# BreakOutBoard_Cyclone.net
KiCad netlist of a schematic drawn in Altium Designer
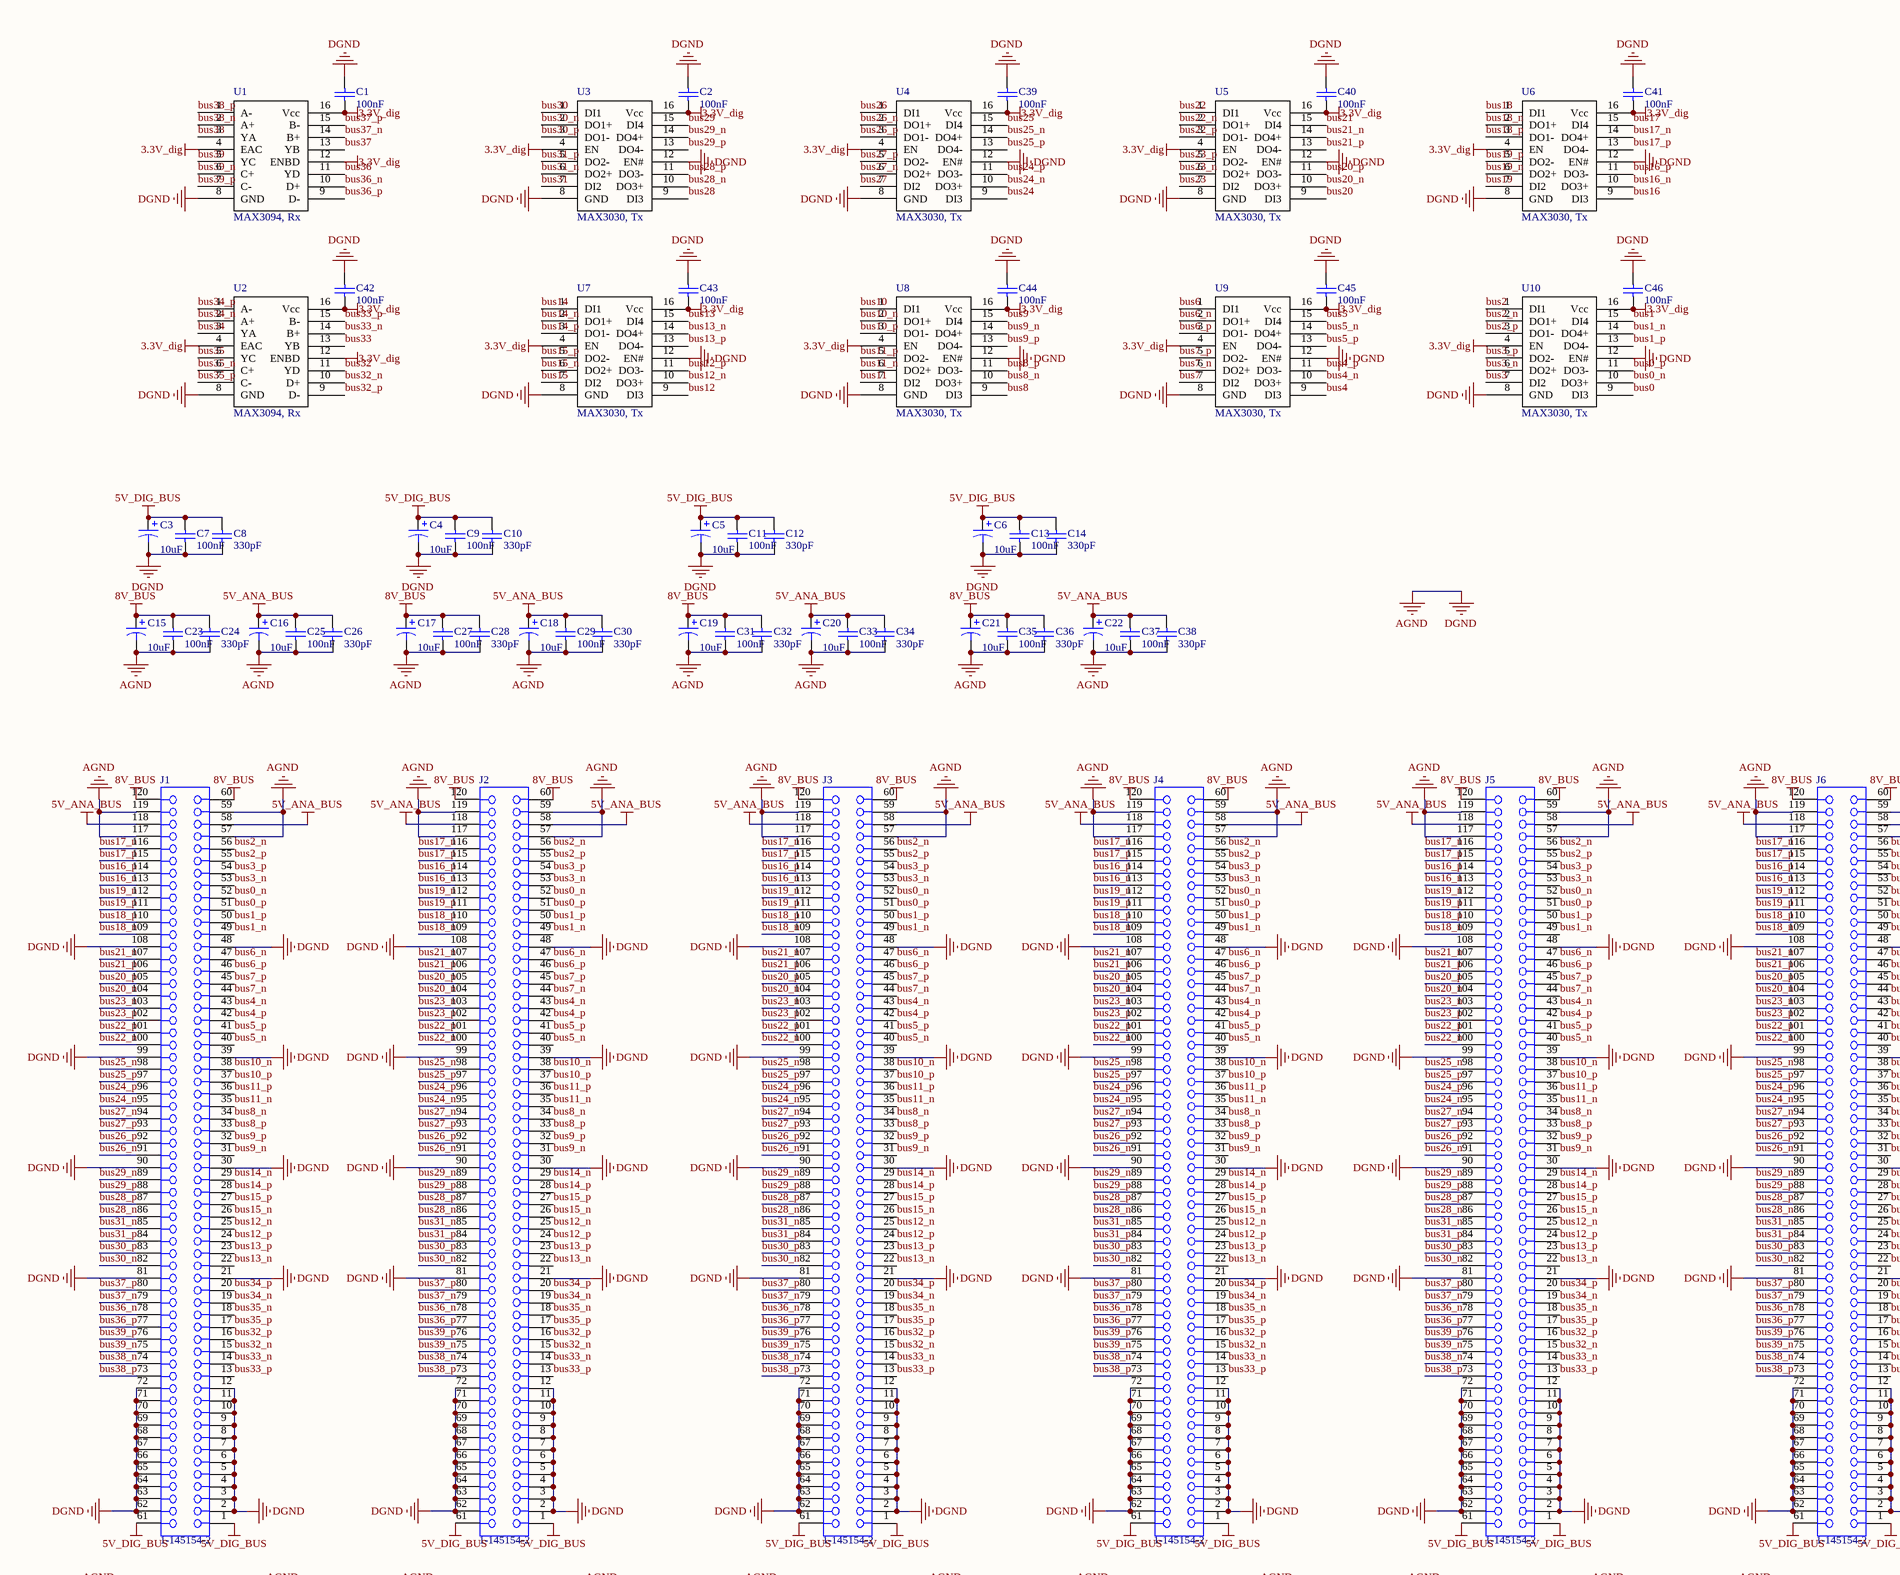
[diagram p0: BreakOutBoard_Cyclone.SchDoc, top left]
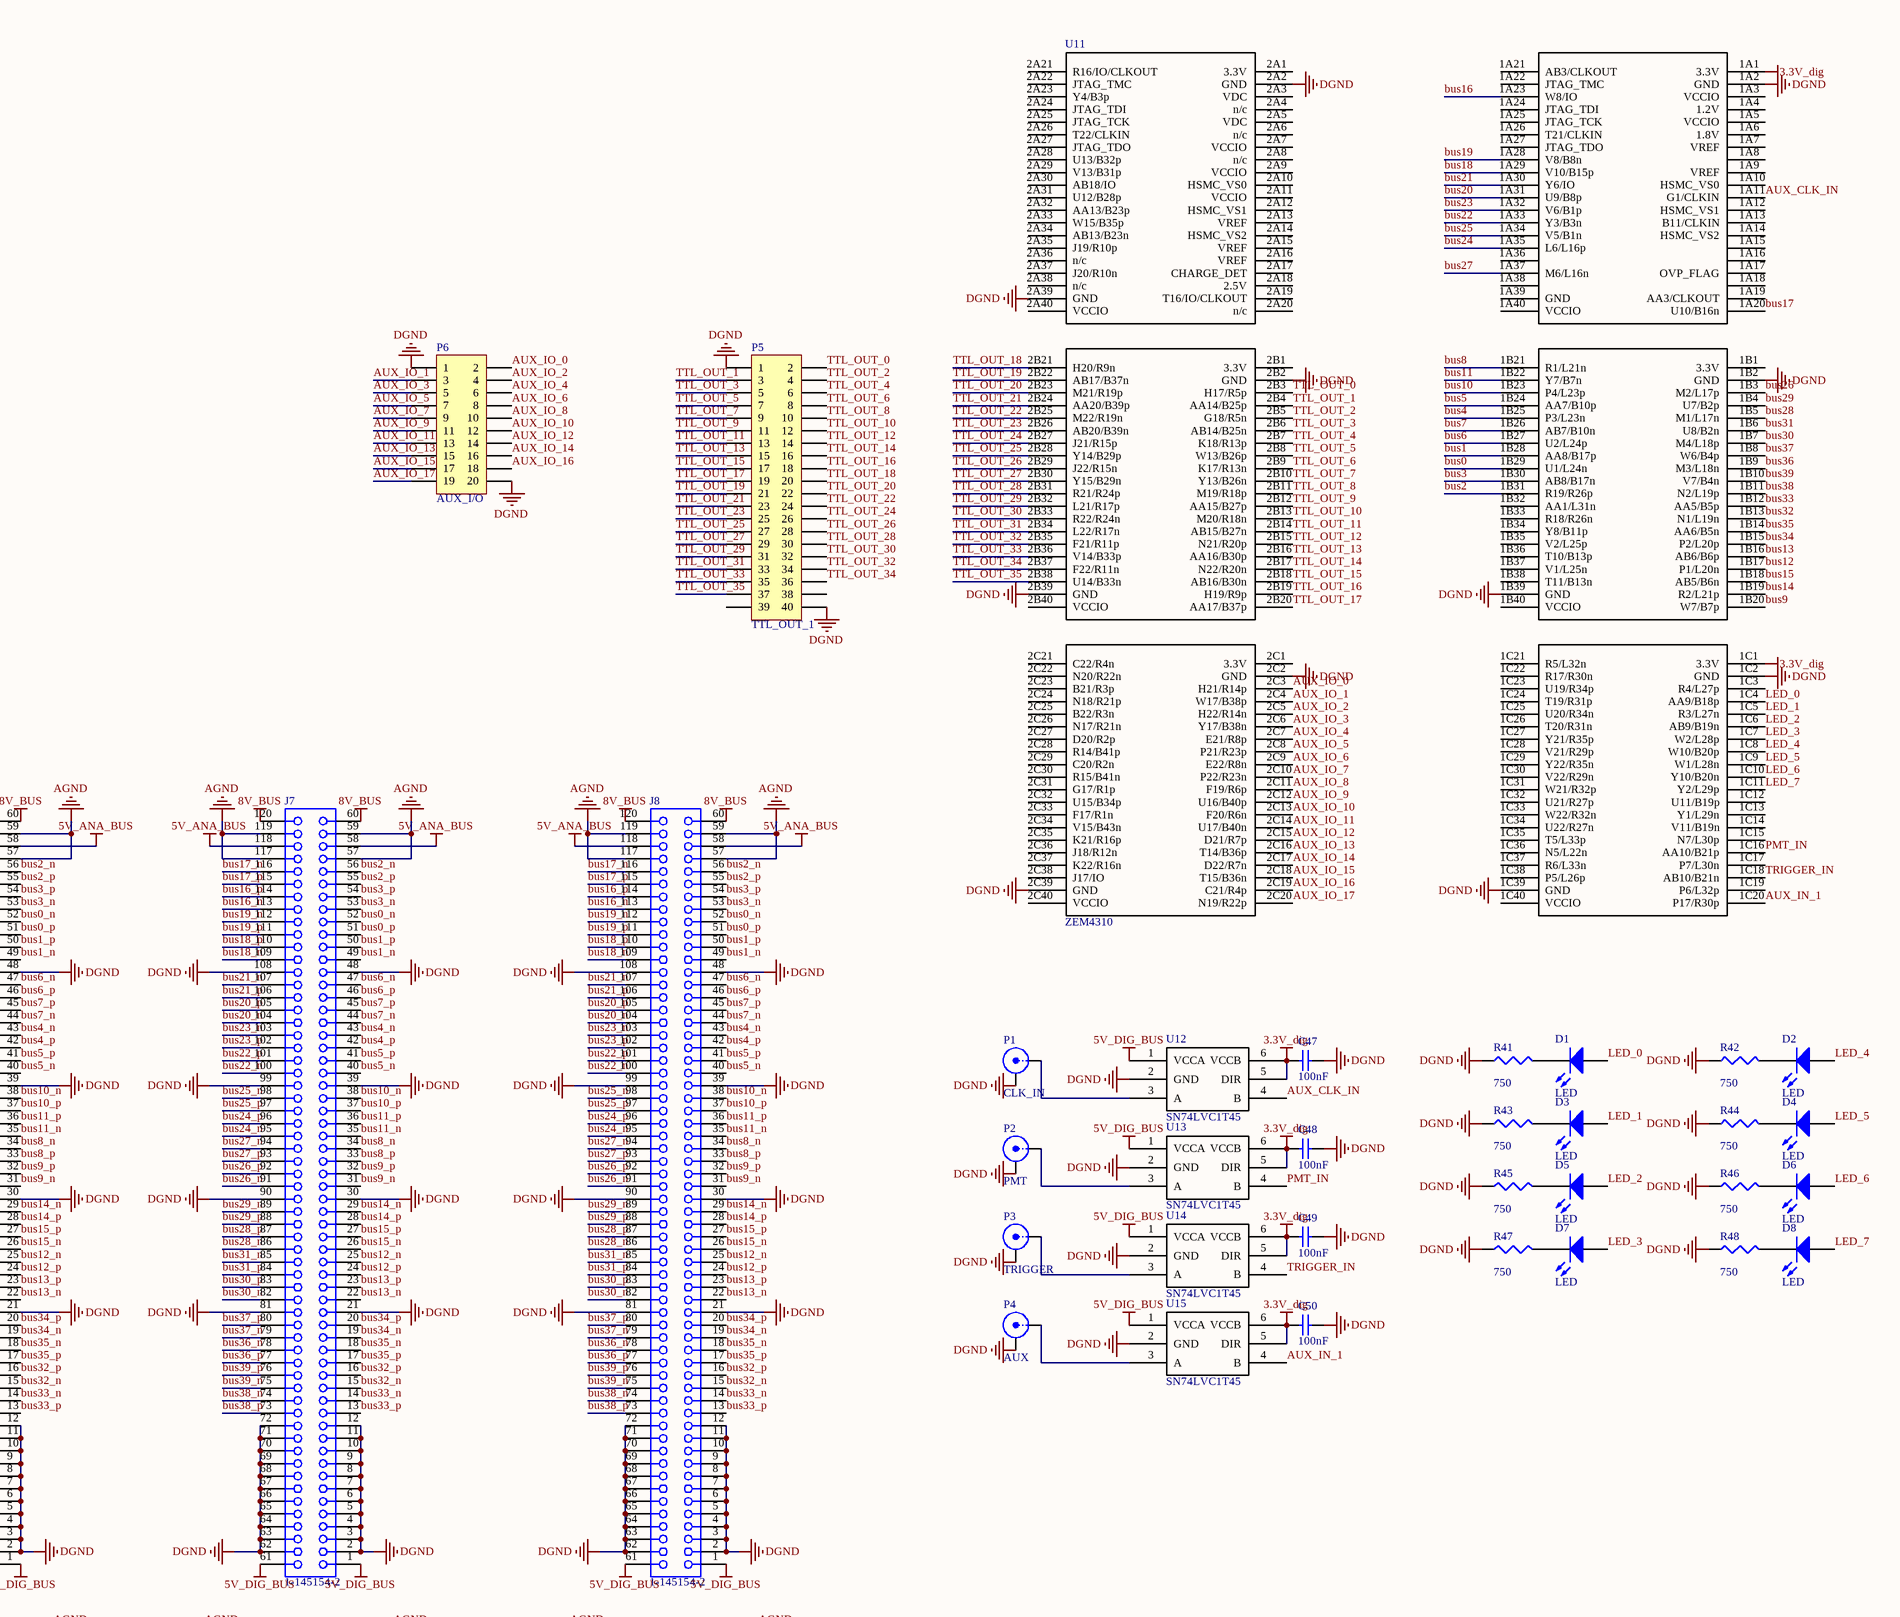
[diagram p1: BreakOutBoard_Cyclone.SchDoc, top right]
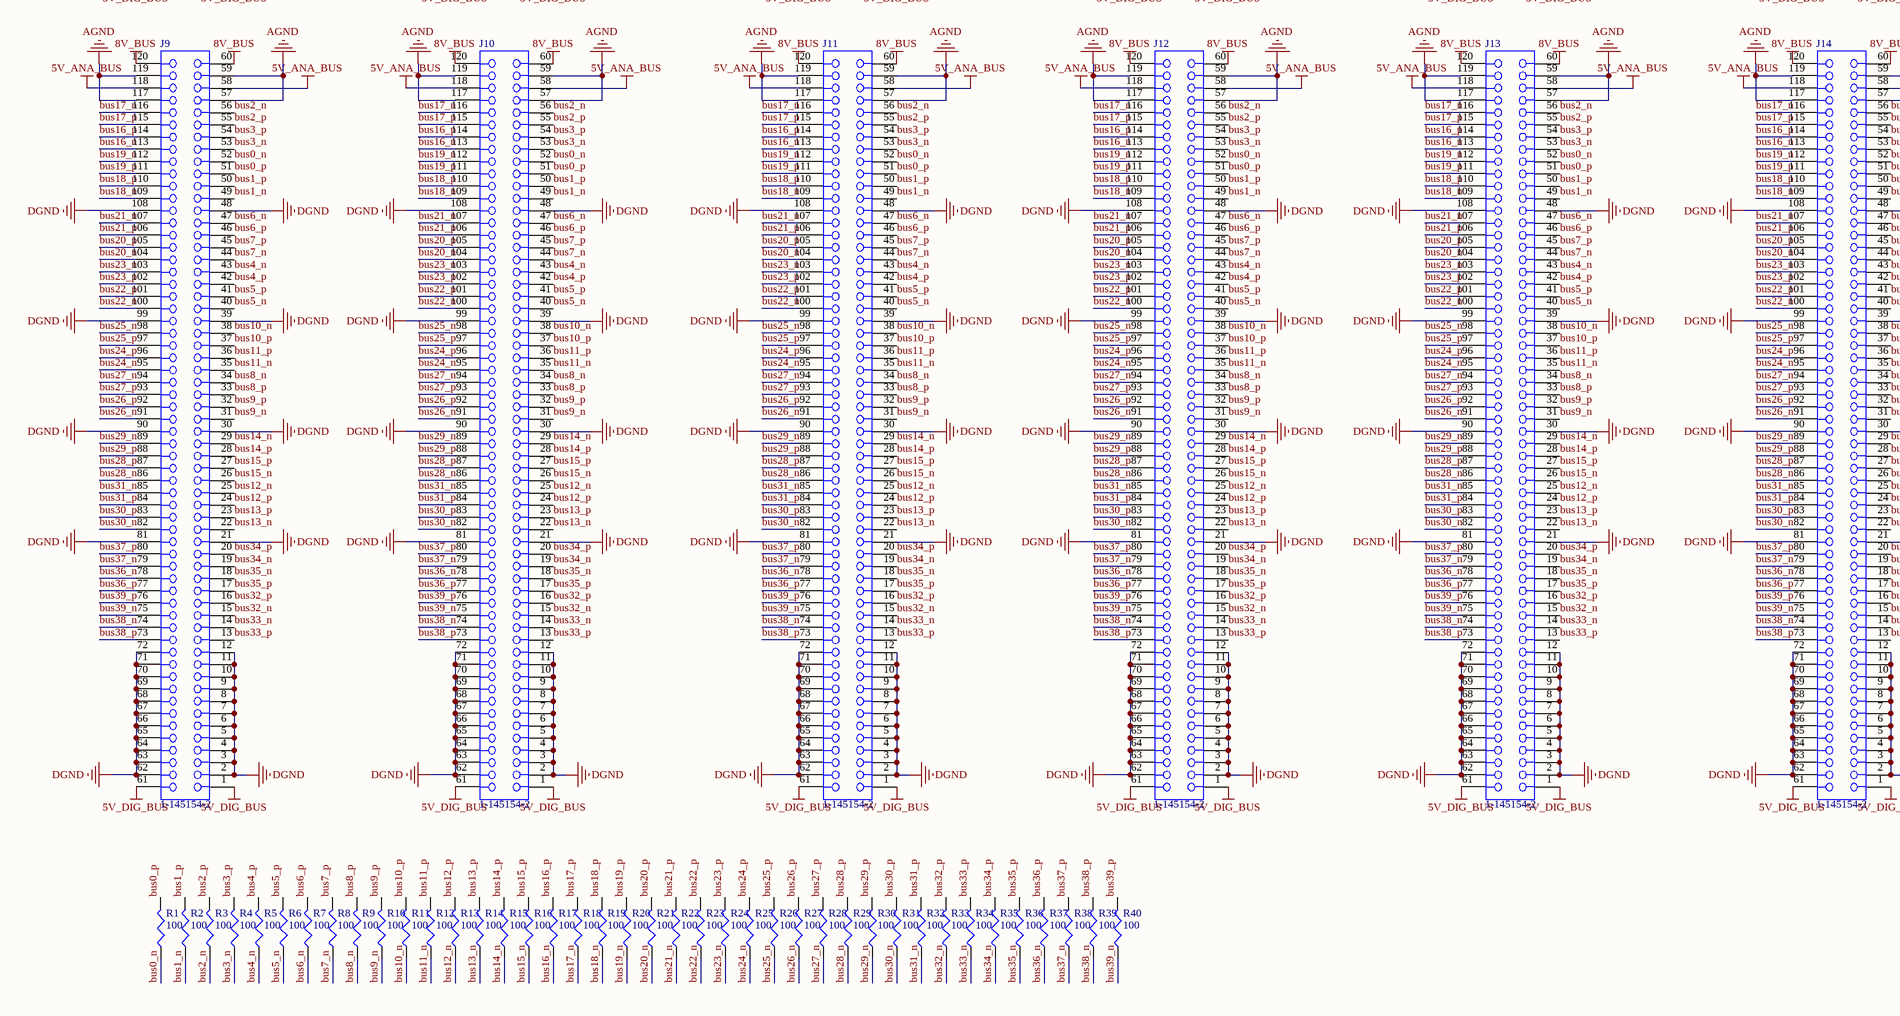
[diagram p2: BreakOutBoard_Cyclone.SchDoc, bottom left]
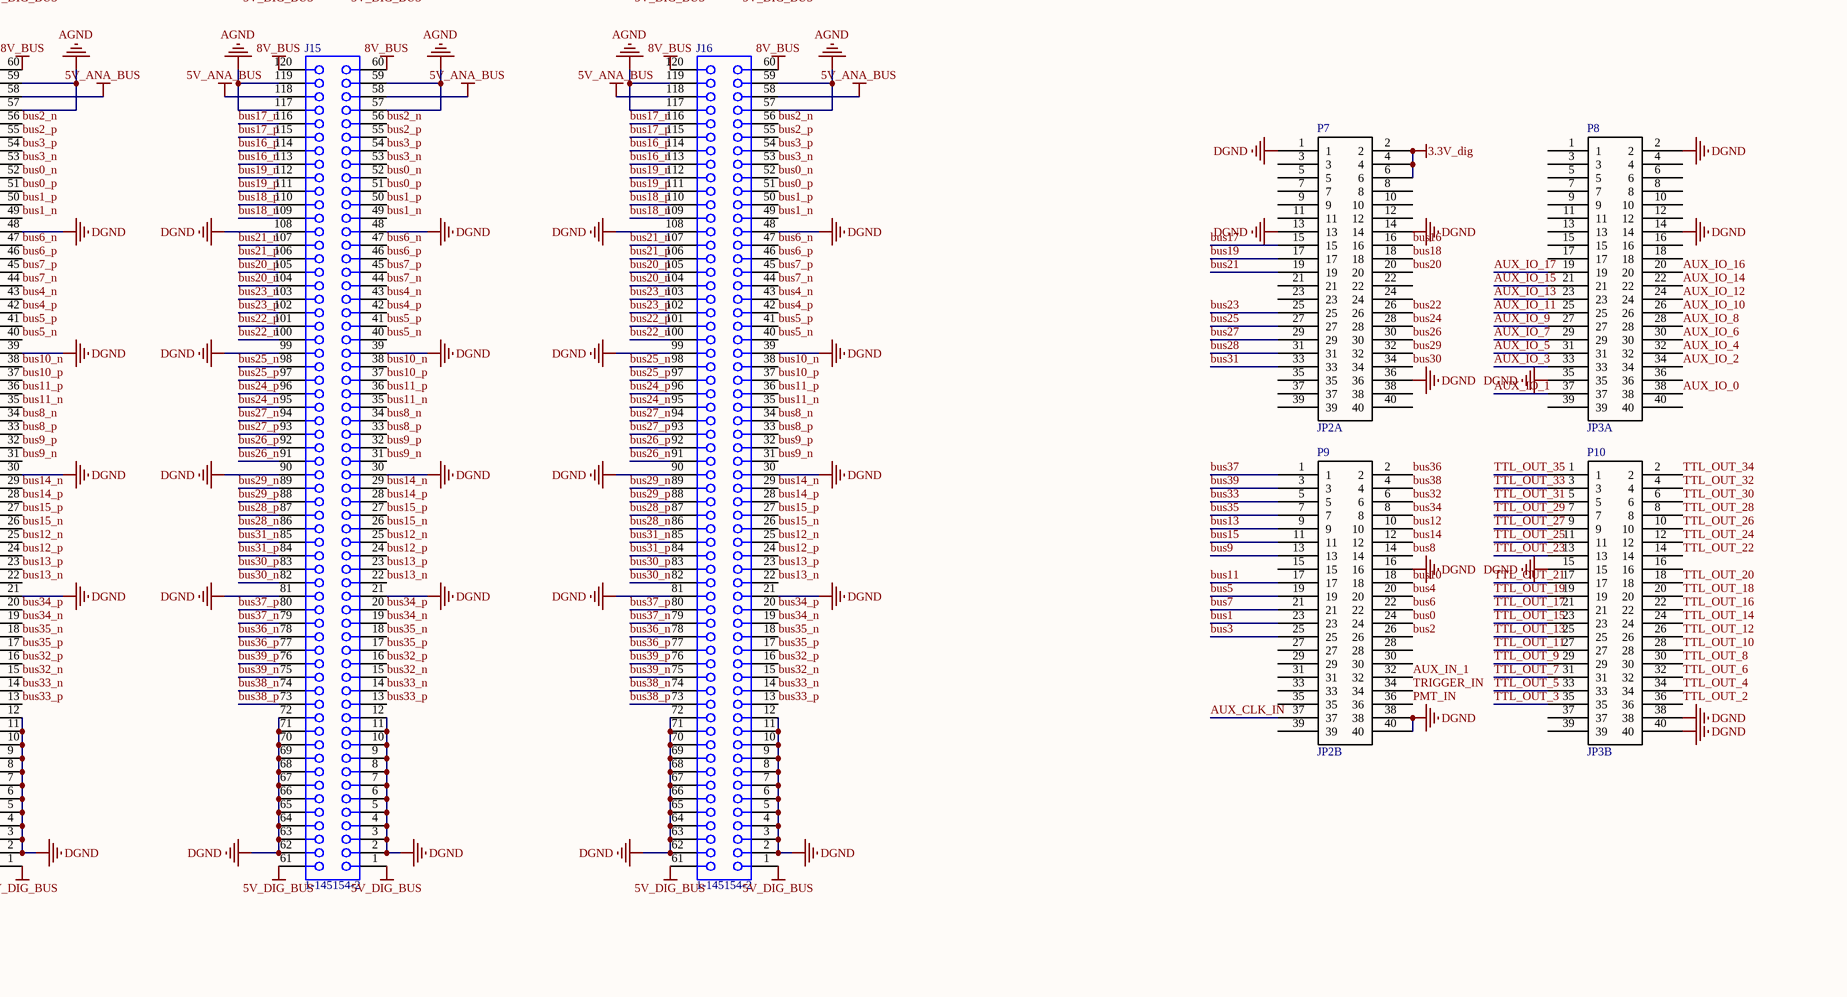
[diagram p3: BreakOutBoard_Cyclone.SchDoc, bottom right]

(export (version "E")
  (design (tool "Eeschema 10.0.6"))
  (components
    (comp (ref "C1")
      (value "100nF")
      (footprint "CAPC2012L")
      (description "Capacitor (Semiconductor SIM Model)")
      (fields (field (name "Comment") "Cap Semi") (field (name "PUBLISHER") "Altium Limited"))
      (libsource (lib "Miscellaneous Devices") (part "Cap Semi"))
    )
    (comp (ref "C2")
      (value "100nF")
      (footprint "CAPC2012L")
      (description "Capacitor (Semiconductor SIM Model)")
      (fields (field (name "Comment") "Cap Semi") (field (name "PUBLISHER") "Altium Limited"))
      (libsource (lib "Miscellaneous Devices") (part "Cap Semi"))
    )
    (comp (ref "C3")
      (value "10uF")
      (footprint "B")
      (description "Polarized Capacitor (Radial)")
      (fields
        (field (name "VOLTAGE") "16V")
        (field (name "Comment") "Cap Pol1")
        (field (name "PUBLISHER") "Altium Limited")
      )
      (libsource (lib "Miscellaneous Devices") (part "Cap Pol1"))
    )
    (comp (ref "C4")
      (value "10uF")
      (footprint "B")
      (description "Polarized Capacitor (Radial)")
      (fields
        (field (name "VOLTAGE") "16V")
        (field (name "Comment") "Cap Pol1")
        (field (name "PUBLISHER") "Altium Limited")
      )
      (libsource (lib "Miscellaneous Devices") (part "Cap Pol1"))
    )
    (comp (ref "C5")
      (value "10uF")
      (footprint "B")
      (description "Polarized Capacitor (Radial)")
      (fields
        (field (name "VOLTAGE") "16V")
        (field (name "Comment") "Cap Pol1")
        (field (name "PUBLISHER") "Altium Limited")
      )
      (libsource (lib "Miscellaneous Devices") (part "Cap Pol1"))
    )
    (comp (ref "C6")
      (value "10uF")
      (footprint "B")
      (description "Polarized Capacitor (Radial)")
      (fields
        (field (name "VOLTAGE") "16V")
        (field (name "Comment") "Cap Pol1")
        (field (name "PUBLISHER") "Altium Limited")
      )
      (libsource (lib "Miscellaneous Devices") (part "Cap Pol1"))
    )
    (comp (ref "C7")
      (value "100nF")
      (footprint "CAPC2012L")
      (description "Capacitor (Semiconductor SIM Model)")
      (fields (field (name "Comment") "Cap Semi") (field (name "PUBLISHER") "Altium Limited"))
      (libsource (lib "Miscellaneous Devices") (part "Cap Semi"))
    )
    (comp (ref "C8")
      (value "330pF")
      (footprint "CAPC2012L")
      (description "Capacitor (Semiconductor SIM Model)")
      (fields (field (name "Comment") "Cap Semi") (field (name "PUBLISHER") "Altium Limited"))
      (libsource (lib "Miscellaneous Devices") (part "Cap Semi"))
    )
    (comp (ref "C9")
      (value "100nF")
      (footprint "CAPC2012L")
      (description "Capacitor (Semiconductor SIM Model)")
      (fields (field (name "Comment") "Cap Semi") (field (name "PUBLISHER") "Altium Limited"))
      (libsource (lib "Miscellaneous Devices") (part "Cap Semi"))
    )
    (comp (ref "C10")
      (value "330pF")
      (footprint "CAPC2012L")
      (description "Capacitor (Semiconductor SIM Model)")
      (fields (field (name "Comment") "Cap Semi") (field (name "PUBLISHER") "Altium Limited"))
      (libsource (lib "Miscellaneous Devices") (part "Cap Semi"))
    )
    (comp (ref "C11")
      (value "100nF")
      (footprint "CAPC2012L")
      (description "Capacitor (Semiconductor SIM Model)")
      (fields (field (name "Comment") "Cap Semi") (field (name "PUBLISHER") "Altium Limited"))
      (libsource (lib "Miscellaneous Devices") (part "Cap Semi"))
    )
    (comp (ref "C12")
      (value "330pF")
      (footprint "CAPC2012L")
      (description "Capacitor (Semiconductor SIM Model)")
      (fields (field (name "Comment") "Cap Semi") (field (name "PUBLISHER") "Altium Limited"))
      (libsource (lib "Miscellaneous Devices") (part "Cap Semi"))
    )
    (comp (ref "C13")
      (value "100nF")
      (footprint "CAPC2012L")
      (description "Capacitor (Semiconductor SIM Model)")
      (fields (field (name "Comment") "Cap Semi") (field (name "PUBLISHER") "Altium Limited"))
      (libsource (lib "Miscellaneous Devices") (part "Cap Semi"))
    )
    (comp (ref "C14")
      (value "330pF")
      (footprint "CAPC2012L")
      (description "Capacitor (Semiconductor SIM Model)")
      (fields (field (name "Comment") "Cap Semi") (field (name "PUBLISHER") "Altium Limited"))
      (libsource (lib "Miscellaneous Devices") (part "Cap Semi"))
    )
    (comp (ref "C15")
      (value "10uF")
      (footprint "B")
      (description "Polarized Capacitor (Radial)")
      (fields
        (field (name "VOLTAGE") "16V")
        (field (name "Comment") "Cap Pol1")
        (field (name "PUBLISHER") "Altium Limited")
      )
      (libsource (lib "Miscellaneous Devices") (part "Cap Pol1"))
    )
    (comp (ref "C16")
      (value "10uF")
      (footprint "B")
      (description "Polarized Capacitor (Radial)")
      (fields
        (field (name "VOLTAGE") "16V")
        (field (name "Comment") "Cap Pol1")
        (field (name "PUBLISHER") "Altium Limited")
      )
      (libsource (lib "Miscellaneous Devices") (part "Cap Pol1"))
    )
    (comp (ref "C17")
      (value "10uF")
      (footprint "B")
      (description "Polarized Capacitor (Radial)")
      (fields
        (field (name "VOLTAGE") "16V")
        (field (name "Comment") "Cap Pol1")
        (field (name "PUBLISHER") "Altium Limited")
      )
      (libsource (lib "Miscellaneous Devices") (part "Cap Pol1"))
    )
    (comp (ref "C18")
      (value "10uF")
      (footprint "B")
      (description "Polarized Capacitor (Radial)")
      (fields
        (field (name "VOLTAGE") "16V")
        (field (name "Comment") "Cap Pol1")
        (field (name "PUBLISHER") "Altium Limited")
      )
      (libsource (lib "Miscellaneous Devices") (part "Cap Pol1"))
    )
    (comp (ref "C19")
      (value "10uF")
      (footprint "B")
      (description "Polarized Capacitor (Radial)")
      (fields
        (field (name "VOLTAGE") "16V")
        (field (name "Comment") "Cap Pol1")
        (field (name "PUBLISHER") "Altium Limited")
      )
      (libsource (lib "Miscellaneous Devices") (part "Cap Pol1"))
    )
    (comp (ref "C20")
      (value "10uF")
      (footprint "B")
      (description "Polarized Capacitor (Radial)")
      (fields
        (field (name "VOLTAGE") "16V")
        (field (name "Comment") "Cap Pol1")
        (field (name "PUBLISHER") "Altium Limited")
      )
      (libsource (lib "Miscellaneous Devices") (part "Cap Pol1"))
    )
    (comp (ref "C21")
      (value "10uF")
      (footprint "B")
      (description "Polarized Capacitor (Radial)")
      (fields
        (field (name "VOLTAGE") "16V")
        (field (name "Comment") "Cap Pol1")
        (field (name "PUBLISHER") "Altium Limited")
      )
      (libsource (lib "Miscellaneous Devices") (part "Cap Pol1"))
    )
    (comp (ref "C22")
      (value "10uF")
      (footprint "B")
      (description "Polarized Capacitor (Radial)")
      (fields
        (field (name "VOLTAGE") "16V")
        (field (name "Comment") "Cap Pol1")
        (field (name "PUBLISHER") "Altium Limited")
      )
      (libsource (lib "Miscellaneous Devices") (part "Cap Pol1"))
    )
    (comp (ref "C23")
      (value "100nF")
      (footprint "CAPC2012L")
      (description "Capacitor (Semiconductor SIM Model)")
      (fields (field (name "Comment") "Cap Semi") (field (name "PUBLISHER") "Altium Limited"))
      (libsource (lib "Miscellaneous Devices") (part "Cap Semi"))
    )
    (comp (ref "C24")
      (value "330pF")
      (footprint "CAPC2012L")
      (description "Capacitor (Semiconductor SIM Model)")
      (fields (field (name "Comment") "Cap Semi") (field (name "PUBLISHER") "Altium Limited"))
      (libsource (lib "Miscellaneous Devices") (part "Cap Semi"))
    )
    (comp (ref "C25")
      (value "100nF")
      (footprint "CAPC2012L")
      (description "Capacitor (Semiconductor SIM Model)")
      (fields (field (name "Comment") "Cap Semi") (field (name "PUBLISHER") "Altium Limited"))
      (libsource (lib "Miscellaneous Devices") (part "Cap Semi"))
    )
    (comp (ref "C26")
      (value "330pF")
      (footprint "CAPC2012L")
      (description "Capacitor (Semiconductor SIM Model)")
      (fields (field (name "Comment") "Cap Semi") (field (name "PUBLISHER") "Altium Limited"))
      (libsource (lib "Miscellaneous Devices") (part "Cap Semi"))
    )
    (comp (ref "C27")
      (value "100nF")
      (footprint "CAPC2012L")
      (description "Capacitor (Semiconductor SIM Model)")
      (fields (field (name "Comment") "Cap Semi") (field (name "PUBLISHER") "Altium Limited"))
      (libsource (lib "Miscellaneous Devices") (part "Cap Semi"))
    )
    (comp (ref "C28")
      (value "330pF")
      (footprint "CAPC2012L")
      (description "Capacitor (Semiconductor SIM Model)")
      (fields (field (name "Comment") "Cap Semi") (field (name "PUBLISHER") "Altium Limited"))
      (libsource (lib "Miscellaneous Devices") (part "Cap Semi"))
    )
    (comp (ref "C29")
      (value "100nF")
      (footprint "CAPC2012L")
      (description "Capacitor (Semiconductor SIM Model)")
      (fields (field (name "Comment") "Cap Semi") (field (name "PUBLISHER") "Altium Limited"))
      (libsource (lib "Miscellaneous Devices") (part "Cap Semi"))
    )
    (comp (ref "C30")
      (value "330pF")
      (footprint "CAPC2012L")
      (description "Capacitor (Semiconductor SIM Model)")
      (fields (field (name "Comment") "Cap Semi") (field (name "PUBLISHER") "Altium Limited"))
      (libsource (lib "Miscellaneous Devices") (part "Cap Semi"))
    )
    (comp (ref "C31")
      (value "100nF")
      (footprint "CAPC2012L")
      (description "Capacitor (Semiconductor SIM Model)")
      (fields (field (name "Comment") "Cap Semi") (field (name "PUBLISHER") "Altium Limited"))
      (libsource (lib "Miscellaneous Devices") (part "Cap Semi"))
    )
    (comp (ref "C32")
      (value "330pF")
      (footprint "CAPC2012L")
      (description "Capacitor (Semiconductor SIM Model)")
      (fields (field (name "Comment") "Cap Semi") (field (name "PUBLISHER") "Altium Limited"))
      (libsource (lib "Miscellaneous Devices") (part "Cap Semi"))
    )
    (comp (ref "C33")
      (value "100nF")
      (footprint "CAPC2012L")
      (description "Capacitor (Semiconductor SIM Model)")
      (fields (field (name "Comment") "Cap Semi") (field (name "PUBLISHER") "Altium Limited"))
      (libsource (lib "Miscellaneous Devices") (part "Cap Semi"))
    )
    (comp (ref "C34")
      (value "330pF")
      (footprint "CAPC2012L")
      (description "Capacitor (Semiconductor SIM Model)")
      (fields (field (name "Comment") "Cap Semi") (field (name "PUBLISHER") "Altium Limited"))
      (libsource (lib "Miscellaneous Devices") (part "Cap Semi"))
    )
    (comp (ref "C35")
      (value "100nF")
      (footprint "CAPC2012L")
      (description "Capacitor (Semiconductor SIM Model)")
      (fields (field (name "Comment") "Cap Semi") (field (name "PUBLISHER") "Altium Limited"))
      (libsource (lib "Miscellaneous Devices") (part "Cap Semi"))
    )
    (comp (ref "C36")
      (value "330pF")
      (footprint "CAPC2012L")
      (description "Capacitor (Semiconductor SIM Model)")
      (fields (field (name "Comment") "Cap Semi") (field (name "PUBLISHER") "Altium Limited"))
      (libsource (lib "Miscellaneous Devices") (part "Cap Semi"))
    )
    (comp (ref "C37")
      (value "100nF")
      (footprint "CAPC2012L")
      (description "Capacitor (Semiconductor SIM Model)")
      (fields (field (name "Comment") "Cap Semi") (field (name "PUBLISHER") "Altium Limited"))
      (libsource (lib "Miscellaneous Devices") (part "Cap Semi"))
    )
    (comp (ref "C38")
      (value "330pF")
      (footprint "CAPC2012L")
      (description "Capacitor (Semiconductor SIM Model)")
      (fields (field (name "Comment") "Cap Semi") (field (name "PUBLISHER") "Altium Limited"))
      (libsource (lib "Miscellaneous Devices") (part "Cap Semi"))
    )
    (comp (ref "C39")
      (value "100nF")
      (footprint "CAPC2012L")
      (description "Capacitor (Semiconductor SIM Model)")
      (fields (field (name "Comment") "Cap Semi") (field (name "PUBLISHER") "Altium Limited"))
      (libsource (lib "Miscellaneous Devices") (part "Cap Semi"))
    )
    (comp (ref "C40")
      (value "100nF")
      (footprint "CAPC2012L")
      (description "Capacitor (Semiconductor SIM Model)")
      (fields (field (name "Comment") "Cap Semi") (field (name "PUBLISHER") "Altium Limited"))
      (libsource (lib "Miscellaneous Devices") (part "Cap Semi"))
    )
    (comp (ref "C41")
      (value "100nF")
      (footprint "CAPC2012L")
      (description "Capacitor (Semiconductor SIM Model)")
      (fields (field (name "Comment") "Cap Semi") (field (name "PUBLISHER") "Altium Limited"))
      (libsource (lib "Miscellaneous Devices") (part "Cap Semi"))
    )
    (comp (ref "C42")
      (value "100nF")
      (footprint "CAPC2012L")
      (description "Capacitor (Semiconductor SIM Model)")
      (fields (field (name "Comment") "Cap Semi") (field (name "PUBLISHER") "Altium Limited"))
      (libsource (lib "Miscellaneous Devices") (part "Cap Semi"))
    )
    (comp (ref "C43")
      (value "100nF")
      (footprint "CAPC2012L")
      (description "Capacitor (Semiconductor SIM Model)")
      (fields (field (name "Comment") "Cap Semi") (field (name "PUBLISHER") "Altium Limited"))
      (libsource (lib "Miscellaneous Devices") (part "Cap Semi"))
    )
    (comp (ref "C44")
      (value "100nF")
      (footprint "CAPC2012L")
      (description "Capacitor (Semiconductor SIM Model)")
      (fields (field (name "Comment") "Cap Semi") (field (name "PUBLISHER") "Altium Limited"))
      (libsource (lib "Miscellaneous Devices") (part "Cap Semi"))
    )
    (comp (ref "C45")
      (value "100nF")
      (footprint "CAPC2012L")
      (description "Capacitor (Semiconductor SIM Model)")
      (fields (field (name "Comment") "Cap Semi") (field (name "PUBLISHER") "Altium Limited"))
      (libsource (lib "Miscellaneous Devices") (part "Cap Semi"))
    )
    (comp (ref "C46")
      (value "100nF")
      (footprint "CAPC2012L")
      (description "Capacitor (Semiconductor SIM Model)")
      (fields (field (name "Comment") "Cap Semi") (field (name "PUBLISHER") "Altium Limited"))
      (libsource (lib "Miscellaneous Devices") (part "Cap Semi"))
    )
    (comp (ref "C47")
      (value "100nF")
      (footprint "CAPC2012L")
      (description "Capacitor (Semiconductor SIM Model)")
      (fields (field (name "Comment") "Cap Semi") (field (name "PUBLISHER") "Altium Limited"))
      (libsource (lib "Miscellaneous Devices") (part "Cap Semi"))
    )
    (comp (ref "C48")
      (value "100nF")
      (footprint "CAPC2012L")
      (description "Capacitor (Semiconductor SIM Model)")
      (fields (field (name "Comment") "Cap Semi") (field (name "PUBLISHER") "Altium Limited"))
      (libsource (lib "Miscellaneous Devices") (part "Cap Semi"))
    )
    (comp (ref "C49")
      (value "100nF")
      (footprint "CAPC2012L")
      (description "Capacitor (Semiconductor SIM Model)")
      (fields (field (name "Comment") "Cap Semi") (field (name "PUBLISHER") "Altium Limited"))
      (libsource (lib "Miscellaneous Devices") (part "Cap Semi"))
    )
    (comp (ref "C50")
      (value "100nF")
      (footprint "CAPC2012L")
      (description "Capacitor (Semiconductor SIM Model)")
      (fields (field (name "Comment") "Cap Semi") (field (name "PUBLISHER") "Altium Limited"))
      (libsource (lib "Miscellaneous Devices") (part "Cap Semi"))
    )
    (comp (ref "D1")
      (value "LED")
      (footprint "RESC2012M")
      (description "Typical BLUE SiC LED")
      (fields (field (name "PUBLISHER") "Altium Limited"))
      (libsource (lib "Miscellaneous Devices") (part "LED3"))
    )
    (comp (ref "D2")
      (value "LED")
      (footprint "RESC2012M")
      (description "Typical BLUE SiC LED")
      (fields (field (name "PUBLISHER") "Altium Limited"))
      (libsource (lib "Miscellaneous Devices") (part "LED3"))
    )
    (comp (ref "D3")
      (value "LED")
      (footprint "RESC2012M")
      (description "Typical BLUE SiC LED")
      (fields (field (name "PUBLISHER") "Altium Limited"))
      (libsource (lib "Miscellaneous Devices") (part "LED3"))
    )
    (comp (ref "D4")
      (value "LED")
      (footprint "RESC2012M")
      (description "Typical BLUE SiC LED")
      (fields (field (name "PUBLISHER") "Altium Limited"))
      (libsource (lib "Miscellaneous Devices") (part "LED3"))
    )
    (comp (ref "D5")
      (value "LED")
      (footprint "RESC2012M")
      (description "Typical BLUE SiC LED")
      (fields (field (name "PUBLISHER") "Altium Limited"))
      (libsource (lib "Miscellaneous Devices") (part "LED3"))
    )
    (comp (ref "D6")
      (value "LED")
      (footprint "RESC2012M")
      (description "Typical BLUE SiC LED")
      (fields (field (name "PUBLISHER") "Altium Limited"))
      (libsource (lib "Miscellaneous Devices") (part "LED3"))
    )
    (comp (ref "D7")
      (value "LED")
      (footprint "RESC2012M")
      (description "Typical BLUE SiC LED")
      (fields (field (name "PUBLISHER") "Altium Limited"))
      (libsource (lib "Miscellaneous Devices") (part "LED3"))
    )
    (comp (ref "D8")
      (value "LED")
      (footprint "RESC2012M")
      (description "Typical BLUE SiC LED")
      (fields (field (name "PUBLISHER") "Altium Limited"))
      (libsource (lib "Miscellaneous Devices") (part "LED3"))
    )
    (comp (ref "J1")
      (value "1-145154-2")
      (footprint "1-145154-2")
      (description "Connector Assembly, 60 Dual Position, 1.27 [.050] Series, Standard Edge")
      (fields (field (name "VOLTAGE") "3.3V, 5V") (field (name "PUBLISHER") "Altium Limited"))
      (libsource (lib "AMP Card Edge 050 Series PCI") (part "1-145154-2"))
    )
    (comp (ref "J2")
      (value "1-145154-2")
      (footprint "1-145154-2")
      (description "Connector Assembly, 60 Dual Position, 1.27 [.050] Series, Standard Edge")
      (fields (field (name "VOLTAGE") "3.3V, 5V") (field (name "PUBLISHER") "Altium Limited"))
      (libsource (lib "AMP Card Edge 050 Series PCI") (part "1-145154-2"))
    )
    (comp (ref "J3")
      (value "1-145154-2")
      (footprint "1-145154-2")
      (description "Connector Assembly, 60 Dual Position, 1.27 [.050] Series, Standard Edge")
      (fields (field (name "VOLTAGE") "3.3V, 5V") (field (name "PUBLISHER") "Altium Limited"))
      (libsource (lib "AMP Card Edge 050 Series PCI") (part "1-145154-2"))
    )
    (comp (ref "J4")
      (value "1-145154-2")
      (footprint "1-145154-2")
      (description "Connector Assembly, 60 Dual Position, 1.27 [.050] Series, Standard Edge")
      (fields (field (name "VOLTAGE") "3.3V, 5V") (field (name "PUBLISHER") "Altium Limited"))
      (libsource (lib "AMP Card Edge 050 Series PCI") (part "1-145154-2"))
    )
    (comp (ref "J5")
      (value "1-145154-2")
      (footprint "1-145154-2")
      (description "Connector Assembly, 60 Dual Position, 1.27 [.050] Series, Standard Edge")
      (fields (field (name "VOLTAGE") "3.3V, 5V") (field (name "PUBLISHER") "Altium Limited"))
      (libsource (lib "AMP Card Edge 050 Series PCI") (part "1-145154-2"))
    )
    (comp (ref "J6")
      (value "1-145154-2")
      (footprint "1-145154-2")
      (description "Connector Assembly, 60 Dual Position, 1.27 [.050] Series, Standard Edge")
      (fields (field (name "VOLTAGE") "3.3V, 5V") (field (name "PUBLISHER") "Altium Limited"))
      (libsource (lib "AMP Card Edge 050 Series PCI") (part "1-145154-2"))
    )
    (comp (ref "J7")
      (value "1-145154-2")
      (footprint "1-145154-2")
      (description "Connector Assembly, 60 Dual Position, 1.27 [.050] Series, Standard Edge")
      (fields (field (name "VOLTAGE") "3.3V, 5V") (field (name "PUBLISHER") "Altium Limited"))
      (libsource (lib "AMP Card Edge 050 Series PCI") (part "1-145154-2"))
    )
    (comp (ref "J8")
      (value "1-145154-2")
      (footprint "1-145154-2")
      (description "Connector Assembly, 60 Dual Position, 1.27 [.050] Series, Standard Edge")
      (fields (field (name "VOLTAGE") "3.3V, 5V") (field (name "PUBLISHER") "Altium Limited"))
      (libsource (lib "AMP Card Edge 050 Series PCI") (part "1-145154-2"))
    )
    (comp (ref "J9")
      (value "1-145154-2")
      (footprint "1-145154-2")
      (description "Connector Assembly, 60 Dual Position, 1.27 [.050] Series, Standard Edge")
      (fields (field (name "VOLTAGE") "3.3V, 5V") (field (name "PUBLISHER") "Altium Limited"))
      (libsource (lib "AMP Card Edge 050 Series PCI") (part "1-145154-2"))
    )
    (comp (ref "J10")
      (value "1-145154-2")
      (footprint "1-145154-2")
      (description "Connector Assembly, 60 Dual Position, 1.27 [.050] Series, Standard Edge")
      (fields (field (name "VOLTAGE") "3.3V, 5V") (field (name "PUBLISHER") "Altium Limited"))
      (libsource (lib "AMP Card Edge 050 Series PCI") (part "1-145154-2"))
    )
    (comp (ref "J11")
      (value "1-145154-2")
      (footprint "1-145154-2")
      (description "Connector Assembly, 60 Dual Position, 1.27 [.050] Series, Standard Edge")
      (fields (field (name "VOLTAGE") "3.3V, 5V") (field (name "PUBLISHER") "Altium Limited"))
      (libsource (lib "AMP Card Edge 050 Series PCI") (part "1-145154-2"))
    )
    (comp (ref "J12")
      (value "1-145154-2")
      (footprint "1-145154-2")
      (description "Connector Assembly, 60 Dual Position, 1.27 [.050] Series, Standard Edge")
      (fields (field (name "VOLTAGE") "3.3V, 5V") (field (name "PUBLISHER") "Altium Limited"))
      (libsource (lib "AMP Card Edge 050 Series PCI") (part "1-145154-2"))
    )
    (comp (ref "J13")
      (value "1-145154-2")
      (footprint "1-145154-2")
      (description "Connector Assembly, 60 Dual Position, 1.27 [.050] Series, Standard Edge")
      (fields (field (name "VOLTAGE") "3.3V, 5V") (field (name "PUBLISHER") "Altium Limited"))
      (libsource (lib "AMP Card Edge 050 Series PCI") (part "1-145154-2"))
    )
    (comp (ref "J14")
      (value "1-145154-2")
      (footprint "1-145154-2")
      (description "Connector Assembly, 60 Dual Position, 1.27 [.050] Series, Standard Edge")
      (fields (field (name "VOLTAGE") "3.3V, 5V") (field (name "PUBLISHER") "Altium Limited"))
      (libsource (lib "AMP Card Edge 050 Series PCI") (part "1-145154-2"))
    )
    (comp (ref "J15")
      (value "1-145154-2")
      (footprint "1-145154-2")
      (description "Connector Assembly, 60 Dual Position, 1.27 [.050] Series, Standard Edge")
      (fields (field (name "VOLTAGE") "3.3V, 5V") (field (name "PUBLISHER") "Altium Limited"))
      (libsource (lib "AMP Card Edge 050 Series PCI") (part "1-145154-2"))
    )
    (comp (ref "J16")
      (value "1-145154-2")
      (footprint "1-145154-2")
      (description "Connector Assembly, 60 Dual Position, 1.27 [.050] Series, Standard Edge")
      (fields (field (name "VOLTAGE") "3.3V, 5V") (field (name "PUBLISHER") "Altium Limited"))
      (libsource (lib "AMP Card Edge 050 Series PCI") (part "1-145154-2"))
    )
    (comp (ref "P1")
      (value "CLK_IN")
      (footprint "BNC_RA CON")
      (description "BNC Elbow Connector")
      (fields (field (name "PUBLISHER") "Altium Limited"))
      (libsource (lib "Miscellaneous Connectors") (part "BNC"))
    )
    (comp (ref "P2")
      (value "PMT")
      (footprint "BNC_RA CON")
      (description "BNC Elbow Connector")
      (fields (field (name "PUBLISHER") "Altium Limited"))
      (libsource (lib "Miscellaneous Connectors") (part "BNC"))
    )
    (comp (ref "P3")
      (value "TRIGGER")
      (footprint "BNC_RA CON")
      (description "BNC Elbow Connector")
      (fields (field (name "PUBLISHER") "Altium Limited"))
      (libsource (lib "Miscellaneous Connectors") (part "BNC"))
    )
    (comp (ref "P4")
      (value "AUX")
      (footprint "BNC_RA CON")
      (description "BNC Elbow Connector")
      (fields (field (name "PUBLISHER") "Altium Limited"))
      (libsource (lib "Miscellaneous Connectors") (part "BNC"))
    )
    (comp (ref "P5")
      (value "TTL_OUT_1")
      (footprint "HDR2X20")
      (description "Header, 20-Pin, Dual row")
      (fields (field (name "PUBLISHER") "Altium Limited"))
      (libsource (lib "Miscellaneous Connectors") (part "Header 20X2"))
    )
    (comp (ref "P6")
      (value "AUX_I/O")
      (footprint "HDR2X10")
      (description "Header, 10-Pin, Dual row")
      (fields (field (name "PUBLISHER") "Altium Limited"))
      (libsource (lib "Miscellaneous Connectors") (part "Header 10X2"))
    )
    (comp (ref "P7")
      (value "JP2A")
      (footprint "connector_40pos_2mm")
      (description "2 mm connector 40 positions")
      (fields (field (name "PUBLISHER") "Altium Limited"))
      (libsource (lib "HH_chips") (part "CONN_40_2mm"))
    )
    (comp (ref "P8")
      (value "JP3A")
      (footprint "connector_40pos_2mm")
      (description "2 mm connector 40 positions")
      (fields (field (name "PUBLISHER") "Altium Limited"))
      (libsource (lib "HH_chips") (part "CONN_40_2mm"))
    )
    (comp (ref "P9")
      (value "JP2B")
      (footprint "connector_40pos_2mm")
      (description "2 mm connector 40 positions")
      (fields (field (name "PUBLISHER") "Altium Limited"))
      (libsource (lib "HH_chips") (part "CONN_40_2mm"))
    )
    (comp (ref "P10")
      (value "JP3B")
      (footprint "connector_40pos_2mm")
      (description "2 mm connector 40 positions")
      (fields (field (name "PUBLISHER") "Altium Limited"))
      (libsource (lib "HH_chips") (part "CONN_40_2mm"))
    )
    (comp (ref "R1")
      (value "100")
      (footprint "RESC3216L")
      (description "Resistor")
      (fields (field (name "PUBLISHER") "Altium Limited"))
      (libsource (lib "Miscellaneous Devices") (part "Res3"))
    )
    (comp (ref "R2")
      (value "100")
      (footprint "RESC3216L")
      (description "Resistor")
      (fields (field (name "PUBLISHER") "Altium Limited"))
      (libsource (lib "Miscellaneous Devices") (part "Res3"))
    )
    (comp (ref "R3")
      (value "100")
      (footprint "RESC3216L")
      (description "Resistor")
      (fields (field (name "PUBLISHER") "Altium Limited"))
      (libsource (lib "Miscellaneous Devices") (part "Res3"))
    )
    (comp (ref "R4")
      (value "100")
      (footprint "RESC3216L")
      (description "Resistor")
      (fields (field (name "PUBLISHER") "Altium Limited"))
      (libsource (lib "Miscellaneous Devices") (part "Res3"))
    )
    (comp (ref "R5")
      (value "100")
      (footprint "RESC3216L")
      (description "Resistor")
      (fields (field (name "PUBLISHER") "Altium Limited"))
      (libsource (lib "Miscellaneous Devices") (part "Res3"))
    )
    (comp (ref "R6")
      (value "100")
      (footprint "RESC3216L")
      (description "Resistor")
      (fields (field (name "PUBLISHER") "Altium Limited"))
      (libsource (lib "Miscellaneous Devices") (part "Res3"))
    )
    (comp (ref "R7")
      (value "100")
      (footprint "RESC3216L")
      (description "Resistor")
      (fields (field (name "PUBLISHER") "Altium Limited"))
      (libsource (lib "Miscellaneous Devices") (part "Res3"))
    )
    (comp (ref "R8")
      (value "100")
      (footprint "RESC3216L")
      (description "Resistor")
      (fields (field (name "PUBLISHER") "Altium Limited"))
      (libsource (lib "Miscellaneous Devices") (part "Res3"))
    )
    (comp (ref "R9")
      (value "100")
      (footprint "RESC3216L")
      (description "Resistor")
      (fields (field (name "PUBLISHER") "Altium Limited"))
      (libsource (lib "Miscellaneous Devices") (part "Res3"))
    )
    (comp (ref "R10")
      (value "100")
      (footprint "RESC3216L")
      (description "Resistor")
      (fields (field (name "PUBLISHER") "Altium Limited"))
      (libsource (lib "Miscellaneous Devices") (part "Res3"))
    )
    (comp (ref "R11")
      (value "100")
      (footprint "RESC3216L")
      (description "Resistor")
      (fields (field (name "PUBLISHER") "Altium Limited"))
      (libsource (lib "Miscellaneous Devices") (part "Res3"))
    )
    (comp (ref "R12")
      (value "100")
      (footprint "RESC3216L")
      (description "Resistor")
      (fields (field (name "PUBLISHER") "Altium Limited"))
      (libsource (lib "Miscellaneous Devices") (part "Res3"))
    )
    (comp (ref "R13")
      (value "100")
      (footprint "RESC3216L")
      (description "Resistor")
      (fields (field (name "PUBLISHER") "Altium Limited"))
      (libsource (lib "Miscellaneous Devices") (part "Res3"))
    )
    (comp (ref "R14")
      (value "100")
      (footprint "RESC3216L")
      (description "Resistor")
      (fields (field (name "PUBLISHER") "Altium Limited"))
      (libsource (lib "Miscellaneous Devices") (part "Res3"))
    )
    (comp (ref "R15")
      (value "100")
      (footprint "RESC3216L")
      (description "Resistor")
      (fields (field (name "PUBLISHER") "Altium Limited"))
      (libsource (lib "Miscellaneous Devices") (part "Res3"))
    )
    (comp (ref "R16")
      (value "100")
      (footprint "RESC3216L")
      (description "Resistor")
      (fields (field (name "PUBLISHER") "Altium Limited"))
      (libsource (lib "Miscellaneous Devices") (part "Res3"))
    )
    (comp (ref "R17")
      (value "100")
      (footprint "RESC3216L")
      (description "Resistor")
      (fields (field (name "PUBLISHER") "Altium Limited"))
      (libsource (lib "Miscellaneous Devices") (part "Res3"))
    )
    (comp (ref "R18")
      (value "100")
      (footprint "RESC3216L")
      (description "Resistor")
      (fields (field (name "PUBLISHER") "Altium Limited"))
      (libsource (lib "Miscellaneous Devices") (part "Res3"))
    )
    (comp (ref "R19")
      (value "100")
      (footprint "RESC3216L")
      (description "Resistor")
      (fields (field (name "PUBLISHER") "Altium Limited"))
      (libsource (lib "Miscellaneous Devices") (part "Res3"))
    )
    (comp (ref "R20")
      (value "100")
      (footprint "RESC3216L")
      (description "Resistor")
      (fields (field (name "PUBLISHER") "Altium Limited"))
      (libsource (lib "Miscellaneous Devices") (part "Res3"))
    )
    (comp (ref "R21")
      (value "100")
      (footprint "RESC3216L")
      (description "Resistor")
      (fields (field (name "PUBLISHER") "Altium Limited"))
      (libsource (lib "Miscellaneous Devices") (part "Res3"))
    )
    (comp (ref "R22")
      (value "100")
      (footprint "RESC3216L")
      (description "Resistor")
      (fields (field (name "PUBLISHER") "Altium Limited"))
      (libsource (lib "Miscellaneous Devices") (part "Res3"))
    )
    (comp (ref "R23")
      (value "100")
      (footprint "RESC3216L")
      (description "Resistor")
      (fields (field (name "PUBLISHER") "Altium Limited"))
      (libsource (lib "Miscellaneous Devices") (part "Res3"))
    )
    (comp (ref "R24")
      (value "100")
      (footprint "RESC3216L")
      (description "Resistor")
      (fields (field (name "PUBLISHER") "Altium Limited"))
      (libsource (lib "Miscellaneous Devices") (part "Res3"))
    )
    (comp (ref "R25")
      (value "100")
      (footprint "RESC3216L")
      (description "Resistor")
      (fields (field (name "PUBLISHER") "Altium Limited"))
      (libsource (lib "Miscellaneous Devices") (part "Res3"))
    )
    (comp (ref "R26")
      (value "100")
      (footprint "RESC3216L")
      (description "Resistor")
      (fields (field (name "PUBLISHER") "Altium Limited"))
      (libsource (lib "Miscellaneous Devices") (part "Res3"))
    )
    (comp (ref "R27")
      (value "100")
      (footprint "RESC3216L")
      (description "Resistor")
      (fields (field (name "PUBLISHER") "Altium Limited"))
      (libsource (lib "Miscellaneous Devices") (part "Res3"))
    )
    (comp (ref "R28")
      (value "100")
      (footprint "RESC3216L")
      (description "Resistor")
      (fields (field (name "PUBLISHER") "Altium Limited"))
      (libsource (lib "Miscellaneous Devices") (part "Res3"))
    )
    (comp (ref "R29")
      (value "100")
      (footprint "RESC3216L")
      (description "Resistor")
      (fields (field (name "PUBLISHER") "Altium Limited"))
      (libsource (lib "Miscellaneous Devices") (part "Res3"))
    )
    (comp (ref "R30")
      (value "100")
      (footprint "RESC3216L")
      (description "Resistor")
      (fields (field (name "PUBLISHER") "Altium Limited"))
      (libsource (lib "Miscellaneous Devices") (part "Res3"))
    )
    (comp (ref "R31")
      (value "100")
      (footprint "RESC3216L")
      (description "Resistor")
      (fields (field (name "PUBLISHER") "Altium Limited"))
      (libsource (lib "Miscellaneous Devices") (part "Res3"))
    )
    (comp (ref "R32")
      (value "100")
      (footprint "RESC3216L")
      (description "Resistor")
      (fields (field (name "PUBLISHER") "Altium Limited"))
      (libsource (lib "Miscellaneous Devices") (part "Res3"))
    )
    (comp (ref "R33")
      (value "100")
      (footprint "RESC3216L")
      (description "Resistor")
      (fields (field (name "PUBLISHER") "Altium Limited"))
      (libsource (lib "Miscellaneous Devices") (part "Res3"))
    )
    (comp (ref "R34")
      (value "100")
      (footprint "RESC3216L")
      (description "Resistor")
      (fields (field (name "PUBLISHER") "Altium Limited"))
      (libsource (lib "Miscellaneous Devices") (part "Res3"))
    )
    (comp (ref "R35")
      (value "100")
      (footprint "RESC3216L")
      (description "Resistor")
      (fields (field (name "PUBLISHER") "Altium Limited"))
      (libsource (lib "Miscellaneous Devices") (part "Res3"))
    )
    (comp (ref "R36")
      (value "100")
      (footprint "RESC3216L")
      (description "Resistor")
      (fields (field (name "PUBLISHER") "Altium Limited"))
      (libsource (lib "Miscellaneous Devices") (part "Res3"))
    )
    (comp (ref "R37")
      (value "100")
      (footprint "RESC3216L")
      (description "Resistor")
      (fields (field (name "PUBLISHER") "Altium Limited"))
      (libsource (lib "Miscellaneous Devices") (part "Res3"))
    )
    (comp (ref "R38")
      (value "100")
      (footprint "RESC3216L")
      (description "Resistor")
      (fields (field (name "PUBLISHER") "Altium Limited"))
      (libsource (lib "Miscellaneous Devices") (part "Res3"))
    )
    (comp (ref "R39")
      (value "100")
      (footprint "RESC3216L")
      (description "Resistor")
      (fields (field (name "PUBLISHER") "Altium Limited"))
      (libsource (lib "Miscellaneous Devices") (part "Res3"))
    )
    (comp (ref "R40")
      (value "100")
      (footprint "RESC3216L")
      (description "Resistor")
      (fields (field (name "PUBLISHER") "Altium Limited"))
      (libsource (lib "Miscellaneous Devices") (part "Res3"))
    )
    (comp (ref "R41")
      (value "750")
      (footprint "RESC2012M")
      (description "Resistor")
      (fields (field (name "Comment") "Res3") (field (name "PUBLISHER") "Altium Limited"))
      (libsource (lib "Miscellaneous Devices") (part "Res3"))
    )
    (comp (ref "R42")
      (value "750")
      (footprint "RESC2012M")
      (description "Resistor")
      (fields (field (name "Comment") "Res3") (field (name "PUBLISHER") "Altium Limited"))
      (libsource (lib "Miscellaneous Devices") (part "Res3"))
    )
    (comp (ref "R43")
      (value "750")
      (footprint "RESC2012M")
      (description "Resistor")
      (fields (field (name "Comment") "Res3") (field (name "PUBLISHER") "Altium Limited"))
      (libsource (lib "Miscellaneous Devices") (part "Res3"))
    )
    (comp (ref "R44")
      (value "750")
      (footprint "RESC2012M")
      (description "Resistor")
      (fields (field (name "Comment") "Res3") (field (name "PUBLISHER") "Altium Limited"))
      (libsource (lib "Miscellaneous Devices") (part "Res3"))
    )
    (comp (ref "R45")
      (value "750")
      (footprint "RESC2012M")
      (description "Resistor")
      (fields (field (name "Comment") "Res3") (field (name "PUBLISHER") "Altium Limited"))
      (libsource (lib "Miscellaneous Devices") (part "Res3"))
    )
    (comp (ref "R46")
      (value "750")
      (footprint "RESC2012M")
      (description "Resistor")
      (fields (field (name "Comment") "Res3") (field (name "PUBLISHER") "Altium Limited"))
      (libsource (lib "Miscellaneous Devices") (part "Res3"))
    )
    (comp (ref "R47")
      (value "750")
      (footprint "RESC2012M")
      (description "Resistor")
      (fields (field (name "Comment") "Res3") (field (name "PUBLISHER") "Altium Limited"))
      (libsource (lib "Miscellaneous Devices") (part "Res3"))
    )
    (comp (ref "R48")
      (value "750")
      (footprint "RESC2012M")
      (description "Resistor")
      (fields (field (name "Comment") "Res3") (field (name "PUBLISHER") "Altium Limited"))
      (libsource (lib "Miscellaneous Devices") (part "Res3"))
    )
    (comp (ref "U1")
      (value "MAX3094, Rx")
      (footprint "NSO16_N")
      (description "Differential Line Receivers")
      (libsource (lib "HH_chips") (part "MAX3094"))
    )
    (comp (ref "U2")
      (value "MAX3094, Rx")
      (footprint "NSO16_N")
      (description "Differential Line Receivers")
      (libsource (lib "HH_chips") (part "MAX3094"))
    )
    (comp (ref "U3")
      (value "MAX3030, Tx")
      (footprint "NSO16_N")
      (description "Differential Line Transmitter")
      (libsource (lib "HH_chips") (part "MAX3030"))
    )
    (comp (ref "U4")
      (value "MAX3030, Tx")
      (footprint "NSO16_N")
      (description "Differential Line Transmitter")
      (libsource (lib "HH_chips") (part "MAX3030"))
    )
    (comp (ref "U5")
      (value "MAX3030, Tx")
      (footprint "NSO16_N")
      (description "Differential Line Transmitter")
      (libsource (lib "HH_chips") (part "MAX3030"))
    )
    (comp (ref "U6")
      (value "MAX3030, Tx")
      (footprint "NSO16_N")
      (description "Differential Line Transmitter")
      (libsource (lib "HH_chips") (part "MAX3030"))
    )
    (comp (ref "U7")
      (value "MAX3030, Tx")
      (footprint "NSO16_N")
      (description "Differential Line Transmitter")
      (libsource (lib "HH_chips") (part "MAX3030"))
    )
    (comp (ref "U8")
      (value "MAX3030, Tx")
      (footprint "NSO16_N")
      (description "Differential Line Transmitter")
      (libsource (lib "HH_chips") (part "MAX3030"))
    )
    (comp (ref "U9")
      (value "MAX3030, Tx")
      (footprint "NSO16_N")
      (description "Differential Line Transmitter")
      (libsource (lib "HH_chips") (part "MAX3030"))
    )
    (comp (ref "U10")
      (value "MAX3030, Tx")
      (footprint "NSO16_N")
      (description "Differential Line Transmitter")
      (libsource (lib "HH_chips") (part "MAX3030"))
    )
    (comp (ref "U11")
      (value "ZEM4310")
      (footprint "ZEM4310")
      (description "ZEM4310 breakout module")
      (libsource (lib "HH_chips") (part "ZEM4310"))
    )
    (comp (ref "U12")
      (value "SN74LVC1T45")
      (footprint "SOT23-6")
      (description "Logic Translator (Bidirectional)")
      (libsource (lib "HH_chips") (part "SN74LVC1T45"))
    )
    (comp (ref "U13")
      (value "SN74LVC1T45")
      (footprint "SOT23-6")
      (description "Logic Translator (Bidirectional)")
      (libsource (lib "HH_chips") (part "SN74LVC1T45"))
    )
    (comp (ref "U14")
      (value "SN74LVC1T45")
      (footprint "SOT23-6")
      (description "Logic Translator (Bidirectional)")
      (libsource (lib "HH_chips") (part "SN74LVC1T45"))
    )
    (comp (ref "U15")
      (value "SN74LVC1T45")
      (footprint "SOT23-6")
      (description "Logic Translator (Bidirectional)")
      (libsource (lib "HH_chips") (part "SN74LVC1T45"))
    )
  )
  (nets
    (net (code "1") (name "/AUX_CLK_IN") (class "Default")
      (node (ref "P9") (pin "37") (pinfunction "37_37") (pintype "passive"))
      (node (ref "U11") (pin "1A11") (pinfunction "G1/CLKIN_1A11") (pintype "passive"))
      (node (ref "U12") (pin "4") (pinfunction "B_4") (pintype "passive"))
    )
    (net (code "2") (name "/AUX_IN_1") (class "Default")
      (node (ref "P9") (pin "32") (pinfunction "32_32") (pintype "passive"))
      (node (ref "U11") (pin "1C20") (pinfunction "P17/R30p_1C20") (pintype "passive"))
      (node (ref "U15") (pin "4") (pinfunction "B_4") (pintype "passive"))
    )
    (net (code "3") (name "/AUX_IO_0") (class "Default")
      (node (ref "P6") (pin "2") (pinfunction "2_2") (pintype "passive"))
      (node (ref "P8") (pin "38") (pinfunction "38_38") (pintype "passive"))
      (node (ref "U11") (pin "2C3") (pinfunction "H21/R14p_2C3") (pintype "passive"))
    )
    (net (code "4") (name "/AUX_IO_1") (class "Default")
      (node (ref "P6") (pin "3") (pinfunction "3_3") (pintype "passive"))
      (node (ref "P8") (pin "37") (pinfunction "37_37") (pintype "passive"))
      (node (ref "U11") (pin "2C4") (pinfunction "W17/B38p_2C4") (pintype "passive"))
    )
    (net (code "5") (name "/AUX_IO_2") (class "Default")
      (node (ref "P6") (pin "4") (pinfunction "4_4") (pintype "passive"))
      (node (ref "P8") (pin "34") (pinfunction "34_34") (pintype "passive"))
      (node (ref "U11") (pin "2C5") (pinfunction "H22/R14n_2C5") (pintype "passive"))
    )
    (net (code "6") (name "/AUX_IO_3") (class "Default")
      (node (ref "P6") (pin "5") (pinfunction "5_5") (pintype "passive"))
      (node (ref "P8") (pin "33") (pinfunction "33_33") (pintype "passive"))
      (node (ref "U11") (pin "2C6") (pinfunction "Y17/B38n_2C6") (pintype "passive"))
    )
    (net (code "7") (name "/AUX_IO_4") (class "Default")
      (node (ref "P6") (pin "6") (pinfunction "6_6") (pintype "passive"))
      (node (ref "P8") (pin "32") (pinfunction "32_32") (pintype "passive"))
      (node (ref "U11") (pin "2C7") (pinfunction "E21/R8p_2C7") (pintype "passive"))
    )
    (net (code "8") (name "/AUX_IO_5") (class "Default")
      (node (ref "P6") (pin "7") (pinfunction "7_7") (pintype "passive"))
      (node (ref "P8") (pin "31") (pinfunction "31_31") (pintype "passive"))
      (node (ref "U11") (pin "2C8") (pinfunction "P21/R23p_2C8") (pintype "passive"))
    )
    (net (code "9") (name "/AUX_IO_6") (class "Default")
      (node (ref "P6") (pin "8") (pinfunction "8_8") (pintype "passive"))
      (node (ref "P8") (pin "30") (pinfunction "30_30") (pintype "passive"))
      (node (ref "U11") (pin "2C9") (pinfunction "E22/R8n_2C9") (pintype "passive"))
    )
    (net (code "10") (name "/AUX_IO_7") (class "Default")
      (node (ref "P6") (pin "9") (pinfunction "9_9") (pintype "passive"))
      (node (ref "P8") (pin "29") (pinfunction "29_29") (pintype "passive"))
      (node (ref "U11") (pin "2C10") (pinfunction "P22/R23n_2C10") (pintype "passive"))
    )
    (net (code "11") (name "/AUX_IO_8") (class "Default")
      (node (ref "P6") (pin "10") (pinfunction "10_10") (pintype "passive"))
      (node (ref "P8") (pin "28") (pinfunction "28_28") (pintype "passive"))
      (node (ref "U11") (pin "2C11") (pinfunction "F19/R6p_2C11") (pintype "passive"))
    )
    (net (code "12") (name "/AUX_IO_9") (class "Default")
      (node (ref "P6") (pin "11") (pinfunction "11_11") (pintype "passive"))
      (node (ref "P8") (pin "27") (pinfunction "27_27") (pintype "passive"))
      (node (ref "U11") (pin "2C12") (pinfunction "U16/B40p_2C12") (pintype "passive"))
    )
    (net (code "13") (name "/AUX_IO_10") (class "Default")
      (node (ref "P6") (pin "12") (pinfunction "12_12") (pintype "passive"))
      (node (ref "P8") (pin "26") (pinfunction "26_26") (pintype "passive"))
      (node (ref "U11") (pin "2C13") (pinfunction "F20/R6n_2C13") (pintype "passive"))
    )
    (net (code "14") (name "/AUX_IO_11") (class "Default")
      (node (ref "P6") (pin "13") (pinfunction "13_13") (pintype "passive"))
      (node (ref "P8") (pin "25") (pinfunction "25_25") (pintype "passive"))
      (node (ref "U11") (pin "2C14") (pinfunction "U17/B40n_2C14") (pintype "passive"))
    )
    (net (code "15") (name "/AUX_IO_12") (class "Default")
      (node (ref "P6") (pin "14") (pinfunction "14_14") (pintype "passive"))
      (node (ref "P8") (pin "24") (pinfunction "24_24") (pintype "passive"))
      (node (ref "U11") (pin "2C15") (pinfunction "D21/R7p_2C15") (pintype "passive"))
    )
    (net (code "16") (name "/AUX_IO_13") (class "Default")
      (node (ref "P6") (pin "15") (pinfunction "15_15") (pintype "passive"))
      (node (ref "P8") (pin "23") (pinfunction "23_23") (pintype "passive"))
      (node (ref "U11") (pin "2C16") (pinfunction "T14/B36p_2C16") (pintype "passive"))
    )
    (net (code "17") (name "/AUX_IO_14") (class "Default")
      (node (ref "P6") (pin "16") (pinfunction "16_16") (pintype "passive"))
      (node (ref "P8") (pin "22") (pinfunction "22_22") (pintype "passive"))
      (node (ref "U11") (pin "2C17") (pinfunction "D22/R7n_2C17") (pintype "passive"))
    )
    (net (code "18") (name "/AUX_IO_15") (class "Default")
      (node (ref "P6") (pin "17") (pinfunction "17_17") (pintype "passive"))
      (node (ref "P8") (pin "21") (pinfunction "21_21") (pintype "passive"))
      (node (ref "U11") (pin "2C18") (pinfunction "T15/B36n_2C18") (pintype "passive"))
    )
    (net (code "19") (name "/AUX_IO_16") (class "Default")
      (node (ref "P6") (pin "18") (pinfunction "18_18") (pintype "passive"))
      (node (ref "P8") (pin "20") (pinfunction "20_20") (pintype "passive"))
      (node (ref "U11") (pin "2C19") (pinfunction "C21/R4p_2C19") (pintype "passive"))
    )
    (net (code "20") (name "/AUX_IO_17") (class "Default")
      (node (ref "P6") (pin "19") (pinfunction "19_19") (pintype "passive"))
      (node (ref "P8") (pin "19") (pinfunction "19_19") (pintype "passive"))
      (node (ref "U11") (pin "2C20") (pinfunction "N19/R22p_2C20") (pintype "passive"))
    )
    (net (code "21") (name "/LED_0") (class "Default")
      (node (ref "D1") (pin "1") (pinfunction "A_1") (pintype "passive"))
      (node (ref "U11") (pin "1C4") (pinfunction "AA9/B18p_1C4") (pintype "passive"))
    )
    (net (code "22") (name "/LED_1") (class "Default")
      (node (ref "D3") (pin "1") (pinfunction "A_1") (pintype "passive"))
      (node (ref "U11") (pin "1C5") (pinfunction "R3/L27n_1C5") (pintype "passive"))
    )
    (net (code "23") (name "/LED_2") (class "Default")
      (node (ref "D5") (pin "1") (pinfunction "A_1") (pintype "passive"))
      (node (ref "U11") (pin "1C6") (pinfunction "AB9/B19n_1C6") (pintype "passive"))
    )
    (net (code "24") (name "/LED_3") (class "Default")
      (node (ref "D7") (pin "1") (pinfunction "A_1") (pintype "passive"))
      (node (ref "U11") (pin "1C7") (pinfunction "W2/L28p_1C7") (pintype "passive"))
    )
    (net (code "25") (name "/LED_4") (class "Default")
      (node (ref "D2") (pin "1") (pinfunction "A_1") (pintype "passive"))
      (node (ref "U11") (pin "1C8") (pinfunction "W10/B20p_1C8") (pintype "passive"))
    )
    (net (code "26") (name "/LED_5") (class "Default")
      (node (ref "D4") (pin "1") (pinfunction "A_1") (pintype "passive"))
      (node (ref "U11") (pin "1C9") (pinfunction "W1/L28n_1C9") (pintype "passive"))
    )
    (net (code "27") (name "/LED_6") (class "Default")
      (node (ref "D6") (pin "1") (pinfunction "A_1") (pintype "passive"))
      (node (ref "U11") (pin "1C10") (pinfunction "Y10/B20n_1C10") (pintype "passive"))
    )
    (net (code "28") (name "/LED_7") (class "Default")
      (node (ref "D8") (pin "1") (pinfunction "A_1") (pintype "passive"))
      (node (ref "U11") (pin "1C11") (pinfunction "Y2/L29p_1C11") (pintype "passive"))
    )
    (net (code "29") (name "/PMT_IN") (class "Default")
      (node (ref "P9") (pin "36") (pinfunction "36_36") (pintype "passive"))
      (node (ref "U11") (pin "1C16") (pinfunction "AA10/B21p_1C16") (pintype "passive"))
      (node (ref "U13") (pin "4") (pinfunction "B_4") (pintype "passive"))
    )
    (net (code "30") (name "/TRIGGER_IN") (class "Default")
      (node (ref "P9") (pin "34") (pinfunction "34_34") (pintype "passive"))
      (node (ref "U11") (pin "1C18") (pinfunction "AB10/B21n_1C18") (pintype "passive"))
      (node (ref "U14") (pin "4") (pinfunction "B_4") (pintype "passive"))
    )
    (net (code "31") (name "/TTL_OUT_0") (class "Default")
      (node (ref "P5") (pin "2") (pinfunction "2_2") (pintype "passive"))
      (node (ref "U11") (pin "2B3") (pinfunction "H17/R5p_2B3") (pintype "passive"))
    )
    (net (code "32") (name "/TTL_OUT_1") (class "Default")
      (node (ref "P5") (pin "3") (pinfunction "3_3") (pintype "passive"))
      (node (ref "U11") (pin "2B4") (pinfunction "AA14/B25p_2B4") (pintype "passive"))
    )
    (net (code "33") (name "/TTL_OUT_2") (class "Default")
      (node (ref "P10") (pin "36") (pinfunction "36_36") (pintype "passive"))
      (node (ref "P5") (pin "4") (pinfunction "4_4") (pintype "passive"))
      (node (ref "U11") (pin "2B5") (pinfunction "G18/R5n_2B5") (pintype "passive"))
    )
    (net (code "34") (name "/TTL_OUT_3") (class "Default")
      (node (ref "P10") (pin "35") (pinfunction "35_35") (pintype "passive"))
      (node (ref "P5") (pin "5") (pinfunction "5_5") (pintype "passive"))
      (node (ref "U11") (pin "2B6") (pinfunction "AB14/B25n_2B6") (pintype "passive"))
    )
    (net (code "35") (name "/TTL_OUT_4") (class "Default")
      (node (ref "P10") (pin "34") (pinfunction "34_34") (pintype "passive"))
      (node (ref "P5") (pin "6") (pinfunction "6_6") (pintype "passive"))
      (node (ref "U11") (pin "2B7") (pinfunction "K18/R13p_2B7") (pintype "passive"))
    )
    (net (code "36") (name "/TTL_OUT_5") (class "Default")
      (node (ref "P10") (pin "33") (pinfunction "33_33") (pintype "passive"))
      (node (ref "P5") (pin "7") (pinfunction "7_7") (pintype "passive"))
      (node (ref "U11") (pin "2B8") (pinfunction "W13/B26p_2B8") (pintype "passive"))
    )
    (net (code "37") (name "/TTL_OUT_6") (class "Default")
      (node (ref "P10") (pin "32") (pinfunction "32_32") (pintype "passive"))
      (node (ref "P5") (pin "8") (pinfunction "8_8") (pintype "passive"))
      (node (ref "U11") (pin "2B9") (pinfunction "K17/R13n_2B9") (pintype "passive"))
    )
    (net (code "38") (name "/TTL_OUT_7") (class "Default")
      (node (ref "P10") (pin "31") (pinfunction "31_31") (pintype "passive"))
      (node (ref "P5") (pin "9") (pinfunction "9_9") (pintype "passive"))
      (node (ref "U11") (pin "2B10") (pinfunction "Y13/B26n_2B10") (pintype "passive"))
    )
    (net (code "39") (name "/TTL_OUT_8") (class "Default")
      (node (ref "P10") (pin "30") (pinfunction "30_30") (pintype "passive"))
      (node (ref "P5") (pin "10") (pinfunction "10_10") (pintype "passive"))
      (node (ref "U11") (pin "2B11") (pinfunction "M19/R18p_2B11") (pintype "passive"))
    )
    (net (code "40") (name "/TTL_OUT_9") (class "Default")
      (node (ref "P10") (pin "29") (pinfunction "29_29") (pintype "passive"))
      (node (ref "P5") (pin "11") (pinfunction "11_11") (pintype "passive"))
      (node (ref "U11") (pin "2B12") (pinfunction "AA15/B27p_2B12") (pintype "passive"))
    )
    (net (code "41") (name "/TTL_OUT_10") (class "Default")
      (node (ref "P10") (pin "28") (pinfunction "28_28") (pintype "passive"))
      (node (ref "P5") (pin "12") (pinfunction "12_12") (pintype "passive"))
      (node (ref "U11") (pin "2B13") (pinfunction "M20/R18n_2B13") (pintype "passive"))
    )
    (net (code "42") (name "/TTL_OUT_11") (class "Default")
      (node (ref "P10") (pin "27") (pinfunction "27_27") (pintype "passive"))
      (node (ref "P5") (pin "13") (pinfunction "13_13") (pintype "passive"))
      (node (ref "U11") (pin "2B14") (pinfunction "AB15/B27n_2B14") (pintype "passive"))
    )
    (net (code "43") (name "/TTL_OUT_12") (class "Default")
      (node (ref "P10") (pin "26") (pinfunction "26_26") (pintype "passive"))
      (node (ref "P5") (pin "14") (pinfunction "14_14") (pintype "passive"))
      (node (ref "U11") (pin "2B15") (pinfunction "N21/R20p_2B15") (pintype "passive"))
    )
    (net (code "44") (name "/TTL_OUT_13") (class "Default")
      (node (ref "P10") (pin "25") (pinfunction "25_25") (pintype "passive"))
      (node (ref "P5") (pin "15") (pinfunction "15_15") (pintype "passive"))
      (node (ref "U11") (pin "2B16") (pinfunction "AA16/B30p_2B16") (pintype "passive"))
    )
    (net (code "45") (name "/TTL_OUT_14") (class "Default")
      (node (ref "P10") (pin "24") (pinfunction "24_24") (pintype "passive"))
      (node (ref "P5") (pin "16") (pinfunction "16_16") (pintype "passive"))
      (node (ref "U11") (pin "2B17") (pinfunction "N22/R20n_2B17") (pintype "passive"))
    )
    (net (code "46") (name "/TTL_OUT_15") (class "Default")
      (node (ref "P10") (pin "23") (pinfunction "23_23") (pintype "passive"))
      (node (ref "P5") (pin "17") (pinfunction "17_17") (pintype "passive"))
      (node (ref "U11") (pin "2B18") (pinfunction "AB16/B30n_2B18") (pintype "passive"))
    )
    (net (code "47") (name "/TTL_OUT_16") (class "Default")
      (node (ref "P10") (pin "22") (pinfunction "22_22") (pintype "passive"))
      (node (ref "P5") (pin "18") (pinfunction "18_18") (pintype "passive"))
      (node (ref "U11") (pin "2B19") (pinfunction "H19/R9p_2B19") (pintype "passive"))
    )
    (net (code "48") (name "/TTL_OUT_17") (class "Default")
      (node (ref "P10") (pin "21") (pinfunction "21_21") (pintype "passive"))
      (node (ref "P5") (pin "19") (pinfunction "19_19") (pintype "passive"))
      (node (ref "U11") (pin "2B20") (pinfunction "AA17/B37p_2B20") (pintype "passive"))
    )
    (net (code "49") (name "/TTL_OUT_18") (class "Default")
      (node (ref "P10") (pin "20") (pinfunction "20_20") (pintype "passive"))
      (node (ref "P5") (pin "20") (pinfunction "20_20") (pintype "passive"))
      (node (ref "U11") (pin "2B21") (pinfunction "H20/R9n_2B21") (pintype "passive"))
    )
    (net (code "50") (name "/TTL_OUT_19") (class "Default")
      (node (ref "P10") (pin "19") (pinfunction "19_19") (pintype "passive"))
      (node (ref "P5") (pin "21") (pinfunction "21_21") (pintype "passive"))
      (node (ref "U11") (pin "2B22") (pinfunction "AB17/B37n_2B22") (pintype "passive"))
    )
    (net (code "51") (name "/TTL_OUT_20") (class "Default")
      (node (ref "P10") (pin "18") (pinfunction "18_18") (pintype "passive"))
      (node (ref "P5") (pin "22") (pinfunction "22_22") (pintype "passive"))
      (node (ref "U11") (pin "2B23") (pinfunction "M21/R19p_2B23") (pintype "passive"))
    )
    (net (code "52") (name "/TTL_OUT_21") (class "Default")
      (node (ref "P10") (pin "17") (pinfunction "17_17") (pintype "passive"))
      (node (ref "P5") (pin "23") (pinfunction "23_23") (pintype "passive"))
      (node (ref "U11") (pin "2B24") (pinfunction "AA20/B39p_2B24") (pintype "passive"))
    )
    (net (code "53") (name "/TTL_OUT_22") (class "Default")
      (node (ref "P10") (pin "14") (pinfunction "14_14") (pintype "passive"))
      (node (ref "P5") (pin "24") (pinfunction "24_24") (pintype "passive"))
      (node (ref "U11") (pin "2B25") (pinfunction "M22/R19n_2B25") (pintype "passive"))
    )
    (net (code "54") (name "/TTL_OUT_23") (class "Default")
      (node (ref "P10") (pin "13") (pinfunction "13_13") (pintype "passive"))
      (node (ref "P5") (pin "25") (pinfunction "25_25") (pintype "passive"))
      (node (ref "U11") (pin "2B26") (pinfunction "AB20/B39n_2B26") (pintype "passive"))
    )
    (net (code "55") (name "/TTL_OUT_24") (class "Default")
      (node (ref "P10") (pin "12") (pinfunction "12_12") (pintype "passive"))
      (node (ref "P5") (pin "26") (pinfunction "26_26") (pintype "passive"))
      (node (ref "U11") (pin "2B27") (pinfunction "J21/R15p_2B27") (pintype "passive"))
    )
    (net (code "56") (name "/TTL_OUT_25") (class "Default")
      (node (ref "P10") (pin "11") (pinfunction "11_11") (pintype "passive"))
      (node (ref "P5") (pin "27") (pinfunction "27_27") (pintype "passive"))
      (node (ref "U11") (pin "2B28") (pinfunction "Y14/B29p_2B28") (pintype "passive"))
    )
    (net (code "57") (name "/TTL_OUT_26") (class "Default")
      (node (ref "P10") (pin "10") (pinfunction "10_10") (pintype "passive"))
      (node (ref "P5") (pin "28") (pinfunction "28_28") (pintype "passive"))
      (node (ref "U11") (pin "2B29") (pinfunction "J22/R15n_2B29") (pintype "passive"))
    )
    (net (code "58") (name "/TTL_OUT_27") (class "Default")
      (node (ref "P10") (pin "9") (pinfunction "9_9") (pintype "passive"))
      (node (ref "P5") (pin "29") (pinfunction "29_29") (pintype "passive"))
      (node (ref "U11") (pin "2B30") (pinfunction "Y15/B29n_2B30") (pintype "passive"))
    )
    (net (code "59") (name "/TTL_OUT_28") (class "Default")
      (node (ref "P10") (pin "8") (pinfunction "8_8") (pintype "passive"))
      (node (ref "P5") (pin "30") (pinfunction "30_30") (pintype "passive"))
      (node (ref "U11") (pin "2B31") (pinfunction "R21/R24p_2B31") (pintype "passive"))
    )
    (net (code "60") (name "/TTL_OUT_29") (class "Default")
      (node (ref "P10") (pin "7") (pinfunction "7_7") (pintype "passive"))
      (node (ref "P5") (pin "31") (pinfunction "31_31") (pintype "passive"))
      (node (ref "U11") (pin "2B32") (pinfunction "L21/R17p_2B32") (pintype "passive"))
    )
    (net (code "61") (name "/TTL_OUT_30") (class "Default")
      (node (ref "P10") (pin "6") (pinfunction "6_6") (pintype "passive"))
      (node (ref "P5") (pin "32") (pinfunction "32_32") (pintype "passive"))
      (node (ref "U11") (pin "2B33") (pinfunction "R22/R24n_2B33") (pintype "passive"))
    )
    (net (code "62") (name "/TTL_OUT_31") (class "Default")
      (node (ref "P10") (pin "5") (pinfunction "5_5") (pintype "passive"))
      (node (ref "P5") (pin "33") (pinfunction "33_33") (pintype "passive"))
      (node (ref "U11") (pin "2B34") (pinfunction "L22/R17n_2B34") (pintype "passive"))
    )
    (net (code "63") (name "/TTL_OUT_32") (class "Default")
      (node (ref "P10") (pin "4") (pinfunction "4_4") (pintype "passive"))
      (node (ref "P5") (pin "34") (pinfunction "34_34") (pintype "passive"))
      (node (ref "U11") (pin "2B35") (pinfunction "F21/R11p_2B35") (pintype "passive"))
    )
    (net (code "64") (name "/TTL_OUT_33") (class "Default")
      (node (ref "P10") (pin "3") (pinfunction "3_3") (pintype "passive"))
      (node (ref "P5") (pin "35") (pinfunction "35_35") (pintype "passive"))
      (node (ref "U11") (pin "2B36") (pinfunction "V14/B33p_2B36") (pintype "passive"))
    )
    (net (code "65") (name "/TTL_OUT_34") (class "Default")
      (node (ref "P10") (pin "2") (pinfunction "2_2") (pintype "passive"))
      (node (ref "P5") (pin "36") (pinfunction "36_36") (pintype "passive"))
      (node (ref "U11") (pin "2B37") (pinfunction "F22/R11n_2B37") (pintype "passive"))
    )
    (net (code "66") (name "/TTL_OUT_35") (class "Default")
      (node (ref "P10") (pin "1") (pinfunction "1_1") (pintype "passive"))
      (node (ref "P5") (pin "37") (pinfunction "37_37") (pintype "passive"))
      (node (ref "U11") (pin "2B38") (pinfunction "U14/B33n_2B38") (pintype "passive"))
    )
    (net (code "67") (name "/bus0") (class "Default")
      (node (ref "P9") (pin "24") (pinfunction "24_24") (pintype "passive"))
      (node (ref "U10") (pin "9") (pinfunction "DI3_9") (pintype "passive"))
      (node (ref "U11") (pin "1B29") (pinfunction "U1/L24n_1B29") (pintype "passive"))
    )
    (net (code "68") (name "/bus0_n") (class "Default")
      (node (ref "J1") (pin "52") (pinfunction "A52_52") (pintype "passive"))
      (node (ref "J10") (pin "52") (pinfunction "A52_52") (pintype "passive"))
      (node (ref "J11") (pin "52") (pinfunction "A52_52") (pintype "passive"))
      (node (ref "J12") (pin "52") (pinfunction "A52_52") (pintype "passive"))
      (node (ref "J13") (pin "52") (pinfunction "A52_52") (pintype "passive"))
      (node (ref "J14") (pin "52") (pinfunction "A52_52") (pintype "passive"))
      (node (ref "J15") (pin "52") (pinfunction "A52_52") (pintype "passive"))
      (node (ref "J16") (pin "52") (pinfunction "A52_52") (pintype "passive"))
      (node (ref "J2") (pin "52") (pinfunction "A52_52") (pintype "passive"))
      (node (ref "J3") (pin "52") (pinfunction "A52_52") (pintype "passive"))
      (node (ref "J4") (pin "52") (pinfunction "A52_52") (pintype "passive"))
      (node (ref "J5") (pin "52") (pinfunction "A52_52") (pintype "passive"))
      (node (ref "J6") (pin "52") (pinfunction "A52_52") (pintype "passive"))
      (node (ref "J7") (pin "52") (pinfunction "A52_52") (pintype "passive"))
      (node (ref "J8") (pin "52") (pinfunction "A52_52") (pintype "passive"))
      (node (ref "J9") (pin "52") (pinfunction "A52_52") (pintype "passive"))
      (node (ref "R1") (pin "1") (pinfunction "1_1") (pintype "passive"))
      (node (ref "U10") (pin "10") (pinfunction "DO3+_10") (pintype "passive"))
    )
    (net (code "69") (name "/bus0_p") (class "Default")
      (node (ref "J1") (pin "51") (pinfunction "A51_51") (pintype "passive"))
      (node (ref "J10") (pin "51") (pinfunction "A51_51") (pintype "passive"))
      (node (ref "J11") (pin "51") (pinfunction "A51_51") (pintype "passive"))
      (node (ref "J12") (pin "51") (pinfunction "A51_51") (pintype "passive"))
      (node (ref "J13") (pin "51") (pinfunction "A51_51") (pintype "passive"))
      (node (ref "J14") (pin "51") (pinfunction "A51_51") (pintype "passive"))
      (node (ref "J15") (pin "51") (pinfunction "A51_51") (pintype "passive"))
      (node (ref "J16") (pin "51") (pinfunction "A51_51") (pintype "passive"))
      (node (ref "J2") (pin "51") (pinfunction "A51_51") (pintype "passive"))
      (node (ref "J3") (pin "51") (pinfunction "A51_51") (pintype "passive"))
      (node (ref "J4") (pin "51") (pinfunction "A51_51") (pintype "passive"))
      (node (ref "J5") (pin "51") (pinfunction "A51_51") (pintype "passive"))
      (node (ref "J6") (pin "51") (pinfunction "A51_51") (pintype "passive"))
      (node (ref "J7") (pin "51") (pinfunction "A51_51") (pintype "passive"))
      (node (ref "J8") (pin "51") (pinfunction "A51_51") (pintype "passive"))
      (node (ref "J9") (pin "51") (pinfunction "A51_51") (pintype "passive"))
      (node (ref "R1") (pin "2") (pinfunction "2_2") (pintype "passive"))
      (node (ref "U10") (pin "11") (pinfunction "DO3-_11") (pintype "passive"))
    )
    (net (code "70") (name "/bus1") (class "Default")
      (node (ref "P9") (pin "23") (pinfunction "23_23") (pintype "passive"))
      (node (ref "U10") (pin "15") (pinfunction "DI4_15") (pintype "passive"))
      (node (ref "U11") (pin "1B28") (pinfunction "AA8/B17p_1B28") (pintype "passive"))
    )
    (net (code "71") (name "/bus1_n") (class "Default")
      (node (ref "J1") (pin "49") (pinfunction "A49_49") (pintype "passive"))
      (node (ref "J10") (pin "49") (pinfunction "A49_49") (pintype "passive"))
      (node (ref "J11") (pin "49") (pinfunction "A49_49") (pintype "passive"))
      (node (ref "J12") (pin "49") (pinfunction "A49_49") (pintype "passive"))
      (node (ref "J13") (pin "49") (pinfunction "A49_49") (pintype "passive"))
      (node (ref "J14") (pin "49") (pinfunction "A49_49") (pintype "passive"))
      (node (ref "J15") (pin "49") (pinfunction "A49_49") (pintype "passive"))
      (node (ref "J16") (pin "49") (pinfunction "A49_49") (pintype "passive"))
      (node (ref "J2") (pin "49") (pinfunction "A49_49") (pintype "passive"))
      (node (ref "J3") (pin "49") (pinfunction "A49_49") (pintype "passive"))
      (node (ref "J4") (pin "49") (pinfunction "A49_49") (pintype "passive"))
      (node (ref "J5") (pin "49") (pinfunction "A49_49") (pintype "passive"))
      (node (ref "J6") (pin "49") (pinfunction "A49_49") (pintype "passive"))
      (node (ref "J7") (pin "49") (pinfunction "A49_49") (pintype "passive"))
      (node (ref "J8") (pin "49") (pinfunction "A49_49") (pintype "passive"))
      (node (ref "J9") (pin "49") (pinfunction "A49_49") (pintype "passive"))
      (node (ref "R2") (pin "1") (pinfunction "1_1") (pintype "passive"))
      (node (ref "U10") (pin "14") (pinfunction "DO4+_14") (pintype "passive"))
    )
    (net (code "72") (name "/bus1_p") (class "Default")
      (node (ref "J1") (pin "50") (pinfunction "A50_50") (pintype "passive"))
      (node (ref "J10") (pin "50") (pinfunction "A50_50") (pintype "passive"))
      (node (ref "J11") (pin "50") (pinfunction "A50_50") (pintype "passive"))
      (node (ref "J12") (pin "50") (pinfunction "A50_50") (pintype "passive"))
      (node (ref "J13") (pin "50") (pinfunction "A50_50") (pintype "passive"))
      (node (ref "J14") (pin "50") (pinfunction "A50_50") (pintype "passive"))
      (node (ref "J15") (pin "50") (pinfunction "A50_50") (pintype "passive"))
      (node (ref "J16") (pin "50") (pinfunction "A50_50") (pintype "passive"))
      (node (ref "J2") (pin "50") (pinfunction "A50_50") (pintype "passive"))
      (node (ref "J3") (pin "50") (pinfunction "A50_50") (pintype "passive"))
      (node (ref "J4") (pin "50") (pinfunction "A50_50") (pintype "passive"))
      (node (ref "J5") (pin "50") (pinfunction "A50_50") (pintype "passive"))
      (node (ref "J6") (pin "50") (pinfunction "A50_50") (pintype "passive"))
      (node (ref "J7") (pin "50") (pinfunction "A50_50") (pintype "passive"))
      (node (ref "J8") (pin "50") (pinfunction "A50_50") (pintype "passive"))
      (node (ref "J9") (pin "50") (pinfunction "A50_50") (pintype "passive"))
      (node (ref "R2") (pin "2") (pinfunction "2_2") (pintype "passive"))
      (node (ref "U10") (pin "13") (pinfunction "DO4-_13") (pintype "passive"))
    )
    (net (code "73") (name "/bus2") (class "Default")
      (node (ref "P9") (pin "26") (pinfunction "26_26") (pintype "passive"))
      (node (ref "U10") (pin "1") (pinfunction "DI1_1") (pintype "passive"))
      (node (ref "U11") (pin "1B31") (pinfunction "R19/R26p_1B31") (pintype "passive"))
    )
    (net (code "74") (name "/bus2_n") (class "Default")
      (node (ref "J1") (pin "56") (pinfunction "A56_56") (pintype "passive"))
      (node (ref "J10") (pin "56") (pinfunction "A56_56") (pintype "passive"))
      (node (ref "J11") (pin "56") (pinfunction "A56_56") (pintype "passive"))
      (node (ref "J12") (pin "56") (pinfunction "A56_56") (pintype "passive"))
      (node (ref "J13") (pin "56") (pinfunction "A56_56") (pintype "passive"))
      (node (ref "J14") (pin "56") (pinfunction "A56_56") (pintype "passive"))
      (node (ref "J15") (pin "56") (pinfunction "A56_56") (pintype "passive"))
      (node (ref "J16") (pin "56") (pinfunction "A56_56") (pintype "passive"))
      (node (ref "J2") (pin "56") (pinfunction "A56_56") (pintype "passive"))
      (node (ref "J3") (pin "56") (pinfunction "A56_56") (pintype "passive"))
      (node (ref "J4") (pin "56") (pinfunction "A56_56") (pintype "passive"))
      (node (ref "J5") (pin "56") (pinfunction "A56_56") (pintype "passive"))
      (node (ref "J6") (pin "56") (pinfunction "A56_56") (pintype "passive"))
      (node (ref "J7") (pin "56") (pinfunction "A56_56") (pintype "passive"))
      (node (ref "J8") (pin "56") (pinfunction "A56_56") (pintype "passive"))
      (node (ref "J9") (pin "56") (pinfunction "A56_56") (pintype "passive"))
      (node (ref "R3") (pin "1") (pinfunction "1_1") (pintype "passive"))
      (node (ref "U10") (pin "2") (pinfunction "DO1+_2") (pintype "passive"))
    )
    (net (code "75") (name "/bus2_p") (class "Default")
      (node (ref "J1") (pin "55") (pinfunction "A55_55") (pintype "passive"))
      (node (ref "J10") (pin "55") (pinfunction "A55_55") (pintype "passive"))
      (node (ref "J11") (pin "55") (pinfunction "A55_55") (pintype "passive"))
      (node (ref "J12") (pin "55") (pinfunction "A55_55") (pintype "passive"))
      (node (ref "J13") (pin "55") (pinfunction "A55_55") (pintype "passive"))
      (node (ref "J14") (pin "55") (pinfunction "A55_55") (pintype "passive"))
      (node (ref "J15") (pin "55") (pinfunction "A55_55") (pintype "passive"))
      (node (ref "J16") (pin "55") (pinfunction "A55_55") (pintype "passive"))
      (node (ref "J2") (pin "55") (pinfunction "A55_55") (pintype "passive"))
      (node (ref "J3") (pin "55") (pinfunction "A55_55") (pintype "passive"))
      (node (ref "J4") (pin "55") (pinfunction "A55_55") (pintype "passive"))
      (node (ref "J5") (pin "55") (pinfunction "A55_55") (pintype "passive"))
      (node (ref "J6") (pin "55") (pinfunction "A55_55") (pintype "passive"))
      (node (ref "J7") (pin "55") (pinfunction "A55_55") (pintype "passive"))
      (node (ref "J8") (pin "55") (pinfunction "A55_55") (pintype "passive"))
      (node (ref "J9") (pin "55") (pinfunction "A55_55") (pintype "passive"))
      (node (ref "R3") (pin "2") (pinfunction "2_2") (pintype "passive"))
      (node (ref "U10") (pin "3") (pinfunction "DO1-_3") (pintype "passive"))
    )
    (net (code "76") (name "/bus3") (class "Default")
      (node (ref "P9") (pin "25") (pinfunction "25_25") (pintype "passive"))
      (node (ref "U10") (pin "7") (pinfunction "DI2_7") (pintype "passive"))
      (node (ref "U11") (pin "1B30") (pinfunction "AB8/B17n_1B30") (pintype "passive"))
    )
    (net (code "77") (name "/bus3_n") (class "Default")
      (node (ref "J1") (pin "53") (pinfunction "A53_53") (pintype "passive"))
      (node (ref "J10") (pin "53") (pinfunction "A53_53") (pintype "passive"))
      (node (ref "J11") (pin "53") (pinfunction "A53_53") (pintype "passive"))
      (node (ref "J12") (pin "53") (pinfunction "A53_53") (pintype "passive"))
      (node (ref "J13") (pin "53") (pinfunction "A53_53") (pintype "passive"))
      (node (ref "J14") (pin "53") (pinfunction "A53_53") (pintype "passive"))
      (node (ref "J15") (pin "53") (pinfunction "A53_53") (pintype "passive"))
      (node (ref "J16") (pin "53") (pinfunction "A53_53") (pintype "passive"))
      (node (ref "J2") (pin "53") (pinfunction "A53_53") (pintype "passive"))
      (node (ref "J3") (pin "53") (pinfunction "A53_53") (pintype "passive"))
      (node (ref "J4") (pin "53") (pinfunction "A53_53") (pintype "passive"))
      (node (ref "J5") (pin "53") (pinfunction "A53_53") (pintype "passive"))
      (node (ref "J6") (pin "53") (pinfunction "A53_53") (pintype "passive"))
      (node (ref "J7") (pin "53") (pinfunction "A53_53") (pintype "passive"))
      (node (ref "J8") (pin "53") (pinfunction "A53_53") (pintype "passive"))
      (node (ref "J9") (pin "53") (pinfunction "A53_53") (pintype "passive"))
      (node (ref "R4") (pin "1") (pinfunction "1_1") (pintype "passive"))
      (node (ref "U10") (pin "6") (pinfunction "DO2+_6") (pintype "passive"))
    )
    (net (code "78") (name "/bus3_p") (class "Default")
      (node (ref "J1") (pin "54") (pinfunction "A54_54") (pintype "passive"))
      (node (ref "J10") (pin "54") (pinfunction "A54_54") (pintype "passive"))
      (node (ref "J11") (pin "54") (pinfunction "A54_54") (pintype "passive"))
      (node (ref "J12") (pin "54") (pinfunction "A54_54") (pintype "passive"))
      (node (ref "J13") (pin "54") (pinfunction "A54_54") (pintype "passive"))
      (node (ref "J14") (pin "54") (pinfunction "A54_54") (pintype "passive"))
      (node (ref "J15") (pin "54") (pinfunction "A54_54") (pintype "passive"))
      (node (ref "J16") (pin "54") (pinfunction "A54_54") (pintype "passive"))
      (node (ref "J2") (pin "54") (pinfunction "A54_54") (pintype "passive"))
      (node (ref "J3") (pin "54") (pinfunction "A54_54") (pintype "passive"))
      (node (ref "J4") (pin "54") (pinfunction "A54_54") (pintype "passive"))
      (node (ref "J5") (pin "54") (pinfunction "A54_54") (pintype "passive"))
      (node (ref "J6") (pin "54") (pinfunction "A54_54") (pintype "passive"))
      (node (ref "J7") (pin "54") (pinfunction "A54_54") (pintype "passive"))
      (node (ref "J8") (pin "54") (pinfunction "A54_54") (pintype "passive"))
      (node (ref "J9") (pin "54") (pinfunction "A54_54") (pintype "passive"))
      (node (ref "R4") (pin "2") (pinfunction "2_2") (pintype "passive"))
      (node (ref "U10") (pin "5") (pinfunction "DO2-_5") (pintype "passive"))
    )
    (net (code "79") (name "/bus4") (class "Default")
      (node (ref "P9") (pin "20") (pinfunction "20_20") (pintype "passive"))
      (node (ref "U11") (pin "1B25") (pinfunction "P3/L23n_1B25") (pintype "passive"))
      (node (ref "U9") (pin "9") (pinfunction "DI3_9") (pintype "passive"))
    )
    (net (code "80") (name "/bus4_n") (class "Default")
      (node (ref "J1") (pin "43") (pinfunction "A43_43") (pintype "passive"))
      (node (ref "J10") (pin "43") (pinfunction "A43_43") (pintype "passive"))
      (node (ref "J11") (pin "43") (pinfunction "A43_43") (pintype "passive"))
      (node (ref "J12") (pin "43") (pinfunction "A43_43") (pintype "passive"))
      (node (ref "J13") (pin "43") (pinfunction "A43_43") (pintype "passive"))
      (node (ref "J14") (pin "43") (pinfunction "A43_43") (pintype "passive"))
      (node (ref "J15") (pin "43") (pinfunction "A43_43") (pintype "passive"))
      (node (ref "J16") (pin "43") (pinfunction "A43_43") (pintype "passive"))
      (node (ref "J2") (pin "43") (pinfunction "A43_43") (pintype "passive"))
      (node (ref "J3") (pin "43") (pinfunction "A43_43") (pintype "passive"))
      (node (ref "J4") (pin "43") (pinfunction "A43_43") (pintype "passive"))
      (node (ref "J5") (pin "43") (pinfunction "A43_43") (pintype "passive"))
      (node (ref "J6") (pin "43") (pinfunction "A43_43") (pintype "passive"))
      (node (ref "J7") (pin "43") (pinfunction "A43_43") (pintype "passive"))
      (node (ref "J8") (pin "43") (pinfunction "A43_43") (pintype "passive"))
      (node (ref "J9") (pin "43") (pinfunction "A43_43") (pintype "passive"))
      (node (ref "R5") (pin "1") (pinfunction "1_1") (pintype "passive"))
      (node (ref "U9") (pin "10") (pinfunction "DO3+_10") (pintype "passive"))
    )
    (net (code "81") (name "/bus4_p") (class "Default")
      (node (ref "J1") (pin "42") (pinfunction "A42_42") (pintype "passive"))
      (node (ref "J10") (pin "42") (pinfunction "A42_42") (pintype "passive"))
      (node (ref "J11") (pin "42") (pinfunction "A42_42") (pintype "passive"))
      (node (ref "J12") (pin "42") (pinfunction "A42_42") (pintype "passive"))
      (node (ref "J13") (pin "42") (pinfunction "A42_42") (pintype "passive"))
      (node (ref "J14") (pin "42") (pinfunction "A42_42") (pintype "passive"))
      (node (ref "J15") (pin "42") (pinfunction "A42_42") (pintype "passive"))
      (node (ref "J16") (pin "42") (pinfunction "A42_42") (pintype "passive"))
      (node (ref "J2") (pin "42") (pinfunction "A42_42") (pintype "passive"))
      (node (ref "J3") (pin "42") (pinfunction "A42_42") (pintype "passive"))
      (node (ref "J4") (pin "42") (pinfunction "A42_42") (pintype "passive"))
      (node (ref "J5") (pin "42") (pinfunction "A42_42") (pintype "passive"))
      (node (ref "J6") (pin "42") (pinfunction "A42_42") (pintype "passive"))
      (node (ref "J7") (pin "42") (pinfunction "A42_42") (pintype "passive"))
      (node (ref "J8") (pin "42") (pinfunction "A42_42") (pintype "passive"))
      (node (ref "J9") (pin "42") (pinfunction "A42_42") (pintype "passive"))
      (node (ref "R5") (pin "2") (pinfunction "2_2") (pintype "passive"))
      (node (ref "U9") (pin "11") (pinfunction "DO3-_11") (pintype "passive"))
    )
    (net (code "82") (name "/bus5") (class "Default")
      (node (ref "P9") (pin "19") (pinfunction "19_19") (pintype "passive"))
      (node (ref "U11") (pin "1B24") (pinfunction "AA7/B10p_1B24") (pintype "passive"))
      (node (ref "U9") (pin "15") (pinfunction "DI4_15") (pintype "passive"))
    )
    (net (code "83") (name "/bus5_n") (class "Default")
      (node (ref "J1") (pin "40") (pinfunction "A40_40") (pintype "passive"))
      (node (ref "J10") (pin "40") (pinfunction "A40_40") (pintype "passive"))
      (node (ref "J11") (pin "40") (pinfunction "A40_40") (pintype "passive"))
      (node (ref "J12") (pin "40") (pinfunction "A40_40") (pintype "passive"))
      (node (ref "J13") (pin "40") (pinfunction "A40_40") (pintype "passive"))
      (node (ref "J14") (pin "40") (pinfunction "A40_40") (pintype "passive"))
      (node (ref "J15") (pin "40") (pinfunction "A40_40") (pintype "passive"))
      (node (ref "J16") (pin "40") (pinfunction "A40_40") (pintype "passive"))
      (node (ref "J2") (pin "40") (pinfunction "A40_40") (pintype "passive"))
      (node (ref "J3") (pin "40") (pinfunction "A40_40") (pintype "passive"))
      (node (ref "J4") (pin "40") (pinfunction "A40_40") (pintype "passive"))
      (node (ref "J5") (pin "40") (pinfunction "A40_40") (pintype "passive"))
      (node (ref "J6") (pin "40") (pinfunction "A40_40") (pintype "passive"))
      (node (ref "J7") (pin "40") (pinfunction "A40_40") (pintype "passive"))
      (node (ref "J8") (pin "40") (pinfunction "A40_40") (pintype "passive"))
      (node (ref "J9") (pin "40") (pinfunction "A40_40") (pintype "passive"))
      (node (ref "R6") (pin "1") (pinfunction "1_1") (pintype "passive"))
      (node (ref "U9") (pin "14") (pinfunction "DO4+_14") (pintype "passive"))
    )
    (net (code "84") (name "/bus5_p") (class "Default")
      (node (ref "J1") (pin "41") (pinfunction "A41_41") (pintype "passive"))
      (node (ref "J10") (pin "41") (pinfunction "A41_41") (pintype "passive"))
      (node (ref "J11") (pin "41") (pinfunction "A41_41") (pintype "passive"))
      (node (ref "J12") (pin "41") (pinfunction "A41_41") (pintype "passive"))
      (node (ref "J13") (pin "41") (pinfunction "A41_41") (pintype "passive"))
      (node (ref "J14") (pin "41") (pinfunction "A41_41") (pintype "passive"))
      (node (ref "J15") (pin "41") (pinfunction "A41_41") (pintype "passive"))
      (node (ref "J16") (pin "41") (pinfunction "A41_41") (pintype "passive"))
      (node (ref "J2") (pin "41") (pinfunction "A41_41") (pintype "passive"))
      (node (ref "J3") (pin "41") (pinfunction "A41_41") (pintype "passive"))
      (node (ref "J4") (pin "41") (pinfunction "A41_41") (pintype "passive"))
      (node (ref "J5") (pin "41") (pinfunction "A41_41") (pintype "passive"))
      (node (ref "J6") (pin "41") (pinfunction "A41_41") (pintype "passive"))
      (node (ref "J7") (pin "41") (pinfunction "A41_41") (pintype "passive"))
      (node (ref "J8") (pin "41") (pinfunction "A41_41") (pintype "passive"))
      (node (ref "J9") (pin "41") (pinfunction "A41_41") (pintype "passive"))
      (node (ref "R6") (pin "2") (pinfunction "2_2") (pintype "passive"))
      (node (ref "U9") (pin "13") (pinfunction "DO4-_13") (pintype "passive"))
    )
    (net (code "85") (name "/bus6") (class "Default")
      (node (ref "P9") (pin "22") (pinfunction "22_22") (pintype "passive"))
      (node (ref "U11") (pin "1B27") (pinfunction "U2/L24p_1B27") (pintype "passive"))
      (node (ref "U9") (pin "1") (pinfunction "DI1_1") (pintype "passive"))
    )
    (net (code "86") (name "/bus6_n") (class "Default")
      (node (ref "J1") (pin "47") (pinfunction "A47_47") (pintype "passive"))
      (node (ref "J10") (pin "47") (pinfunction "A47_47") (pintype "passive"))
      (node (ref "J11") (pin "47") (pinfunction "A47_47") (pintype "passive"))
      (node (ref "J12") (pin "47") (pinfunction "A47_47") (pintype "passive"))
      (node (ref "J13") (pin "47") (pinfunction "A47_47") (pintype "passive"))
      (node (ref "J14") (pin "47") (pinfunction "A47_47") (pintype "passive"))
      (node (ref "J15") (pin "47") (pinfunction "A47_47") (pintype "passive"))
      (node (ref "J16") (pin "47") (pinfunction "A47_47") (pintype "passive"))
      (node (ref "J2") (pin "47") (pinfunction "A47_47") (pintype "passive"))
      (node (ref "J3") (pin "47") (pinfunction "A47_47") (pintype "passive"))
      (node (ref "J4") (pin "47") (pinfunction "A47_47") (pintype "passive"))
      (node (ref "J5") (pin "47") (pinfunction "A47_47") (pintype "passive"))
      (node (ref "J6") (pin "47") (pinfunction "A47_47") (pintype "passive"))
      (node (ref "J7") (pin "47") (pinfunction "A47_47") (pintype "passive"))
      (node (ref "J8") (pin "47") (pinfunction "A47_47") (pintype "passive"))
      (node (ref "J9") (pin "47") (pinfunction "A47_47") (pintype "passive"))
      (node (ref "R7") (pin "1") (pinfunction "1_1") (pintype "passive"))
      (node (ref "U9") (pin "2") (pinfunction "DO1+_2") (pintype "passive"))
    )
    (net (code "87") (name "/bus6_p") (class "Default")
      (node (ref "J1") (pin "46") (pinfunction "A46_46") (pintype "passive"))
      (node (ref "J10") (pin "46") (pinfunction "A46_46") (pintype "passive"))
      (node (ref "J11") (pin "46") (pinfunction "A46_46") (pintype "passive"))
      (node (ref "J12") (pin "46") (pinfunction "A46_46") (pintype "passive"))
      (node (ref "J13") (pin "46") (pinfunction "A46_46") (pintype "passive"))
      (node (ref "J14") (pin "46") (pinfunction "A46_46") (pintype "passive"))
      (node (ref "J15") (pin "46") (pinfunction "A46_46") (pintype "passive"))
      (node (ref "J16") (pin "46") (pinfunction "A46_46") (pintype "passive"))
      (node (ref "J2") (pin "46") (pinfunction "A46_46") (pintype "passive"))
      (node (ref "J3") (pin "46") (pinfunction "A46_46") (pintype "passive"))
      (node (ref "J4") (pin "46") (pinfunction "A46_46") (pintype "passive"))
      (node (ref "J5") (pin "46") (pinfunction "A46_46") (pintype "passive"))
      (node (ref "J6") (pin "46") (pinfunction "A46_46") (pintype "passive"))
      (node (ref "J7") (pin "46") (pinfunction "A46_46") (pintype "passive"))
      (node (ref "J8") (pin "46") (pinfunction "A46_46") (pintype "passive"))
      (node (ref "J9") (pin "46") (pinfunction "A46_46") (pintype "passive"))
      (node (ref "R7") (pin "2") (pinfunction "2_2") (pintype "passive"))
      (node (ref "U9") (pin "3") (pinfunction "DO1-_3") (pintype "passive"))
    )
    (net (code "88") (name "/bus7") (class "Default")
      (node (ref "P9") (pin "21") (pinfunction "21_21") (pintype "passive"))
      (node (ref "U11") (pin "1B26") (pinfunction "AB7/B10n_1B26") (pintype "passive"))
      (node (ref "U9") (pin "7") (pinfunction "DI2_7") (pintype "passive"))
    )
    (net (code "89") (name "/bus7_n") (class "Default")
      (node (ref "J1") (pin "44") (pinfunction "A44_44") (pintype "passive"))
      (node (ref "J10") (pin "44") (pinfunction "A44_44") (pintype "passive"))
      (node (ref "J11") (pin "44") (pinfunction "A44_44") (pintype "passive"))
      (node (ref "J12") (pin "44") (pinfunction "A44_44") (pintype "passive"))
      (node (ref "J13") (pin "44") (pinfunction "A44_44") (pintype "passive"))
      (node (ref "J14") (pin "44") (pinfunction "A44_44") (pintype "passive"))
      (node (ref "J15") (pin "44") (pinfunction "A44_44") (pintype "passive"))
      (node (ref "J16") (pin "44") (pinfunction "A44_44") (pintype "passive"))
      (node (ref "J2") (pin "44") (pinfunction "A44_44") (pintype "passive"))
      (node (ref "J3") (pin "44") (pinfunction "A44_44") (pintype "passive"))
      (node (ref "J4") (pin "44") (pinfunction "A44_44") (pintype "passive"))
      (node (ref "J5") (pin "44") (pinfunction "A44_44") (pintype "passive"))
      (node (ref "J6") (pin "44") (pinfunction "A44_44") (pintype "passive"))
      (node (ref "J7") (pin "44") (pinfunction "A44_44") (pintype "passive"))
      (node (ref "J8") (pin "44") (pinfunction "A44_44") (pintype "passive"))
      (node (ref "J9") (pin "44") (pinfunction "A44_44") (pintype "passive"))
      (node (ref "R8") (pin "1") (pinfunction "1_1") (pintype "passive"))
      (node (ref "U9") (pin "6") (pinfunction "DO2+_6") (pintype "passive"))
    )
    (net (code "90") (name "/bus7_p") (class "Default")
      (node (ref "J1") (pin "45") (pinfunction "A45_45") (pintype "passive"))
      (node (ref "J10") (pin "45") (pinfunction "A45_45") (pintype "passive"))
      (node (ref "J11") (pin "45") (pinfunction "A45_45") (pintype "passive"))
      (node (ref "J12") (pin "45") (pinfunction "A45_45") (pintype "passive"))
      (node (ref "J13") (pin "45") (pinfunction "A45_45") (pintype "passive"))
      (node (ref "J14") (pin "45") (pinfunction "A45_45") (pintype "passive"))
      (node (ref "J15") (pin "45") (pinfunction "A45_45") (pintype "passive"))
      (node (ref "J16") (pin "45") (pinfunction "A45_45") (pintype "passive"))
      (node (ref "J2") (pin "45") (pinfunction "A45_45") (pintype "passive"))
      (node (ref "J3") (pin "45") (pinfunction "A45_45") (pintype "passive"))
      (node (ref "J4") (pin "45") (pinfunction "A45_45") (pintype "passive"))
      (node (ref "J5") (pin "45") (pinfunction "A45_45") (pintype "passive"))
      (node (ref "J6") (pin "45") (pinfunction "A45_45") (pintype "passive"))
      (node (ref "J7") (pin "45") (pinfunction "A45_45") (pintype "passive"))
      (node (ref "J8") (pin "45") (pinfunction "A45_45") (pintype "passive"))
      (node (ref "J9") (pin "45") (pinfunction "A45_45") (pintype "passive"))
      (node (ref "R8") (pin "2") (pinfunction "2_2") (pintype "passive"))
      (node (ref "U9") (pin "5") (pinfunction "DO2-_5") (pintype "passive"))
    )
    (net (code "91") (name "/bus8") (class "Default")
      (node (ref "P9") (pin "14") (pinfunction "14_14") (pintype "passive"))
      (node (ref "U11") (pin "1B21") (pinfunction "R1/L21n_1B21") (pintype "passive"))
      (node (ref "U8") (pin "9") (pinfunction "DI3_9") (pintype "passive"))
    )
    (net (code "92") (name "/bus8_n") (class "Default")
      (node (ref "J1") (pin "34") (pinfunction "A34_34") (pintype "passive"))
      (node (ref "J10") (pin "34") (pinfunction "A34_34") (pintype "passive"))
      (node (ref "J11") (pin "34") (pinfunction "A34_34") (pintype "passive"))
      (node (ref "J12") (pin "34") (pinfunction "A34_34") (pintype "passive"))
      (node (ref "J13") (pin "34") (pinfunction "A34_34") (pintype "passive"))
      (node (ref "J14") (pin "34") (pinfunction "A34_34") (pintype "passive"))
      (node (ref "J15") (pin "34") (pinfunction "A34_34") (pintype "passive"))
      (node (ref "J16") (pin "34") (pinfunction "A34_34") (pintype "passive"))
      (node (ref "J2") (pin "34") (pinfunction "A34_34") (pintype "passive"))
      (node (ref "J3") (pin "34") (pinfunction "A34_34") (pintype "passive"))
      (node (ref "J4") (pin "34") (pinfunction "A34_34") (pintype "passive"))
      (node (ref "J5") (pin "34") (pinfunction "A34_34") (pintype "passive"))
      (node (ref "J6") (pin "34") (pinfunction "A34_34") (pintype "passive"))
      (node (ref "J7") (pin "34") (pinfunction "A34_34") (pintype "passive"))
      (node (ref "J8") (pin "34") (pinfunction "A34_34") (pintype "passive"))
      (node (ref "J9") (pin "34") (pinfunction "A34_34") (pintype "passive"))
      (node (ref "R9") (pin "1") (pinfunction "1_1") (pintype "passive"))
      (node (ref "U8") (pin "10") (pinfunction "DO3+_10") (pintype "passive"))
    )
    (net (code "93") (name "/bus8_p") (class "Default")
      (node (ref "J1") (pin "33") (pinfunction "A33_33") (pintype "passive"))
      (node (ref "J10") (pin "33") (pinfunction "A33_33") (pintype "passive"))
      (node (ref "J11") (pin "33") (pinfunction "A33_33") (pintype "passive"))
      (node (ref "J12") (pin "33") (pinfunction "A33_33") (pintype "passive"))
      (node (ref "J13") (pin "33") (pinfunction "A33_33") (pintype "passive"))
      (node (ref "J14") (pin "33") (pinfunction "A33_33") (pintype "passive"))
      (node (ref "J15") (pin "33") (pinfunction "A33_33") (pintype "passive"))
      (node (ref "J16") (pin "33") (pinfunction "A33_33") (pintype "passive"))
      (node (ref "J2") (pin "33") (pinfunction "A33_33") (pintype "passive"))
      (node (ref "J3") (pin "33") (pinfunction "A33_33") (pintype "passive"))
      (node (ref "J4") (pin "33") (pinfunction "A33_33") (pintype "passive"))
      (node (ref "J5") (pin "33") (pinfunction "A33_33") (pintype "passive"))
      (node (ref "J6") (pin "33") (pinfunction "A33_33") (pintype "passive"))
      (node (ref "J7") (pin "33") (pinfunction "A33_33") (pintype "passive"))
      (node (ref "J8") (pin "33") (pinfunction "A33_33") (pintype "passive"))
      (node (ref "J9") (pin "33") (pinfunction "A33_33") (pintype "passive"))
      (node (ref "R9") (pin "2") (pinfunction "2_2") (pintype "passive"))
      (node (ref "U8") (pin "11") (pinfunction "DO3-_11") (pintype "passive"))
    )
    (net (code "94") (name "/bus9") (class "Default")
      (node (ref "P9") (pin "13") (pinfunction "13_13") (pintype "passive"))
      (node (ref "U11") (pin "1B20") (pinfunction "W7/B7p_1B20") (pintype "passive"))
      (node (ref "U8") (pin "15") (pinfunction "DI4_15") (pintype "passive"))
    )
    (net (code "95") (name "/bus9_n") (class "Default")
      (node (ref "J1") (pin "31") (pinfunction "A31_31") (pintype "passive"))
      (node (ref "J10") (pin "31") (pinfunction "A31_31") (pintype "passive"))
      (node (ref "J11") (pin "31") (pinfunction "A31_31") (pintype "passive"))
      (node (ref "J12") (pin "31") (pinfunction "A31_31") (pintype "passive"))
      (node (ref "J13") (pin "31") (pinfunction "A31_31") (pintype "passive"))
      (node (ref "J14") (pin "31") (pinfunction "A31_31") (pintype "passive"))
      (node (ref "J15") (pin "31") (pinfunction "A31_31") (pintype "passive"))
      (node (ref "J16") (pin "31") (pinfunction "A31_31") (pintype "passive"))
      (node (ref "J2") (pin "31") (pinfunction "A31_31") (pintype "passive"))
      (node (ref "J3") (pin "31") (pinfunction "A31_31") (pintype "passive"))
      (node (ref "J4") (pin "31") (pinfunction "A31_31") (pintype "passive"))
      (node (ref "J5") (pin "31") (pinfunction "A31_31") (pintype "passive"))
      (node (ref "J6") (pin "31") (pinfunction "A31_31") (pintype "passive"))
      (node (ref "J7") (pin "31") (pinfunction "A31_31") (pintype "passive"))
      (node (ref "J8") (pin "31") (pinfunction "A31_31") (pintype "passive"))
      (node (ref "J9") (pin "31") (pinfunction "A31_31") (pintype "passive"))
      (node (ref "R10") (pin "1") (pinfunction "1_1") (pintype "passive"))
      (node (ref "U8") (pin "14") (pinfunction "DO4+_14") (pintype "passive"))
    )
    (net (code "96") (name "/bus9_p") (class "Default")
      (node (ref "J1") (pin "32") (pinfunction "A32_32") (pintype "passive"))
      (node (ref "J10") (pin "32") (pinfunction "A32_32") (pintype "passive"))
      (node (ref "J11") (pin "32") (pinfunction "A32_32") (pintype "passive"))
      (node (ref "J12") (pin "32") (pinfunction "A32_32") (pintype "passive"))
      (node (ref "J13") (pin "32") (pinfunction "A32_32") (pintype "passive"))
      (node (ref "J14") (pin "32") (pinfunction "A32_32") (pintype "passive"))
      (node (ref "J15") (pin "32") (pinfunction "A32_32") (pintype "passive"))
      (node (ref "J16") (pin "32") (pinfunction "A32_32") (pintype "passive"))
      (node (ref "J2") (pin "32") (pinfunction "A32_32") (pintype "passive"))
      (node (ref "J3") (pin "32") (pinfunction "A32_32") (pintype "passive"))
      (node (ref "J4") (pin "32") (pinfunction "A32_32") (pintype "passive"))
      (node (ref "J5") (pin "32") (pinfunction "A32_32") (pintype "passive"))
      (node (ref "J6") (pin "32") (pinfunction "A32_32") (pintype "passive"))
      (node (ref "J7") (pin "32") (pinfunction "A32_32") (pintype "passive"))
      (node (ref "J8") (pin "32") (pinfunction "A32_32") (pintype "passive"))
      (node (ref "J9") (pin "32") (pinfunction "A32_32") (pintype "passive"))
      (node (ref "R10") (pin "2") (pinfunction "2_2") (pintype "passive"))
      (node (ref "U8") (pin "13") (pinfunction "DO4-_13") (pintype "passive"))
    )
    (net (code "97") (name "/bus10") (class "Default")
      (node (ref "P9") (pin "18") (pinfunction "18_18") (pintype "passive"))
      (node (ref "U11") (pin "1B23") (pinfunction "P4/L23p_1B23") (pintype "passive"))
      (node (ref "U8") (pin "1") (pinfunction "DI1_1") (pintype "passive"))
    )
    (net (code "98") (name "/bus10_n") (class "Default")
      (node (ref "J1") (pin "38") (pinfunction "A38_38") (pintype "passive"))
      (node (ref "J10") (pin "38") (pinfunction "A38_38") (pintype "passive"))
      (node (ref "J11") (pin "38") (pinfunction "A38_38") (pintype "passive"))
      (node (ref "J12") (pin "38") (pinfunction "A38_38") (pintype "passive"))
      (node (ref "J13") (pin "38") (pinfunction "A38_38") (pintype "passive"))
      (node (ref "J14") (pin "38") (pinfunction "A38_38") (pintype "passive"))
      (node (ref "J15") (pin "38") (pinfunction "A38_38") (pintype "passive"))
      (node (ref "J16") (pin "38") (pinfunction "A38_38") (pintype "passive"))
      (node (ref "J2") (pin "38") (pinfunction "A38_38") (pintype "passive"))
      (node (ref "J3") (pin "38") (pinfunction "A38_38") (pintype "passive"))
      (node (ref "J4") (pin "38") (pinfunction "A38_38") (pintype "passive"))
      (node (ref "J5") (pin "38") (pinfunction "A38_38") (pintype "passive"))
      (node (ref "J6") (pin "38") (pinfunction "A38_38") (pintype "passive"))
      (node (ref "J7") (pin "38") (pinfunction "A38_38") (pintype "passive"))
      (node (ref "J8") (pin "38") (pinfunction "A38_38") (pintype "passive"))
      (node (ref "J9") (pin "38") (pinfunction "A38_38") (pintype "passive"))
      (node (ref "R11") (pin "1") (pinfunction "1_1") (pintype "passive"))
      (node (ref "U8") (pin "2") (pinfunction "DO1+_2") (pintype "passive"))
    )
    (net (code "99") (name "/bus10_p") (class "Default")
      (node (ref "J1") (pin "37") (pinfunction "A37_37") (pintype "passive"))
      (node (ref "J10") (pin "37") (pinfunction "A37_37") (pintype "passive"))
      (node (ref "J11") (pin "37") (pinfunction "A37_37") (pintype "passive"))
      (node (ref "J12") (pin "37") (pinfunction "A37_37") (pintype "passive"))
      (node (ref "J13") (pin "37") (pinfunction "A37_37") (pintype "passive"))
      (node (ref "J14") (pin "37") (pinfunction "A37_37") (pintype "passive"))
      (node (ref "J15") (pin "37") (pinfunction "A37_37") (pintype "passive"))
      (node (ref "J16") (pin "37") (pinfunction "A37_37") (pintype "passive"))
      (node (ref "J2") (pin "37") (pinfunction "A37_37") (pintype "passive"))
      (node (ref "J3") (pin "37") (pinfunction "A37_37") (pintype "passive"))
      (node (ref "J4") (pin "37") (pinfunction "A37_37") (pintype "passive"))
      (node (ref "J5") (pin "37") (pinfunction "A37_37") (pintype "passive"))
      (node (ref "J6") (pin "37") (pinfunction "A37_37") (pintype "passive"))
      (node (ref "J7") (pin "37") (pinfunction "A37_37") (pintype "passive"))
      (node (ref "J8") (pin "37") (pinfunction "A37_37") (pintype "passive"))
      (node (ref "J9") (pin "37") (pinfunction "A37_37") (pintype "passive"))
      (node (ref "R11") (pin "2") (pinfunction "2_2") (pintype "passive"))
      (node (ref "U8") (pin "3") (pinfunction "DO1-_3") (pintype "passive"))
    )
    (net (code "100") (name "/bus11") (class "Default")
      (node (ref "P9") (pin "17") (pinfunction "17_17") (pintype "passive"))
      (node (ref "U11") (pin "1B22") (pinfunction "Y7/B7n_1B22") (pintype "passive"))
      (node (ref "U8") (pin "7") (pinfunction "DI2_7") (pintype "passive"))
    )
    (net (code "101") (name "/bus11_n") (class "Default")
      (node (ref "J1") (pin "35") (pinfunction "A35_35") (pintype "passive"))
      (node (ref "J10") (pin "35") (pinfunction "A35_35") (pintype "passive"))
      (node (ref "J11") (pin "35") (pinfunction "A35_35") (pintype "passive"))
      (node (ref "J12") (pin "35") (pinfunction "A35_35") (pintype "passive"))
      (node (ref "J13") (pin "35") (pinfunction "A35_35") (pintype "passive"))
      (node (ref "J14") (pin "35") (pinfunction "A35_35") (pintype "passive"))
      (node (ref "J15") (pin "35") (pinfunction "A35_35") (pintype "passive"))
      (node (ref "J16") (pin "35") (pinfunction "A35_35") (pintype "passive"))
      (node (ref "J2") (pin "35") (pinfunction "A35_35") (pintype "passive"))
      (node (ref "J3") (pin "35") (pinfunction "A35_35") (pintype "passive"))
      (node (ref "J4") (pin "35") (pinfunction "A35_35") (pintype "passive"))
      (node (ref "J5") (pin "35") (pinfunction "A35_35") (pintype "passive"))
      (node (ref "J6") (pin "35") (pinfunction "A35_35") (pintype "passive"))
      (node (ref "J7") (pin "35") (pinfunction "A35_35") (pintype "passive"))
      (node (ref "J8") (pin "35") (pinfunction "A35_35") (pintype "passive"))
      (node (ref "J9") (pin "35") (pinfunction "A35_35") (pintype "passive"))
      (node (ref "R12") (pin "1") (pinfunction "1_1") (pintype "passive"))
      (node (ref "U8") (pin "6") (pinfunction "DO2+_6") (pintype "passive"))
    )
    (net (code "102") (name "/bus11_p") (class "Default")
      (node (ref "J1") (pin "36") (pinfunction "A36_36") (pintype "passive"))
      (node (ref "J10") (pin "36") (pinfunction "A36_36") (pintype "passive"))
      (node (ref "J11") (pin "36") (pinfunction "A36_36") (pintype "passive"))
      (node (ref "J12") (pin "36") (pinfunction "A36_36") (pintype "passive"))
      (node (ref "J13") (pin "36") (pinfunction "A36_36") (pintype "passive"))
      (node (ref "J14") (pin "36") (pinfunction "A36_36") (pintype "passive"))
      (node (ref "J15") (pin "36") (pinfunction "A36_36") (pintype "passive"))
      (node (ref "J16") (pin "36") (pinfunction "A36_36") (pintype "passive"))
      (node (ref "J2") (pin "36") (pinfunction "A36_36") (pintype "passive"))
      (node (ref "J3") (pin "36") (pinfunction "A36_36") (pintype "passive"))
      (node (ref "J4") (pin "36") (pinfunction "A36_36") (pintype "passive"))
      (node (ref "J5") (pin "36") (pinfunction "A36_36") (pintype "passive"))
      (node (ref "J6") (pin "36") (pinfunction "A36_36") (pintype "passive"))
      (node (ref "J7") (pin "36") (pinfunction "A36_36") (pintype "passive"))
      (node (ref "J8") (pin "36") (pinfunction "A36_36") (pintype "passive"))
      (node (ref "J9") (pin "36") (pinfunction "A36_36") (pintype "passive"))
      (node (ref "R12") (pin "2") (pinfunction "2_2") (pintype "passive"))
      (node (ref "U8") (pin "5") (pinfunction "DO2-_5") (pintype "passive"))
    )
    (net (code "103") (name "/bus12") (class "Default")
      (node (ref "P9") (pin "10") (pinfunction "10_10") (pintype "passive"))
      (node (ref "U11") (pin "1B17") (pinfunction "P1/L20n_1B17") (pintype "passive"))
      (node (ref "U7") (pin "9") (pinfunction "DI3_9") (pintype "passive"))
    )
    (net (code "104") (name "/bus12_n") (class "Default")
      (node (ref "J1") (pin "25") (pinfunction "A25_25") (pintype "passive"))
      (node (ref "J10") (pin "25") (pinfunction "A25_25") (pintype "passive"))
      (node (ref "J11") (pin "25") (pinfunction "A25_25") (pintype "passive"))
      (node (ref "J12") (pin "25") (pinfunction "A25_25") (pintype "passive"))
      (node (ref "J13") (pin "25") (pinfunction "A25_25") (pintype "passive"))
      (node (ref "J14") (pin "25") (pinfunction "A25_25") (pintype "passive"))
      (node (ref "J15") (pin "25") (pinfunction "A25_25") (pintype "passive"))
      (node (ref "J16") (pin "25") (pinfunction "A25_25") (pintype "passive"))
      (node (ref "J2") (pin "25") (pinfunction "A25_25") (pintype "passive"))
      (node (ref "J3") (pin "25") (pinfunction "A25_25") (pintype "passive"))
      (node (ref "J4") (pin "25") (pinfunction "A25_25") (pintype "passive"))
      (node (ref "J5") (pin "25") (pinfunction "A25_25") (pintype "passive"))
      (node (ref "J6") (pin "25") (pinfunction "A25_25") (pintype "passive"))
      (node (ref "J7") (pin "25") (pinfunction "A25_25") (pintype "passive"))
      (node (ref "J8") (pin "25") (pinfunction "A25_25") (pintype "passive"))
      (node (ref "J9") (pin "25") (pinfunction "A25_25") (pintype "passive"))
      (node (ref "R13") (pin "1") (pinfunction "1_1") (pintype "passive"))
      (node (ref "U7") (pin "10") (pinfunction "DO3+_10") (pintype "passive"))
    )
    (net (code "105") (name "/bus12_p") (class "Default")
      (node (ref "J1") (pin "24") (pinfunction "A24_24") (pintype "passive"))
      (node (ref "J10") (pin "24") (pinfunction "A24_24") (pintype "passive"))
      (node (ref "J11") (pin "24") (pinfunction "A24_24") (pintype "passive"))
      (node (ref "J12") (pin "24") (pinfunction "A24_24") (pintype "passive"))
      (node (ref "J13") (pin "24") (pinfunction "A24_24") (pintype "passive"))
      (node (ref "J14") (pin "24") (pinfunction "A24_24") (pintype "passive"))
      (node (ref "J15") (pin "24") (pinfunction "A24_24") (pintype "passive"))
      (node (ref "J16") (pin "24") (pinfunction "A24_24") (pintype "passive"))
      (node (ref "J2") (pin "24") (pinfunction "A24_24") (pintype "passive"))
      (node (ref "J3") (pin "24") (pinfunction "A24_24") (pintype "passive"))
      (node (ref "J4") (pin "24") (pinfunction "A24_24") (pintype "passive"))
      (node (ref "J5") (pin "24") (pinfunction "A24_24") (pintype "passive"))
      (node (ref "J6") (pin "24") (pinfunction "A24_24") (pintype "passive"))
      (node (ref "J7") (pin "24") (pinfunction "A24_24") (pintype "passive"))
      (node (ref "J8") (pin "24") (pinfunction "A24_24") (pintype "passive"))
      (node (ref "J9") (pin "24") (pinfunction "A24_24") (pintype "passive"))
      (node (ref "R13") (pin "2") (pinfunction "2_2") (pintype "passive"))
      (node (ref "U7") (pin "11") (pinfunction "DO3-_11") (pintype "passive"))
    )
    (net (code "106") (name "/bus13") (class "Default")
      (node (ref "P9") (pin "9") (pinfunction "9_9") (pintype "passive"))
      (node (ref "U11") (pin "1B16") (pinfunction "AB6/B6p_1B16") (pintype "passive"))
      (node (ref "U7") (pin "15") (pinfunction "DI4_15") (pintype "passive"))
    )
    (net (code "107") (name "/bus13_n") (class "Default")
      (node (ref "J1") (pin "22") (pinfunction "A22_22") (pintype "passive"))
      (node (ref "J10") (pin "22") (pinfunction "A22_22") (pintype "passive"))
      (node (ref "J11") (pin "22") (pinfunction "A22_22") (pintype "passive"))
      (node (ref "J12") (pin "22") (pinfunction "A22_22") (pintype "passive"))
      (node (ref "J13") (pin "22") (pinfunction "A22_22") (pintype "passive"))
      (node (ref "J14") (pin "22") (pinfunction "A22_22") (pintype "passive"))
      (node (ref "J15") (pin "22") (pinfunction "A22_22") (pintype "passive"))
      (node (ref "J16") (pin "22") (pinfunction "A22_22") (pintype "passive"))
      (node (ref "J2") (pin "22") (pinfunction "A22_22") (pintype "passive"))
      (node (ref "J3") (pin "22") (pinfunction "A22_22") (pintype "passive"))
      (node (ref "J4") (pin "22") (pinfunction "A22_22") (pintype "passive"))
      (node (ref "J5") (pin "22") (pinfunction "A22_22") (pintype "passive"))
      (node (ref "J6") (pin "22") (pinfunction "A22_22") (pintype "passive"))
      (node (ref "J7") (pin "22") (pinfunction "A22_22") (pintype "passive"))
      (node (ref "J8") (pin "22") (pinfunction "A22_22") (pintype "passive"))
      (node (ref "J9") (pin "22") (pinfunction "A22_22") (pintype "passive"))
      (node (ref "R14") (pin "1") (pinfunction "1_1") (pintype "passive"))
      (node (ref "U7") (pin "14") (pinfunction "DO4+_14") (pintype "passive"))
    )
    (net (code "108") (name "/bus13_p") (class "Default")
      (node (ref "J1") (pin "23") (pinfunction "A23_23") (pintype "passive"))
      (node (ref "J10") (pin "23") (pinfunction "A23_23") (pintype "passive"))
      (node (ref "J11") (pin "23") (pinfunction "A23_23") (pintype "passive"))
      (node (ref "J12") (pin "23") (pinfunction "A23_23") (pintype "passive"))
      (node (ref "J13") (pin "23") (pinfunction "A23_23") (pintype "passive"))
      (node (ref "J14") (pin "23") (pinfunction "A23_23") (pintype "passive"))
      (node (ref "J15") (pin "23") (pinfunction "A23_23") (pintype "passive"))
      (node (ref "J16") (pin "23") (pinfunction "A23_23") (pintype "passive"))
      (node (ref "J2") (pin "23") (pinfunction "A23_23") (pintype "passive"))
      (node (ref "J3") (pin "23") (pinfunction "A23_23") (pintype "passive"))
      (node (ref "J4") (pin "23") (pinfunction "A23_23") (pintype "passive"))
      (node (ref "J5") (pin "23") (pinfunction "A23_23") (pintype "passive"))
      (node (ref "J6") (pin "23") (pinfunction "A23_23") (pintype "passive"))
      (node (ref "J7") (pin "23") (pinfunction "A23_23") (pintype "passive"))
      (node (ref "J8") (pin "23") (pinfunction "A23_23") (pintype "passive"))
      (node (ref "J9") (pin "23") (pinfunction "A23_23") (pintype "passive"))
      (node (ref "R14") (pin "2") (pinfunction "2_2") (pintype "passive"))
      (node (ref "U7") (pin "13") (pinfunction "DO4-_13") (pintype "passive"))
    )
    (net (code "109") (name "/bus14") (class "Default")
      (node (ref "P9") (pin "12") (pinfunction "12_12") (pintype "passive"))
      (node (ref "U11") (pin "1B19") (pinfunction "R2/L21p_1B19") (pintype "passive"))
      (node (ref "U7") (pin "1") (pinfunction "DI1_1") (pintype "passive"))
    )
    (net (code "110") (name "/bus14_n") (class "Default")
      (node (ref "J1") (pin "29") (pinfunction "A29_29") (pintype "passive"))
      (node (ref "J10") (pin "29") (pinfunction "A29_29") (pintype "passive"))
      (node (ref "J11") (pin "29") (pinfunction "A29_29") (pintype "passive"))
      (node (ref "J12") (pin "29") (pinfunction "A29_29") (pintype "passive"))
      (node (ref "J13") (pin "29") (pinfunction "A29_29") (pintype "passive"))
      (node (ref "J14") (pin "29") (pinfunction "A29_29") (pintype "passive"))
      (node (ref "J15") (pin "29") (pinfunction "A29_29") (pintype "passive"))
      (node (ref "J16") (pin "29") (pinfunction "A29_29") (pintype "passive"))
      (node (ref "J2") (pin "29") (pinfunction "A29_29") (pintype "passive"))
      (node (ref "J3") (pin "29") (pinfunction "A29_29") (pintype "passive"))
      (node (ref "J4") (pin "29") (pinfunction "A29_29") (pintype "passive"))
      (node (ref "J5") (pin "29") (pinfunction "A29_29") (pintype "passive"))
      (node (ref "J6") (pin "29") (pinfunction "A29_29") (pintype "passive"))
      (node (ref "J7") (pin "29") (pinfunction "A29_29") (pintype "passive"))
      (node (ref "J8") (pin "29") (pinfunction "A29_29") (pintype "passive"))
      (node (ref "J9") (pin "29") (pinfunction "A29_29") (pintype "passive"))
      (node (ref "R15") (pin "1") (pinfunction "1_1") (pintype "passive"))
      (node (ref "U7") (pin "2") (pinfunction "DO1+_2") (pintype "passive"))
    )
    (net (code "111") (name "/bus14_p") (class "Default")
      (node (ref "J1") (pin "28") (pinfunction "A28_28") (pintype "passive"))
      (node (ref "J10") (pin "28") (pinfunction "A28_28") (pintype "passive"))
      (node (ref "J11") (pin "28") (pinfunction "A28_28") (pintype "passive"))
      (node (ref "J12") (pin "28") (pinfunction "A28_28") (pintype "passive"))
      (node (ref "J13") (pin "28") (pinfunction "A28_28") (pintype "passive"))
      (node (ref "J14") (pin "28") (pinfunction "A28_28") (pintype "passive"))
      (node (ref "J15") (pin "28") (pinfunction "A28_28") (pintype "passive"))
      (node (ref "J16") (pin "28") (pinfunction "A28_28") (pintype "passive"))
      (node (ref "J2") (pin "28") (pinfunction "A28_28") (pintype "passive"))
      (node (ref "J3") (pin "28") (pinfunction "A28_28") (pintype "passive"))
      (node (ref "J4") (pin "28") (pinfunction "A28_28") (pintype "passive"))
      (node (ref "J5") (pin "28") (pinfunction "A28_28") (pintype "passive"))
      (node (ref "J6") (pin "28") (pinfunction "A28_28") (pintype "passive"))
      (node (ref "J7") (pin "28") (pinfunction "A28_28") (pintype "passive"))
      (node (ref "J8") (pin "28") (pinfunction "A28_28") (pintype "passive"))
      (node (ref "J9") (pin "28") (pinfunction "A28_28") (pintype "passive"))
      (node (ref "R15") (pin "2") (pinfunction "2_2") (pintype "passive"))
      (node (ref "U7") (pin "3") (pinfunction "DO1-_3") (pintype "passive"))
    )
    (net (code "112") (name "/bus15") (class "Default")
      (node (ref "P9") (pin "11") (pinfunction "11_11") (pintype "passive"))
      (node (ref "U11") (pin "1B18") (pinfunction "AB5/B6n_1B18") (pintype "passive"))
      (node (ref "U7") (pin "7") (pinfunction "DI2_7") (pintype "passive"))
    )
    (net (code "113") (name "/bus15_n") (class "Default")
      (node (ref "J1") (pin "26") (pinfunction "A26_26") (pintype "passive"))
      (node (ref "J10") (pin "26") (pinfunction "A26_26") (pintype "passive"))
      (node (ref "J11") (pin "26") (pinfunction "A26_26") (pintype "passive"))
      (node (ref "J12") (pin "26") (pinfunction "A26_26") (pintype "passive"))
      (node (ref "J13") (pin "26") (pinfunction "A26_26") (pintype "passive"))
      (node (ref "J14") (pin "26") (pinfunction "A26_26") (pintype "passive"))
      (node (ref "J15") (pin "26") (pinfunction "A26_26") (pintype "passive"))
      (node (ref "J16") (pin "26") (pinfunction "A26_26") (pintype "passive"))
      (node (ref "J2") (pin "26") (pinfunction "A26_26") (pintype "passive"))
      (node (ref "J3") (pin "26") (pinfunction "A26_26") (pintype "passive"))
      (node (ref "J4") (pin "26") (pinfunction "A26_26") (pintype "passive"))
      (node (ref "J5") (pin "26") (pinfunction "A26_26") (pintype "passive"))
      (node (ref "J6") (pin "26") (pinfunction "A26_26") (pintype "passive"))
      (node (ref "J7") (pin "26") (pinfunction "A26_26") (pintype "passive"))
      (node (ref "J8") (pin "26") (pinfunction "A26_26") (pintype "passive"))
      (node (ref "J9") (pin "26") (pinfunction "A26_26") (pintype "passive"))
      (node (ref "R16") (pin "1") (pinfunction "1_1") (pintype "passive"))
      (node (ref "U7") (pin "6") (pinfunction "DO2+_6") (pintype "passive"))
    )
    (net (code "114") (name "/bus15_p") (class "Default")
      (node (ref "J1") (pin "27") (pinfunction "A27_27") (pintype "passive"))
      (node (ref "J10") (pin "27") (pinfunction "A27_27") (pintype "passive"))
      (node (ref "J11") (pin "27") (pinfunction "A27_27") (pintype "passive"))
      (node (ref "J12") (pin "27") (pinfunction "A27_27") (pintype "passive"))
      (node (ref "J13") (pin "27") (pinfunction "A27_27") (pintype "passive"))
      (node (ref "J14") (pin "27") (pinfunction "A27_27") (pintype "passive"))
      (node (ref "J15") (pin "27") (pinfunction "A27_27") (pintype "passive"))
      (node (ref "J16") (pin "27") (pinfunction "A27_27") (pintype "passive"))
      (node (ref "J2") (pin "27") (pinfunction "A27_27") (pintype "passive"))
      (node (ref "J3") (pin "27") (pinfunction "A27_27") (pintype "passive"))
      (node (ref "J4") (pin "27") (pinfunction "A27_27") (pintype "passive"))
      (node (ref "J5") (pin "27") (pinfunction "A27_27") (pintype "passive"))
      (node (ref "J6") (pin "27") (pinfunction "A27_27") (pintype "passive"))
      (node (ref "J7") (pin "27") (pinfunction "A27_27") (pintype "passive"))
      (node (ref "J8") (pin "27") (pinfunction "A27_27") (pintype "passive"))
      (node (ref "J9") (pin "27") (pinfunction "A27_27") (pintype "passive"))
      (node (ref "R16") (pin "2") (pinfunction "2_2") (pintype "passive"))
      (node (ref "U7") (pin "5") (pinfunction "DO2-_5") (pintype "passive"))
    )
    (net (code "115") (name "/bus16") (class "Default")
      (node (ref "P7") (pin "16") (pinfunction "16_16") (pintype "passive"))
      (node (ref "U11") (pin "1A23") (pinfunction "W8/IO_1A23") (pintype "passive"))
      (node (ref "U6") (pin "9") (pinfunction "DI3_9") (pintype "passive"))
    )
    (net (code "116") (name "/bus16_n") (class "Default")
      (node (ref "J1") (pin "113") (pinfunction "B53_113") (pintype "passive"))
      (node (ref "J10") (pin "113") (pinfunction "B53_113") (pintype "passive"))
      (node (ref "J11") (pin "113") (pinfunction "B53_113") (pintype "passive"))
      (node (ref "J12") (pin "113") (pinfunction "B53_113") (pintype "passive"))
      (node (ref "J13") (pin "113") (pinfunction "B53_113") (pintype "passive"))
      (node (ref "J14") (pin "113") (pinfunction "B53_113") (pintype "passive"))
      (node (ref "J15") (pin "113") (pinfunction "B53_113") (pintype "passive"))
      (node (ref "J16") (pin "113") (pinfunction "B53_113") (pintype "passive"))
      (node (ref "J2") (pin "113") (pinfunction "B53_113") (pintype "passive"))
      (node (ref "J3") (pin "113") (pinfunction "B53_113") (pintype "passive"))
      (node (ref "J4") (pin "113") (pinfunction "B53_113") (pintype "passive"))
      (node (ref "J5") (pin "113") (pinfunction "B53_113") (pintype "passive"))
      (node (ref "J6") (pin "113") (pinfunction "B53_113") (pintype "passive"))
      (node (ref "J7") (pin "113") (pinfunction "B53_113") (pintype "passive"))
      (node (ref "J8") (pin "113") (pinfunction "B53_113") (pintype "passive"))
      (node (ref "J9") (pin "113") (pinfunction "B53_113") (pintype "passive"))
      (node (ref "R17") (pin "1") (pinfunction "1_1") (pintype "passive"))
      (node (ref "U6") (pin "10") (pinfunction "DO3+_10") (pintype "passive"))
    )
    (net (code "117") (name "/bus16_p") (class "Default")
      (node (ref "J1") (pin "114") (pinfunction "B54_114") (pintype "passive"))
      (node (ref "J10") (pin "114") (pinfunction "B54_114") (pintype "passive"))
      (node (ref "J11") (pin "114") (pinfunction "B54_114") (pintype "passive"))
      (node (ref "J12") (pin "114") (pinfunction "B54_114") (pintype "passive"))
      (node (ref "J13") (pin "114") (pinfunction "B54_114") (pintype "passive"))
      (node (ref "J14") (pin "114") (pinfunction "B54_114") (pintype "passive"))
      (node (ref "J15") (pin "114") (pinfunction "B54_114") (pintype "passive"))
      (node (ref "J16") (pin "114") (pinfunction "B54_114") (pintype "passive"))
      (node (ref "J2") (pin "114") (pinfunction "B54_114") (pintype "passive"))
      (node (ref "J3") (pin "114") (pinfunction "B54_114") (pintype "passive"))
      (node (ref "J4") (pin "114") (pinfunction "B54_114") (pintype "passive"))
      (node (ref "J5") (pin "114") (pinfunction "B54_114") (pintype "passive"))
      (node (ref "J6") (pin "114") (pinfunction "B54_114") (pintype "passive"))
      (node (ref "J7") (pin "114") (pinfunction "B54_114") (pintype "passive"))
      (node (ref "J8") (pin "114") (pinfunction "B54_114") (pintype "passive"))
      (node (ref "J9") (pin "114") (pinfunction "B54_114") (pintype "passive"))
      (node (ref "R17") (pin "2") (pinfunction "2_2") (pintype "passive"))
      (node (ref "U6") (pin "11") (pinfunction "DO3-_11") (pintype "passive"))
    )
    (net (code "118") (name "/bus17") (class "Default")
      (node (ref "P7") (pin "15") (pinfunction "15_15") (pintype "passive"))
      (node (ref "U11") (pin "1A20") (pinfunction "U10/B16n_1A20") (pintype "passive"))
      (node (ref "U6") (pin "15") (pinfunction "DI4_15") (pintype "passive"))
    )
    (net (code "119") (name "/bus17_n") (class "Default")
      (node (ref "J1") (pin "116") (pinfunction "B56_116") (pintype "passive"))
      (node (ref "J10") (pin "116") (pinfunction "B56_116") (pintype "passive"))
      (node (ref "J11") (pin "116") (pinfunction "B56_116") (pintype "passive"))
      (node (ref "J12") (pin "116") (pinfunction "B56_116") (pintype "passive"))
      (node (ref "J13") (pin "116") (pinfunction "B56_116") (pintype "passive"))
      (node (ref "J14") (pin "116") (pinfunction "B56_116") (pintype "passive"))
      (node (ref "J15") (pin "116") (pinfunction "B56_116") (pintype "passive"))
      (node (ref "J16") (pin "116") (pinfunction "B56_116") (pintype "passive"))
      (node (ref "J2") (pin "116") (pinfunction "B56_116") (pintype "passive"))
      (node (ref "J3") (pin "116") (pinfunction "B56_116") (pintype "passive"))
      (node (ref "J4") (pin "116") (pinfunction "B56_116") (pintype "passive"))
      (node (ref "J5") (pin "116") (pinfunction "B56_116") (pintype "passive"))
      (node (ref "J6") (pin "116") (pinfunction "B56_116") (pintype "passive"))
      (node (ref "J7") (pin "116") (pinfunction "B56_116") (pintype "passive"))
      (node (ref "J8") (pin "116") (pinfunction "B56_116") (pintype "passive"))
      (node (ref "J9") (pin "116") (pinfunction "B56_116") (pintype "passive"))
      (node (ref "R18") (pin "1") (pinfunction "1_1") (pintype "passive"))
      (node (ref "U6") (pin "14") (pinfunction "DO4+_14") (pintype "passive"))
    )
    (net (code "120") (name "/bus17_p") (class "Default")
      (node (ref "J1") (pin "115") (pinfunction "B55_115") (pintype "passive"))
      (node (ref "J10") (pin "115") (pinfunction "B55_115") (pintype "passive"))
      (node (ref "J11") (pin "115") (pinfunction "B55_115") (pintype "passive"))
      (node (ref "J12") (pin "115") (pinfunction "B55_115") (pintype "passive"))
      (node (ref "J13") (pin "115") (pinfunction "B55_115") (pintype "passive"))
      (node (ref "J14") (pin "115") (pinfunction "B55_115") (pintype "passive"))
      (node (ref "J15") (pin "115") (pinfunction "B55_115") (pintype "passive"))
      (node (ref "J16") (pin "115") (pinfunction "B55_115") (pintype "passive"))
      (node (ref "J2") (pin "115") (pinfunction "B55_115") (pintype "passive"))
      (node (ref "J3") (pin "115") (pinfunction "B55_115") (pintype "passive"))
      (node (ref "J4") (pin "115") (pinfunction "B55_115") (pintype "passive"))
      (node (ref "J5") (pin "115") (pinfunction "B55_115") (pintype "passive"))
      (node (ref "J6") (pin "115") (pinfunction "B55_115") (pintype "passive"))
      (node (ref "J7") (pin "115") (pinfunction "B55_115") (pintype "passive"))
      (node (ref "J8") (pin "115") (pinfunction "B55_115") (pintype "passive"))
      (node (ref "J9") (pin "115") (pinfunction "B55_115") (pintype "passive"))
      (node (ref "R18") (pin "2") (pinfunction "2_2") (pintype "passive"))
      (node (ref "U6") (pin "13") (pinfunction "DO4-_13") (pintype "passive"))
    )
    (net (code "121") (name "/bus18") (class "Default")
      (node (ref "P7") (pin "18") (pinfunction "18_18") (pintype "passive"))
      (node (ref "U11") (pin "1A29") (pinfunction "V10/B15p_1A29") (pintype "passive"))
      (node (ref "U6") (pin "1") (pinfunction "DI1_1") (pintype "passive"))
    )
    (net (code "122") (name "/bus18_n") (class "Default")
      (node (ref "J1") (pin "109") (pinfunction "B49_109") (pintype "passive"))
      (node (ref "J10") (pin "109") (pinfunction "B49_109") (pintype "passive"))
      (node (ref "J11") (pin "109") (pinfunction "B49_109") (pintype "passive"))
      (node (ref "J12") (pin "109") (pinfunction "B49_109") (pintype "passive"))
      (node (ref "J13") (pin "109") (pinfunction "B49_109") (pintype "passive"))
      (node (ref "J14") (pin "109") (pinfunction "B49_109") (pintype "passive"))
      (node (ref "J15") (pin "109") (pinfunction "B49_109") (pintype "passive"))
      (node (ref "J16") (pin "109") (pinfunction "B49_109") (pintype "passive"))
      (node (ref "J2") (pin "109") (pinfunction "B49_109") (pintype "passive"))
      (node (ref "J3") (pin "109") (pinfunction "B49_109") (pintype "passive"))
      (node (ref "J4") (pin "109") (pinfunction "B49_109") (pintype "passive"))
      (node (ref "J5") (pin "109") (pinfunction "B49_109") (pintype "passive"))
      (node (ref "J6") (pin "109") (pinfunction "B49_109") (pintype "passive"))
      (node (ref "J7") (pin "109") (pinfunction "B49_109") (pintype "passive"))
      (node (ref "J8") (pin "109") (pinfunction "B49_109") (pintype "passive"))
      (node (ref "J9") (pin "109") (pinfunction "B49_109") (pintype "passive"))
      (node (ref "R19") (pin "1") (pinfunction "1_1") (pintype "passive"))
      (node (ref "U6") (pin "2") (pinfunction "DO1+_2") (pintype "passive"))
    )
    (net (code "123") (name "/bus18_p") (class "Default")
      (node (ref "J1") (pin "110") (pinfunction "B50_110") (pintype "passive"))
      (node (ref "J10") (pin "110") (pinfunction "B50_110") (pintype "passive"))
      (node (ref "J11") (pin "110") (pinfunction "B50_110") (pintype "passive"))
      (node (ref "J12") (pin "110") (pinfunction "B50_110") (pintype "passive"))
      (node (ref "J13") (pin "110") (pinfunction "B50_110") (pintype "passive"))
      (node (ref "J14") (pin "110") (pinfunction "B50_110") (pintype "passive"))
      (node (ref "J15") (pin "110") (pinfunction "B50_110") (pintype "passive"))
      (node (ref "J16") (pin "110") (pinfunction "B50_110") (pintype "passive"))
      (node (ref "J2") (pin "110") (pinfunction "B50_110") (pintype "passive"))
      (node (ref "J3") (pin "110") (pinfunction "B50_110") (pintype "passive"))
      (node (ref "J4") (pin "110") (pinfunction "B50_110") (pintype "passive"))
      (node (ref "J5") (pin "110") (pinfunction "B50_110") (pintype "passive"))
      (node (ref "J6") (pin "110") (pinfunction "B50_110") (pintype "passive"))
      (node (ref "J7") (pin "110") (pinfunction "B50_110") (pintype "passive"))
      (node (ref "J8") (pin "110") (pinfunction "B50_110") (pintype "passive"))
      (node (ref "J9") (pin "110") (pinfunction "B50_110") (pintype "passive"))
      (node (ref "R19") (pin "2") (pinfunction "2_2") (pintype "passive"))
      (node (ref "U6") (pin "3") (pinfunction "DO1-_3") (pintype "passive"))
    )
    (net (code "124") (name "/bus19") (class "Default")
      (node (ref "P7") (pin "17") (pinfunction "17_17") (pintype "passive"))
      (node (ref "U11") (pin "1A28") (pinfunction "V8/B8n_1A28") (pintype "passive"))
      (node (ref "U6") (pin "7") (pinfunction "DI2_7") (pintype "passive"))
    )
    (net (code "125") (name "/bus19_n") (class "Default")
      (node (ref "J1") (pin "112") (pinfunction "B52_112") (pintype "passive"))
      (node (ref "J10") (pin "112") (pinfunction "B52_112") (pintype "passive"))
      (node (ref "J11") (pin "112") (pinfunction "B52_112") (pintype "passive"))
      (node (ref "J12") (pin "112") (pinfunction "B52_112") (pintype "passive"))
      (node (ref "J13") (pin "112") (pinfunction "B52_112") (pintype "passive"))
      (node (ref "J14") (pin "112") (pinfunction "B52_112") (pintype "passive"))
      (node (ref "J15") (pin "112") (pinfunction "B52_112") (pintype "passive"))
      (node (ref "J16") (pin "112") (pinfunction "B52_112") (pintype "passive"))
      (node (ref "J2") (pin "112") (pinfunction "B52_112") (pintype "passive"))
      (node (ref "J3") (pin "112") (pinfunction "B52_112") (pintype "passive"))
      (node (ref "J4") (pin "112") (pinfunction "B52_112") (pintype "passive"))
      (node (ref "J5") (pin "112") (pinfunction "B52_112") (pintype "passive"))
      (node (ref "J6") (pin "112") (pinfunction "B52_112") (pintype "passive"))
      (node (ref "J7") (pin "112") (pinfunction "B52_112") (pintype "passive"))
      (node (ref "J8") (pin "112") (pinfunction "B52_112") (pintype "passive"))
      (node (ref "J9") (pin "112") (pinfunction "B52_112") (pintype "passive"))
      (node (ref "R20") (pin "1") (pinfunction "1_1") (pintype "passive"))
      (node (ref "U6") (pin "6") (pinfunction "DO2+_6") (pintype "passive"))
    )
    (net (code "126") (name "/bus19_p") (class "Default")
      (node (ref "J1") (pin "111") (pinfunction "B51_111") (pintype "passive"))
      (node (ref "J10") (pin "111") (pinfunction "B51_111") (pintype "passive"))
      (node (ref "J11") (pin "111") (pinfunction "B51_111") (pintype "passive"))
      (node (ref "J12") (pin "111") (pinfunction "B51_111") (pintype "passive"))
      (node (ref "J13") (pin "111") (pinfunction "B51_111") (pintype "passive"))
      (node (ref "J14") (pin "111") (pinfunction "B51_111") (pintype "passive"))
      (node (ref "J15") (pin "111") (pinfunction "B51_111") (pintype "passive"))
      (node (ref "J16") (pin "111") (pinfunction "B51_111") (pintype "passive"))
      (node (ref "J2") (pin "111") (pinfunction "B51_111") (pintype "passive"))
      (node (ref "J3") (pin "111") (pinfunction "B51_111") (pintype "passive"))
      (node (ref "J4") (pin "111") (pinfunction "B51_111") (pintype "passive"))
      (node (ref "J5") (pin "111") (pinfunction "B51_111") (pintype "passive"))
      (node (ref "J6") (pin "111") (pinfunction "B51_111") (pintype "passive"))
      (node (ref "J7") (pin "111") (pinfunction "B51_111") (pintype "passive"))
      (node (ref "J8") (pin "111") (pinfunction "B51_111") (pintype "passive"))
      (node (ref "J9") (pin "111") (pinfunction "B51_111") (pintype "passive"))
      (node (ref "R20") (pin "2") (pinfunction "2_2") (pintype "passive"))
      (node (ref "U6") (pin "5") (pinfunction "DO2-_5") (pintype "passive"))
    )
    (net (code "127") (name "/bus20") (class "Default")
      (node (ref "P7") (pin "20") (pinfunction "20_20") (pintype "passive"))
      (node (ref "U11") (pin "1A31") (pinfunction "U9/B8p_1A31") (pintype "passive"))
      (node (ref "U5") (pin "9") (pinfunction "DI3_9") (pintype "passive"))
    )
    (net (code "128") (name "/bus20_n") (class "Default")
      (node (ref "J1") (pin "104") (pinfunction "B44_104") (pintype "passive"))
      (node (ref "J10") (pin "104") (pinfunction "B44_104") (pintype "passive"))
      (node (ref "J11") (pin "104") (pinfunction "B44_104") (pintype "passive"))
      (node (ref "J12") (pin "104") (pinfunction "B44_104") (pintype "passive"))
      (node (ref "J13") (pin "104") (pinfunction "B44_104") (pintype "passive"))
      (node (ref "J14") (pin "104") (pinfunction "B44_104") (pintype "passive"))
      (node (ref "J15") (pin "104") (pinfunction "B44_104") (pintype "passive"))
      (node (ref "J16") (pin "104") (pinfunction "B44_104") (pintype "passive"))
      (node (ref "J2") (pin "104") (pinfunction "B44_104") (pintype "passive"))
      (node (ref "J3") (pin "104") (pinfunction "B44_104") (pintype "passive"))
      (node (ref "J4") (pin "104") (pinfunction "B44_104") (pintype "passive"))
      (node (ref "J5") (pin "104") (pinfunction "B44_104") (pintype "passive"))
      (node (ref "J6") (pin "104") (pinfunction "B44_104") (pintype "passive"))
      (node (ref "J7") (pin "104") (pinfunction "B44_104") (pintype "passive"))
      (node (ref "J8") (pin "104") (pinfunction "B44_104") (pintype "passive"))
      (node (ref "J9") (pin "104") (pinfunction "B44_104") (pintype "passive"))
      (node (ref "R21") (pin "1") (pinfunction "1_1") (pintype "passive"))
      (node (ref "U5") (pin "10") (pinfunction "DO3+_10") (pintype "passive"))
    )
    (net (code "129") (name "/bus20_p") (class "Default")
      (node (ref "J1") (pin "105") (pinfunction "B45_105") (pintype "passive"))
      (node (ref "J10") (pin "105") (pinfunction "B45_105") (pintype "passive"))
      (node (ref "J11") (pin "105") (pinfunction "B45_105") (pintype "passive"))
      (node (ref "J12") (pin "105") (pinfunction "B45_105") (pintype "passive"))
      (node (ref "J13") (pin "105") (pinfunction "B45_105") (pintype "passive"))
      (node (ref "J14") (pin "105") (pinfunction "B45_105") (pintype "passive"))
      (node (ref "J15") (pin "105") (pinfunction "B45_105") (pintype "passive"))
      (node (ref "J16") (pin "105") (pinfunction "B45_105") (pintype "passive"))
      (node (ref "J2") (pin "105") (pinfunction "B45_105") (pintype "passive"))
      (node (ref "J3") (pin "105") (pinfunction "B45_105") (pintype "passive"))
      (node (ref "J4") (pin "105") (pinfunction "B45_105") (pintype "passive"))
      (node (ref "J5") (pin "105") (pinfunction "B45_105") (pintype "passive"))
      (node (ref "J6") (pin "105") (pinfunction "B45_105") (pintype "passive"))
      (node (ref "J7") (pin "105") (pinfunction "B45_105") (pintype "passive"))
      (node (ref "J8") (pin "105") (pinfunction "B45_105") (pintype "passive"))
      (node (ref "J9") (pin "105") (pinfunction "B45_105") (pintype "passive"))
      (node (ref "R21") (pin "2") (pinfunction "2_2") (pintype "passive"))
      (node (ref "U5") (pin "11") (pinfunction "DO3-_11") (pintype "passive"))
    )
    (net (code "130") (name "/bus21") (class "Default")
      (node (ref "P7") (pin "19") (pinfunction "19_19") (pintype "passive"))
      (node (ref "U11") (pin "1A30") (pinfunction "Y6/IO_1A30") (pintype "passive"))
      (node (ref "U5") (pin "15") (pinfunction "DI4_15") (pintype "passive"))
    )
    (net (code "131") (name "/bus21_n") (class "Default")
      (node (ref "J1") (pin "107") (pinfunction "B47_107") (pintype "passive"))
      (node (ref "J10") (pin "107") (pinfunction "B47_107") (pintype "passive"))
      (node (ref "J11") (pin "107") (pinfunction "B47_107") (pintype "passive"))
      (node (ref "J12") (pin "107") (pinfunction "B47_107") (pintype "passive"))
      (node (ref "J13") (pin "107") (pinfunction "B47_107") (pintype "passive"))
      (node (ref "J14") (pin "107") (pinfunction "B47_107") (pintype "passive"))
      (node (ref "J15") (pin "107") (pinfunction "B47_107") (pintype "passive"))
      (node (ref "J16") (pin "107") (pinfunction "B47_107") (pintype "passive"))
      (node (ref "J2") (pin "107") (pinfunction "B47_107") (pintype "passive"))
      (node (ref "J3") (pin "107") (pinfunction "B47_107") (pintype "passive"))
      (node (ref "J4") (pin "107") (pinfunction "B47_107") (pintype "passive"))
      (node (ref "J5") (pin "107") (pinfunction "B47_107") (pintype "passive"))
      (node (ref "J6") (pin "107") (pinfunction "B47_107") (pintype "passive"))
      (node (ref "J7") (pin "107") (pinfunction "B47_107") (pintype "passive"))
      (node (ref "J8") (pin "107") (pinfunction "B47_107") (pintype "passive"))
      (node (ref "J9") (pin "107") (pinfunction "B47_107") (pintype "passive"))
      (node (ref "R22") (pin "1") (pinfunction "1_1") (pintype "passive"))
      (node (ref "U5") (pin "14") (pinfunction "DO4+_14") (pintype "passive"))
    )
    (net (code "132") (name "/bus21_p") (class "Default")
      (node (ref "J1") (pin "106") (pinfunction "B46_106") (pintype "passive"))
      (node (ref "J10") (pin "106") (pinfunction "B46_106") (pintype "passive"))
      (node (ref "J11") (pin "106") (pinfunction "B46_106") (pintype "passive"))
      (node (ref "J12") (pin "106") (pinfunction "B46_106") (pintype "passive"))
      (node (ref "J13") (pin "106") (pinfunction "B46_106") (pintype "passive"))
      (node (ref "J14") (pin "106") (pinfunction "B46_106") (pintype "passive"))
      (node (ref "J15") (pin "106") (pinfunction "B46_106") (pintype "passive"))
      (node (ref "J16") (pin "106") (pinfunction "B46_106") (pintype "passive"))
      (node (ref "J2") (pin "106") (pinfunction "B46_106") (pintype "passive"))
      (node (ref "J3") (pin "106") (pinfunction "B46_106") (pintype "passive"))
      (node (ref "J4") (pin "106") (pinfunction "B46_106") (pintype "passive"))
      (node (ref "J5") (pin "106") (pinfunction "B46_106") (pintype "passive"))
      (node (ref "J6") (pin "106") (pinfunction "B46_106") (pintype "passive"))
      (node (ref "J7") (pin "106") (pinfunction "B46_106") (pintype "passive"))
      (node (ref "J8") (pin "106") (pinfunction "B46_106") (pintype "passive"))
      (node (ref "J9") (pin "106") (pinfunction "B46_106") (pintype "passive"))
      (node (ref "R22") (pin "2") (pinfunction "2_2") (pintype "passive"))
      (node (ref "U5") (pin "13") (pinfunction "DO4-_13") (pintype "passive"))
    )
    (net (code "133") (name "/bus22") (class "Default")
      (node (ref "P7") (pin "26") (pinfunction "26_26") (pintype "passive"))
      (node (ref "U11") (pin "1A33") (pinfunction "Y3/B3n_1A33") (pintype "passive"))
      (node (ref "U5") (pin "1") (pinfunction "DI1_1") (pintype "passive"))
    )
    (net (code "134") (name "/bus22_n") (class "Default")
      (node (ref "J1") (pin "100") (pinfunction "B40_100") (pintype "passive"))
      (node (ref "J10") (pin "100") (pinfunction "B40_100") (pintype "passive"))
      (node (ref "J11") (pin "100") (pinfunction "B40_100") (pintype "passive"))
      (node (ref "J12") (pin "100") (pinfunction "B40_100") (pintype "passive"))
      (node (ref "J13") (pin "100") (pinfunction "B40_100") (pintype "passive"))
      (node (ref "J14") (pin "100") (pinfunction "B40_100") (pintype "passive"))
      (node (ref "J15") (pin "100") (pinfunction "B40_100") (pintype "passive"))
      (node (ref "J16") (pin "100") (pinfunction "B40_100") (pintype "passive"))
      (node (ref "J2") (pin "100") (pinfunction "B40_100") (pintype "passive"))
      (node (ref "J3") (pin "100") (pinfunction "B40_100") (pintype "passive"))
      (node (ref "J4") (pin "100") (pinfunction "B40_100") (pintype "passive"))
      (node (ref "J5") (pin "100") (pinfunction "B40_100") (pintype "passive"))
      (node (ref "J6") (pin "100") (pinfunction "B40_100") (pintype "passive"))
      (node (ref "J7") (pin "100") (pinfunction "B40_100") (pintype "passive"))
      (node (ref "J8") (pin "100") (pinfunction "B40_100") (pintype "passive"))
      (node (ref "J9") (pin "100") (pinfunction "B40_100") (pintype "passive"))
      (node (ref "R23") (pin "1") (pinfunction "1_1") (pintype "passive"))
      (node (ref "U5") (pin "2") (pinfunction "DO1+_2") (pintype "passive"))
    )
    (net (code "135") (name "/bus22_p") (class "Default")
      (node (ref "J1") (pin "101") (pinfunction "B41_101") (pintype "passive"))
      (node (ref "J10") (pin "101") (pinfunction "B41_101") (pintype "passive"))
      (node (ref "J11") (pin "101") (pinfunction "B41_101") (pintype "passive"))
      (node (ref "J12") (pin "101") (pinfunction "B41_101") (pintype "passive"))
      (node (ref "J13") (pin "101") (pinfunction "B41_101") (pintype "passive"))
      (node (ref "J14") (pin "101") (pinfunction "B41_101") (pintype "passive"))
      (node (ref "J15") (pin "101") (pinfunction "B41_101") (pintype "passive"))
      (node (ref "J16") (pin "101") (pinfunction "B41_101") (pintype "passive"))
      (node (ref "J2") (pin "101") (pinfunction "B41_101") (pintype "passive"))
      (node (ref "J3") (pin "101") (pinfunction "B41_101") (pintype "passive"))
      (node (ref "J4") (pin "101") (pinfunction "B41_101") (pintype "passive"))
      (node (ref "J5") (pin "101") (pinfunction "B41_101") (pintype "passive"))
      (node (ref "J6") (pin "101") (pinfunction "B41_101") (pintype "passive"))
      (node (ref "J7") (pin "101") (pinfunction "B41_101") (pintype "passive"))
      (node (ref "J8") (pin "101") (pinfunction "B41_101") (pintype "passive"))
      (node (ref "J9") (pin "101") (pinfunction "B41_101") (pintype "passive"))
      (node (ref "R23") (pin "2") (pinfunction "2_2") (pintype "passive"))
      (node (ref "U5") (pin "3") (pinfunction "DO1-_3") (pintype "passive"))
    )
    (net (code "136") (name "/bus23") (class "Default")
      (node (ref "P7") (pin "25") (pinfunction "25_25") (pintype "passive"))
      (node (ref "U11") (pin "1A32") (pinfunction "V6/B1p_1A32") (pintype "passive"))
      (node (ref "U5") (pin "7") (pinfunction "DI2_7") (pintype "passive"))
    )
    (net (code "137") (name "/bus23_n") (class "Default")
      (node (ref "J1") (pin "103") (pinfunction "B43_103") (pintype "passive"))
      (node (ref "J10") (pin "103") (pinfunction "B43_103") (pintype "passive"))
      (node (ref "J11") (pin "103") (pinfunction "B43_103") (pintype "passive"))
      (node (ref "J12") (pin "103") (pinfunction "B43_103") (pintype "passive"))
      (node (ref "J13") (pin "103") (pinfunction "B43_103") (pintype "passive"))
      (node (ref "J14") (pin "103") (pinfunction "B43_103") (pintype "passive"))
      (node (ref "J15") (pin "103") (pinfunction "B43_103") (pintype "passive"))
      (node (ref "J16") (pin "103") (pinfunction "B43_103") (pintype "passive"))
      (node (ref "J2") (pin "103") (pinfunction "B43_103") (pintype "passive"))
      (node (ref "J3") (pin "103") (pinfunction "B43_103") (pintype "passive"))
      (node (ref "J4") (pin "103") (pinfunction "B43_103") (pintype "passive"))
      (node (ref "J5") (pin "103") (pinfunction "B43_103") (pintype "passive"))
      (node (ref "J6") (pin "103") (pinfunction "B43_103") (pintype "passive"))
      (node (ref "J7") (pin "103") (pinfunction "B43_103") (pintype "passive"))
      (node (ref "J8") (pin "103") (pinfunction "B43_103") (pintype "passive"))
      (node (ref "J9") (pin "103") (pinfunction "B43_103") (pintype "passive"))
      (node (ref "R24") (pin "1") (pinfunction "1_1") (pintype "passive"))
      (node (ref "U5") (pin "6") (pinfunction "DO2+_6") (pintype "passive"))
    )
    (net (code "138") (name "/bus23_p") (class "Default")
      (node (ref "J1") (pin "102") (pinfunction "B42_102") (pintype "passive"))
      (node (ref "J10") (pin "102") (pinfunction "B42_102") (pintype "passive"))
      (node (ref "J11") (pin "102") (pinfunction "B42_102") (pintype "passive"))
      (node (ref "J12") (pin "102") (pinfunction "B42_102") (pintype "passive"))
      (node (ref "J13") (pin "102") (pinfunction "B42_102") (pintype "passive"))
      (node (ref "J14") (pin "102") (pinfunction "B42_102") (pintype "passive"))
      (node (ref "J15") (pin "102") (pinfunction "B42_102") (pintype "passive"))
      (node (ref "J16") (pin "102") (pinfunction "B42_102") (pintype "passive"))
      (node (ref "J2") (pin "102") (pinfunction "B42_102") (pintype "passive"))
      (node (ref "J3") (pin "102") (pinfunction "B42_102") (pintype "passive"))
      (node (ref "J4") (pin "102") (pinfunction "B42_102") (pintype "passive"))
      (node (ref "J5") (pin "102") (pinfunction "B42_102") (pintype "passive"))
      (node (ref "J6") (pin "102") (pinfunction "B42_102") (pintype "passive"))
      (node (ref "J7") (pin "102") (pinfunction "B42_102") (pintype "passive"))
      (node (ref "J8") (pin "102") (pinfunction "B42_102") (pintype "passive"))
      (node (ref "J9") (pin "102") (pinfunction "B42_102") (pintype "passive"))
      (node (ref "R24") (pin "2") (pinfunction "2_2") (pintype "passive"))
      (node (ref "U5") (pin "5") (pinfunction "DO2-_5") (pintype "passive"))
    )
    (net (code "139") (name "/bus24") (class "Default")
      (node (ref "P7") (pin "28") (pinfunction "28_28") (pintype "passive"))
      (node (ref "U11") (pin "1A35") (pinfunction "L6/L16p_1A35") (pintype "passive"))
      (node (ref "U4") (pin "9") (pinfunction "DI3_9") (pintype "passive"))
    )
    (net (code "140") (name "/bus24_n") (class "Default")
      (node (ref "J1") (pin "95") (pinfunction "B35_95") (pintype "passive"))
      (node (ref "J10") (pin "95") (pinfunction "B35_95") (pintype "passive"))
      (node (ref "J11") (pin "95") (pinfunction "B35_95") (pintype "passive"))
      (node (ref "J12") (pin "95") (pinfunction "B35_95") (pintype "passive"))
      (node (ref "J13") (pin "95") (pinfunction "B35_95") (pintype "passive"))
      (node (ref "J14") (pin "95") (pinfunction "B35_95") (pintype "passive"))
      (node (ref "J15") (pin "95") (pinfunction "B35_95") (pintype "passive"))
      (node (ref "J16") (pin "95") (pinfunction "B35_95") (pintype "passive"))
      (node (ref "J2") (pin "95") (pinfunction "B35_95") (pintype "passive"))
      (node (ref "J3") (pin "95") (pinfunction "B35_95") (pintype "passive"))
      (node (ref "J4") (pin "95") (pinfunction "B35_95") (pintype "passive"))
      (node (ref "J5") (pin "95") (pinfunction "B35_95") (pintype "passive"))
      (node (ref "J6") (pin "95") (pinfunction "B35_95") (pintype "passive"))
      (node (ref "J7") (pin "95") (pinfunction "B35_95") (pintype "passive"))
      (node (ref "J8") (pin "95") (pinfunction "B35_95") (pintype "passive"))
      (node (ref "J9") (pin "95") (pinfunction "B35_95") (pintype "passive"))
      (node (ref "R25") (pin "1") (pinfunction "1_1") (pintype "passive"))
      (node (ref "U4") (pin "10") (pinfunction "DO3+_10") (pintype "passive"))
    )
    (net (code "141") (name "/bus24_p") (class "Default")
      (node (ref "J1") (pin "96") (pinfunction "B36_96") (pintype "passive"))
      (node (ref "J10") (pin "96") (pinfunction "B36_96") (pintype "passive"))
      (node (ref "J11") (pin "96") (pinfunction "B36_96") (pintype "passive"))
      (node (ref "J12") (pin "96") (pinfunction "B36_96") (pintype "passive"))
      (node (ref "J13") (pin "96") (pinfunction "B36_96") (pintype "passive"))
      (node (ref "J14") (pin "96") (pinfunction "B36_96") (pintype "passive"))
      (node (ref "J15") (pin "96") (pinfunction "B36_96") (pintype "passive"))
      (node (ref "J16") (pin "96") (pinfunction "B36_96") (pintype "passive"))
      (node (ref "J2") (pin "96") (pinfunction "B36_96") (pintype "passive"))
      (node (ref "J3") (pin "96") (pinfunction "B36_96") (pintype "passive"))
      (node (ref "J4") (pin "96") (pinfunction "B36_96") (pintype "passive"))
      (node (ref "J5") (pin "96") (pinfunction "B36_96") (pintype "passive"))
      (node (ref "J6") (pin "96") (pinfunction "B36_96") (pintype "passive"))
      (node (ref "J7") (pin "96") (pinfunction "B36_96") (pintype "passive"))
      (node (ref "J8") (pin "96") (pinfunction "B36_96") (pintype "passive"))
      (node (ref "J9") (pin "96") (pinfunction "B36_96") (pintype "passive"))
      (node (ref "R25") (pin "2") (pinfunction "2_2") (pintype "passive"))
      (node (ref "U4") (pin "11") (pinfunction "DO3-_11") (pintype "passive"))
    )
    (net (code "142") (name "/bus25") (class "Default")
      (node (ref "P7") (pin "27") (pinfunction "27_27") (pintype "passive"))
      (node (ref "U11") (pin "1A34") (pinfunction "V5/B1n_1A34") (pintype "passive"))
      (node (ref "U4") (pin "15") (pinfunction "DI4_15") (pintype "passive"))
    )
    (net (code "143") (name "/bus25_n") (class "Default")
      (node (ref "J1") (pin "98") (pinfunction "B38_98") (pintype "passive"))
      (node (ref "J10") (pin "98") (pinfunction "B38_98") (pintype "passive"))
      (node (ref "J11") (pin "98") (pinfunction "B38_98") (pintype "passive"))
      (node (ref "J12") (pin "98") (pinfunction "B38_98") (pintype "passive"))
      (node (ref "J13") (pin "98") (pinfunction "B38_98") (pintype "passive"))
      (node (ref "J14") (pin "98") (pinfunction "B38_98") (pintype "passive"))
      (node (ref "J15") (pin "98") (pinfunction "B38_98") (pintype "passive"))
      (node (ref "J16") (pin "98") (pinfunction "B38_98") (pintype "passive"))
      (node (ref "J2") (pin "98") (pinfunction "B38_98") (pintype "passive"))
      (node (ref "J3") (pin "98") (pinfunction "B38_98") (pintype "passive"))
      (node (ref "J4") (pin "98") (pinfunction "B38_98") (pintype "passive"))
      (node (ref "J5") (pin "98") (pinfunction "B38_98") (pintype "passive"))
      (node (ref "J6") (pin "98") (pinfunction "B38_98") (pintype "passive"))
      (node (ref "J7") (pin "98") (pinfunction "B38_98") (pintype "passive"))
      (node (ref "J8") (pin "98") (pinfunction "B38_98") (pintype "passive"))
      (node (ref "J9") (pin "98") (pinfunction "B38_98") (pintype "passive"))
      (node (ref "R26") (pin "1") (pinfunction "1_1") (pintype "passive"))
      (node (ref "U4") (pin "14") (pinfunction "DO4+_14") (pintype "passive"))
    )
    (net (code "144") (name "/bus25_p") (class "Default")
      (node (ref "J1") (pin "97") (pinfunction "B37_97") (pintype "passive"))
      (node (ref "J10") (pin "97") (pinfunction "B37_97") (pintype "passive"))
      (node (ref "J11") (pin "97") (pinfunction "B37_97") (pintype "passive"))
      (node (ref "J12") (pin "97") (pinfunction "B37_97") (pintype "passive"))
      (node (ref "J13") (pin "97") (pinfunction "B37_97") (pintype "passive"))
      (node (ref "J14") (pin "97") (pinfunction "B37_97") (pintype "passive"))
      (node (ref "J15") (pin "97") (pinfunction "B37_97") (pintype "passive"))
      (node (ref "J16") (pin "97") (pinfunction "B37_97") (pintype "passive"))
      (node (ref "J2") (pin "97") (pinfunction "B37_97") (pintype "passive"))
      (node (ref "J3") (pin "97") (pinfunction "B37_97") (pintype "passive"))
      (node (ref "J4") (pin "97") (pinfunction "B37_97") (pintype "passive"))
      (node (ref "J5") (pin "97") (pinfunction "B37_97") (pintype "passive"))
      (node (ref "J6") (pin "97") (pinfunction "B37_97") (pintype "passive"))
      (node (ref "J7") (pin "97") (pinfunction "B37_97") (pintype "passive"))
      (node (ref "J8") (pin "97") (pinfunction "B37_97") (pintype "passive"))
      (node (ref "J9") (pin "97") (pinfunction "B37_97") (pintype "passive"))
      (node (ref "R26") (pin "2") (pinfunction "2_2") (pintype "passive"))
      (node (ref "U4") (pin "13") (pinfunction "DO4-_13") (pintype "passive"))
    )
    (net (code "145") (name "/bus26") (class "Default")
      (node (ref "P7") (pin "30") (pinfunction "30_30") (pintype "passive"))
      (node (ref "U11") (pin "1B3") (pinfunction "M2/L17p_1B3") (pintype "passive"))
      (node (ref "U4") (pin "1") (pinfunction "DI1_1") (pintype "passive"))
    )
    (net (code "146") (name "/bus26_n") (class "Default")
      (node (ref "J1") (pin "91") (pinfunction "B31_91") (pintype "passive"))
      (node (ref "J10") (pin "91") (pinfunction "B31_91") (pintype "passive"))
      (node (ref "J11") (pin "91") (pinfunction "B31_91") (pintype "passive"))
      (node (ref "J12") (pin "91") (pinfunction "B31_91") (pintype "passive"))
      (node (ref "J13") (pin "91") (pinfunction "B31_91") (pintype "passive"))
      (node (ref "J14") (pin "91") (pinfunction "B31_91") (pintype "passive"))
      (node (ref "J15") (pin "91") (pinfunction "B31_91") (pintype "passive"))
      (node (ref "J16") (pin "91") (pinfunction "B31_91") (pintype "passive"))
      (node (ref "J2") (pin "91") (pinfunction "B31_91") (pintype "passive"))
      (node (ref "J3") (pin "91") (pinfunction "B31_91") (pintype "passive"))
      (node (ref "J4") (pin "91") (pinfunction "B31_91") (pintype "passive"))
      (node (ref "J5") (pin "91") (pinfunction "B31_91") (pintype "passive"))
      (node (ref "J6") (pin "91") (pinfunction "B31_91") (pintype "passive"))
      (node (ref "J7") (pin "91") (pinfunction "B31_91") (pintype "passive"))
      (node (ref "J8") (pin "91") (pinfunction "B31_91") (pintype "passive"))
      (node (ref "J9") (pin "91") (pinfunction "B31_91") (pintype "passive"))
      (node (ref "R27") (pin "1") (pinfunction "1_1") (pintype "passive"))
      (node (ref "U4") (pin "2") (pinfunction "DO1+_2") (pintype "passive"))
    )
    (net (code "147") (name "/bus26_p") (class "Default")
      (node (ref "J1") (pin "92") (pinfunction "B32_92") (pintype "passive"))
      (node (ref "J10") (pin "92") (pinfunction "B32_92") (pintype "passive"))
      (node (ref "J11") (pin "92") (pinfunction "B32_92") (pintype "passive"))
      (node (ref "J12") (pin "92") (pinfunction "B32_92") (pintype "passive"))
      (node (ref "J13") (pin "92") (pinfunction "B32_92") (pintype "passive"))
      (node (ref "J14") (pin "92") (pinfunction "B32_92") (pintype "passive"))
      (node (ref "J15") (pin "92") (pinfunction "B32_92") (pintype "passive"))
      (node (ref "J16") (pin "92") (pinfunction "B32_92") (pintype "passive"))
      (node (ref "J2") (pin "92") (pinfunction "B32_92") (pintype "passive"))
      (node (ref "J3") (pin "92") (pinfunction "B32_92") (pintype "passive"))
      (node (ref "J4") (pin "92") (pinfunction "B32_92") (pintype "passive"))
      (node (ref "J5") (pin "92") (pinfunction "B32_92") (pintype "passive"))
      (node (ref "J6") (pin "92") (pinfunction "B32_92") (pintype "passive"))
      (node (ref "J7") (pin "92") (pinfunction "B32_92") (pintype "passive"))
      (node (ref "J8") (pin "92") (pinfunction "B32_92") (pintype "passive"))
      (node (ref "J9") (pin "92") (pinfunction "B32_92") (pintype "passive"))
      (node (ref "R27") (pin "2") (pinfunction "2_2") (pintype "passive"))
      (node (ref "U4") (pin "3") (pinfunction "DO1-_3") (pintype "passive"))
    )
    (net (code "148") (name "/bus27") (class "Default")
      (node (ref "P7") (pin "29") (pinfunction "29_29") (pintype "passive"))
      (node (ref "U11") (pin "1A37") (pinfunction "M6/L16n_1A37") (pintype "passive"))
      (node (ref "U4") (pin "7") (pinfunction "DI2_7") (pintype "passive"))
    )
    (net (code "149") (name "/bus27_n") (class "Default")
      (node (ref "J1") (pin "94") (pinfunction "B34_94") (pintype "passive"))
      (node (ref "J10") (pin "94") (pinfunction "B34_94") (pintype "passive"))
      (node (ref "J11") (pin "94") (pinfunction "B34_94") (pintype "passive"))
      (node (ref "J12") (pin "94") (pinfunction "B34_94") (pintype "passive"))
      (node (ref "J13") (pin "94") (pinfunction "B34_94") (pintype "passive"))
      (node (ref "J14") (pin "94") (pinfunction "B34_94") (pintype "passive"))
      (node (ref "J15") (pin "94") (pinfunction "B34_94") (pintype "passive"))
      (node (ref "J16") (pin "94") (pinfunction "B34_94") (pintype "passive"))
      (node (ref "J2") (pin "94") (pinfunction "B34_94") (pintype "passive"))
      (node (ref "J3") (pin "94") (pinfunction "B34_94") (pintype "passive"))
      (node (ref "J4") (pin "94") (pinfunction "B34_94") (pintype "passive"))
      (node (ref "J5") (pin "94") (pinfunction "B34_94") (pintype "passive"))
      (node (ref "J6") (pin "94") (pinfunction "B34_94") (pintype "passive"))
      (node (ref "J7") (pin "94") (pinfunction "B34_94") (pintype "passive"))
      (node (ref "J8") (pin "94") (pinfunction "B34_94") (pintype "passive"))
      (node (ref "J9") (pin "94") (pinfunction "B34_94") (pintype "passive"))
      (node (ref "R28") (pin "1") (pinfunction "1_1") (pintype "passive"))
      (node (ref "U4") (pin "6") (pinfunction "DO2+_6") (pintype "passive"))
    )
    (net (code "150") (name "/bus27_p") (class "Default")
      (node (ref "J1") (pin "93") (pinfunction "B33_93") (pintype "passive"))
      (node (ref "J10") (pin "93") (pinfunction "B33_93") (pintype "passive"))
      (node (ref "J11") (pin "93") (pinfunction "B33_93") (pintype "passive"))
      (node (ref "J12") (pin "93") (pinfunction "B33_93") (pintype "passive"))
      (node (ref "J13") (pin "93") (pinfunction "B33_93") (pintype "passive"))
      (node (ref "J14") (pin "93") (pinfunction "B33_93") (pintype "passive"))
      (node (ref "J15") (pin "93") (pinfunction "B33_93") (pintype "passive"))
      (node (ref "J16") (pin "93") (pinfunction "B33_93") (pintype "passive"))
      (node (ref "J2") (pin "93") (pinfunction "B33_93") (pintype "passive"))
      (node (ref "J3") (pin "93") (pinfunction "B33_93") (pintype "passive"))
      (node (ref "J4") (pin "93") (pinfunction "B33_93") (pintype "passive"))
      (node (ref "J5") (pin "93") (pinfunction "B33_93") (pintype "passive"))
      (node (ref "J6") (pin "93") (pinfunction "B33_93") (pintype "passive"))
      (node (ref "J7") (pin "93") (pinfunction "B33_93") (pintype "passive"))
      (node (ref "J8") (pin "93") (pinfunction "B33_93") (pintype "passive"))
      (node (ref "J9") (pin "93") (pinfunction "B33_93") (pintype "passive"))
      (node (ref "R28") (pin "2") (pinfunction "2_2") (pintype "passive"))
      (node (ref "U4") (pin "5") (pinfunction "DO2-_5") (pintype "passive"))
    )
    (net (code "151") (name "/bus28") (class "Default")
      (node (ref "P7") (pin "31") (pinfunction "31_31") (pintype "passive"))
      (node (ref "U11") (pin "1B5") (pinfunction "M1/L17n_1B5") (pintype "passive"))
      (node (ref "U3") (pin "9") (pinfunction "DI3_9") (pintype "passive"))
    )
    (net (code "152") (name "/bus28_n") (class "Default")
      (node (ref "J1") (pin "86") (pinfunction "B26_86") (pintype "passive"))
      (node (ref "J10") (pin "86") (pinfunction "B26_86") (pintype "passive"))
      (node (ref "J11") (pin "86") (pinfunction "B26_86") (pintype "passive"))
      (node (ref "J12") (pin "86") (pinfunction "B26_86") (pintype "passive"))
      (node (ref "J13") (pin "86") (pinfunction "B26_86") (pintype "passive"))
      (node (ref "J14") (pin "86") (pinfunction "B26_86") (pintype "passive"))
      (node (ref "J15") (pin "86") (pinfunction "B26_86") (pintype "passive"))
      (node (ref "J16") (pin "86") (pinfunction "B26_86") (pintype "passive"))
      (node (ref "J2") (pin "86") (pinfunction "B26_86") (pintype "passive"))
      (node (ref "J3") (pin "86") (pinfunction "B26_86") (pintype "passive"))
      (node (ref "J4") (pin "86") (pinfunction "B26_86") (pintype "passive"))
      (node (ref "J5") (pin "86") (pinfunction "B26_86") (pintype "passive"))
      (node (ref "J6") (pin "86") (pinfunction "B26_86") (pintype "passive"))
      (node (ref "J7") (pin "86") (pinfunction "B26_86") (pintype "passive"))
      (node (ref "J8") (pin "86") (pinfunction "B26_86") (pintype "passive"))
      (node (ref "J9") (pin "86") (pinfunction "B26_86") (pintype "passive"))
      (node (ref "R29") (pin "1") (pinfunction "1_1") (pintype "passive"))
      (node (ref "U3") (pin "10") (pinfunction "DO3+_10") (pintype "passive"))
    )
    (net (code "153") (name "/bus28_p") (class "Default")
      (node (ref "J1") (pin "87") (pinfunction "B27_87") (pintype "passive"))
      (node (ref "J10") (pin "87") (pinfunction "B27_87") (pintype "passive"))
      (node (ref "J11") (pin "87") (pinfunction "B27_87") (pintype "passive"))
      (node (ref "J12") (pin "87") (pinfunction "B27_87") (pintype "passive"))
      (node (ref "J13") (pin "87") (pinfunction "B27_87") (pintype "passive"))
      (node (ref "J14") (pin "87") (pinfunction "B27_87") (pintype "passive"))
      (node (ref "J15") (pin "87") (pinfunction "B27_87") (pintype "passive"))
      (node (ref "J16") (pin "87") (pinfunction "B27_87") (pintype "passive"))
      (node (ref "J2") (pin "87") (pinfunction "B27_87") (pintype "passive"))
      (node (ref "J3") (pin "87") (pinfunction "B27_87") (pintype "passive"))
      (node (ref "J4") (pin "87") (pinfunction "B27_87") (pintype "passive"))
      (node (ref "J5") (pin "87") (pinfunction "B27_87") (pintype "passive"))
      (node (ref "J6") (pin "87") (pinfunction "B27_87") (pintype "passive"))
      (node (ref "J7") (pin "87") (pinfunction "B27_87") (pintype "passive"))
      (node (ref "J8") (pin "87") (pinfunction "B27_87") (pintype "passive"))
      (node (ref "J9") (pin "87") (pinfunction "B27_87") (pintype "passive"))
      (node (ref "R29") (pin "2") (pinfunction "2_2") (pintype "passive"))
      (node (ref "U3") (pin "11") (pinfunction "DO3-_11") (pintype "passive"))
    )
    (net (code "154") (name "/bus29") (class "Default")
      (node (ref "P7") (pin "32") (pinfunction "32_32") (pintype "passive"))
      (node (ref "U11") (pin "1B4") (pinfunction "U7/B2p_1B4") (pintype "passive"))
      (node (ref "U3") (pin "15") (pinfunction "DI4_15") (pintype "passive"))
    )
    (net (code "155") (name "/bus29_n") (class "Default")
      (node (ref "J1") (pin "89") (pinfunction "B29_89") (pintype "passive"))
      (node (ref "J10") (pin "89") (pinfunction "B29_89") (pintype "passive"))
      (node (ref "J11") (pin "89") (pinfunction "B29_89") (pintype "passive"))
      (node (ref "J12") (pin "89") (pinfunction "B29_89") (pintype "passive"))
      (node (ref "J13") (pin "89") (pinfunction "B29_89") (pintype "passive"))
      (node (ref "J14") (pin "89") (pinfunction "B29_89") (pintype "passive"))
      (node (ref "J15") (pin "89") (pinfunction "B29_89") (pintype "passive"))
      (node (ref "J16") (pin "89") (pinfunction "B29_89") (pintype "passive"))
      (node (ref "J2") (pin "89") (pinfunction "B29_89") (pintype "passive"))
      (node (ref "J3") (pin "89") (pinfunction "B29_89") (pintype "passive"))
      (node (ref "J4") (pin "89") (pinfunction "B29_89") (pintype "passive"))
      (node (ref "J5") (pin "89") (pinfunction "B29_89") (pintype "passive"))
      (node (ref "J6") (pin "89") (pinfunction "B29_89") (pintype "passive"))
      (node (ref "J7") (pin "89") (pinfunction "B29_89") (pintype "passive"))
      (node (ref "J8") (pin "89") (pinfunction "B29_89") (pintype "passive"))
      (node (ref "J9") (pin "89") (pinfunction "B29_89") (pintype "passive"))
      (node (ref "R30") (pin "1") (pinfunction "1_1") (pintype "passive"))
      (node (ref "U3") (pin "14") (pinfunction "DO4+_14") (pintype "passive"))
    )
    (net (code "156") (name "/bus29_p") (class "Default")
      (node (ref "J1") (pin "88") (pinfunction "B28_88") (pintype "passive"))
      (node (ref "J10") (pin "88") (pinfunction "B28_88") (pintype "passive"))
      (node (ref "J11") (pin "88") (pinfunction "B28_88") (pintype "passive"))
      (node (ref "J12") (pin "88") (pinfunction "B28_88") (pintype "passive"))
      (node (ref "J13") (pin "88") (pinfunction "B28_88") (pintype "passive"))
      (node (ref "J14") (pin "88") (pinfunction "B28_88") (pintype "passive"))
      (node (ref "J15") (pin "88") (pinfunction "B28_88") (pintype "passive"))
      (node (ref "J16") (pin "88") (pinfunction "B28_88") (pintype "passive"))
      (node (ref "J2") (pin "88") (pinfunction "B28_88") (pintype "passive"))
      (node (ref "J3") (pin "88") (pinfunction "B28_88") (pintype "passive"))
      (node (ref "J4") (pin "88") (pinfunction "B28_88") (pintype "passive"))
      (node (ref "J5") (pin "88") (pinfunction "B28_88") (pintype "passive"))
      (node (ref "J6") (pin "88") (pinfunction "B28_88") (pintype "passive"))
      (node (ref "J7") (pin "88") (pinfunction "B28_88") (pintype "passive"))
      (node (ref "J8") (pin "88") (pinfunction "B28_88") (pintype "passive"))
      (node (ref "J9") (pin "88") (pinfunction "B28_88") (pintype "passive"))
      (node (ref "R30") (pin "2") (pinfunction "2_2") (pintype "passive"))
      (node (ref "U3") (pin "13") (pinfunction "DO4-_13") (pintype "passive"))
    )
    (net (code "157") (name "/bus30") (class "Default")
      (node (ref "P7") (pin "34") (pinfunction "34_34") (pintype "passive"))
      (node (ref "U11") (pin "1B7") (pinfunction "M4/L18p_1B7") (pintype "passive"))
      (node (ref "U3") (pin "1") (pinfunction "DI1_1") (pintype "passive"))
    )
    (net (code "158") (name "/bus30_n") (class "Default")
      (node (ref "J1") (pin "82") (pinfunction "B22_82") (pintype "passive"))
      (node (ref "J10") (pin "82") (pinfunction "B22_82") (pintype "passive"))
      (node (ref "J11") (pin "82") (pinfunction "B22_82") (pintype "passive"))
      (node (ref "J12") (pin "82") (pinfunction "B22_82") (pintype "passive"))
      (node (ref "J13") (pin "82") (pinfunction "B22_82") (pintype "passive"))
      (node (ref "J14") (pin "82") (pinfunction "B22_82") (pintype "passive"))
      (node (ref "J15") (pin "82") (pinfunction "B22_82") (pintype "passive"))
      (node (ref "J16") (pin "82") (pinfunction "B22_82") (pintype "passive"))
      (node (ref "J2") (pin "82") (pinfunction "B22_82") (pintype "passive"))
      (node (ref "J3") (pin "82") (pinfunction "B22_82") (pintype "passive"))
      (node (ref "J4") (pin "82") (pinfunction "B22_82") (pintype "passive"))
      (node (ref "J5") (pin "82") (pinfunction "B22_82") (pintype "passive"))
      (node (ref "J6") (pin "82") (pinfunction "B22_82") (pintype "passive"))
      (node (ref "J7") (pin "82") (pinfunction "B22_82") (pintype "passive"))
      (node (ref "J8") (pin "82") (pinfunction "B22_82") (pintype "passive"))
      (node (ref "J9") (pin "82") (pinfunction "B22_82") (pintype "passive"))
      (node (ref "R31") (pin "1") (pinfunction "1_1") (pintype "passive"))
      (node (ref "U3") (pin "2") (pinfunction "DO1+_2") (pintype "passive"))
    )
    (net (code "159") (name "/bus30_p") (class "Default")
      (node (ref "J1") (pin "83") (pinfunction "B23_83") (pintype "passive"))
      (node (ref "J10") (pin "83") (pinfunction "B23_83") (pintype "passive"))
      (node (ref "J11") (pin "83") (pinfunction "B23_83") (pintype "passive"))
      (node (ref "J12") (pin "83") (pinfunction "B23_83") (pintype "passive"))
      (node (ref "J13") (pin "83") (pinfunction "B23_83") (pintype "passive"))
      (node (ref "J14") (pin "83") (pinfunction "B23_83") (pintype "passive"))
      (node (ref "J15") (pin "83") (pinfunction "B23_83") (pintype "passive"))
      (node (ref "J16") (pin "83") (pinfunction "B23_83") (pintype "passive"))
      (node (ref "J2") (pin "83") (pinfunction "B23_83") (pintype "passive"))
      (node (ref "J3") (pin "83") (pinfunction "B23_83") (pintype "passive"))
      (node (ref "J4") (pin "83") (pinfunction "B23_83") (pintype "passive"))
      (node (ref "J5") (pin "83") (pinfunction "B23_83") (pintype "passive"))
      (node (ref "J6") (pin "83") (pinfunction "B23_83") (pintype "passive"))
      (node (ref "J7") (pin "83") (pinfunction "B23_83") (pintype "passive"))
      (node (ref "J8") (pin "83") (pinfunction "B23_83") (pintype "passive"))
      (node (ref "J9") (pin "83") (pinfunction "B23_83") (pintype "passive"))
      (node (ref "R31") (pin "2") (pinfunction "2_2") (pintype "passive"))
      (node (ref "U3") (pin "3") (pinfunction "DO1-_3") (pintype "passive"))
    )
    (net (code "160") (name "/bus31") (class "Default")
      (node (ref "P7") (pin "33") (pinfunction "33_33") (pintype "passive"))
      (node (ref "U11") (pin "1B6") (pinfunction "U8/B2n_1B6") (pintype "passive"))
      (node (ref "U3") (pin "7") (pinfunction "DI2_7") (pintype "passive"))
    )
    (net (code "161") (name "/bus31_n") (class "Default")
      (node (ref "J1") (pin "85") (pinfunction "B25_85") (pintype "passive"))
      (node (ref "J10") (pin "85") (pinfunction "B25_85") (pintype "passive"))
      (node (ref "J11") (pin "85") (pinfunction "B25_85") (pintype "passive"))
      (node (ref "J12") (pin "85") (pinfunction "B25_85") (pintype "passive"))
      (node (ref "J13") (pin "85") (pinfunction "B25_85") (pintype "passive"))
      (node (ref "J14") (pin "85") (pinfunction "B25_85") (pintype "passive"))
      (node (ref "J15") (pin "85") (pinfunction "B25_85") (pintype "passive"))
      (node (ref "J16") (pin "85") (pinfunction "B25_85") (pintype "passive"))
      (node (ref "J2") (pin "85") (pinfunction "B25_85") (pintype "passive"))
      (node (ref "J3") (pin "85") (pinfunction "B25_85") (pintype "passive"))
      (node (ref "J4") (pin "85") (pinfunction "B25_85") (pintype "passive"))
      (node (ref "J5") (pin "85") (pinfunction "B25_85") (pintype "passive"))
      (node (ref "J6") (pin "85") (pinfunction "B25_85") (pintype "passive"))
      (node (ref "J7") (pin "85") (pinfunction "B25_85") (pintype "passive"))
      (node (ref "J8") (pin "85") (pinfunction "B25_85") (pintype "passive"))
      (node (ref "J9") (pin "85") (pinfunction "B25_85") (pintype "passive"))
      (node (ref "R32") (pin "1") (pinfunction "1_1") (pintype "passive"))
      (node (ref "U3") (pin "6") (pinfunction "DO2+_6") (pintype "passive"))
    )
    (net (code "162") (name "/bus31_p") (class "Default")
      (node (ref "J1") (pin "84") (pinfunction "B24_84") (pintype "passive"))
      (node (ref "J10") (pin "84") (pinfunction "B24_84") (pintype "passive"))
      (node (ref "J11") (pin "84") (pinfunction "B24_84") (pintype "passive"))
      (node (ref "J12") (pin "84") (pinfunction "B24_84") (pintype "passive"))
      (node (ref "J13") (pin "84") (pinfunction "B24_84") (pintype "passive"))
      (node (ref "J14") (pin "84") (pinfunction "B24_84") (pintype "passive"))
      (node (ref "J15") (pin "84") (pinfunction "B24_84") (pintype "passive"))
      (node (ref "J16") (pin "84") (pinfunction "B24_84") (pintype "passive"))
      (node (ref "J2") (pin "84") (pinfunction "B24_84") (pintype "passive"))
      (node (ref "J3") (pin "84") (pinfunction "B24_84") (pintype "passive"))
      (node (ref "J4") (pin "84") (pinfunction "B24_84") (pintype "passive"))
      (node (ref "J5") (pin "84") (pinfunction "B24_84") (pintype "passive"))
      (node (ref "J6") (pin "84") (pinfunction "B24_84") (pintype "passive"))
      (node (ref "J7") (pin "84") (pinfunction "B24_84") (pintype "passive"))
      (node (ref "J8") (pin "84") (pinfunction "B24_84") (pintype "passive"))
      (node (ref "J9") (pin "84") (pinfunction "B24_84") (pintype "passive"))
      (node (ref "R32") (pin "2") (pinfunction "2_2") (pintype "passive"))
      (node (ref "U3") (pin "5") (pinfunction "DO2-_5") (pintype "passive"))
    )
    (net (code "163") (name "/bus32") (class "Default")
      (node (ref "P9") (pin "6") (pinfunction "6_6") (pintype "passive"))
      (node (ref "U11") (pin "1B13") (pinfunction "N1/L19n_1B13") (pintype "passive"))
      (node (ref "U2") (pin "11") (pinfunction "YD_11") (pintype "passive"))
    )
    (net (code "164") (name "/bus32_n") (class "Default")
      (node (ref "J1") (pin "15") (pinfunction "A15_15") (pintype "passive"))
      (node (ref "J10") (pin "15") (pinfunction "A15_15") (pintype "passive"))
      (node (ref "J11") (pin "15") (pinfunction "A15_15") (pintype "passive"))
      (node (ref "J12") (pin "15") (pinfunction "A15_15") (pintype "passive"))
      (node (ref "J13") (pin "15") (pinfunction "A15_15") (pintype "passive"))
      (node (ref "J14") (pin "15") (pinfunction "A15_15") (pintype "passive"))
      (node (ref "J15") (pin "15") (pinfunction "A15_15") (pintype "passive"))
      (node (ref "J16") (pin "15") (pinfunction "A15_15") (pintype "passive"))
      (node (ref "J2") (pin "15") (pinfunction "A15_15") (pintype "passive"))
      (node (ref "J3") (pin "15") (pinfunction "A15_15") (pintype "passive"))
      (node (ref "J4") (pin "15") (pinfunction "A15_15") (pintype "passive"))
      (node (ref "J5") (pin "15") (pinfunction "A15_15") (pintype "passive"))
      (node (ref "J6") (pin "15") (pinfunction "A15_15") (pintype "passive"))
      (node (ref "J7") (pin "15") (pinfunction "A15_15") (pintype "passive"))
      (node (ref "J8") (pin "15") (pinfunction "A15_15") (pintype "passive"))
      (node (ref "J9") (pin "15") (pinfunction "A15_15") (pintype "passive"))
      (node (ref "R33") (pin "1") (pinfunction "1_1") (pintype "passive"))
      (node (ref "U2") (pin "10") (pinfunction "D+_10") (pintype "passive"))
    )
    (net (code "165") (name "/bus32_p") (class "Default")
      (node (ref "J1") (pin "16") (pinfunction "A16_16") (pintype "passive"))
      (node (ref "J10") (pin "16") (pinfunction "A16_16") (pintype "passive"))
      (node (ref "J11") (pin "16") (pinfunction "A16_16") (pintype "passive"))
      (node (ref "J12") (pin "16") (pinfunction "A16_16") (pintype "passive"))
      (node (ref "J13") (pin "16") (pinfunction "A16_16") (pintype "passive"))
      (node (ref "J14") (pin "16") (pinfunction "A16_16") (pintype "passive"))
      (node (ref "J15") (pin "16") (pinfunction "A16_16") (pintype "passive"))
      (node (ref "J16") (pin "16") (pinfunction "A16_16") (pintype "passive"))
      (node (ref "J2") (pin "16") (pinfunction "A16_16") (pintype "passive"))
      (node (ref "J3") (pin "16") (pinfunction "A16_16") (pintype "passive"))
      (node (ref "J4") (pin "16") (pinfunction "A16_16") (pintype "passive"))
      (node (ref "J5") (pin "16") (pinfunction "A16_16") (pintype "passive"))
      (node (ref "J6") (pin "16") (pinfunction "A16_16") (pintype "passive"))
      (node (ref "J7") (pin "16") (pinfunction "A16_16") (pintype "passive"))
      (node (ref "J8") (pin "16") (pinfunction "A16_16") (pintype "passive"))
      (node (ref "J9") (pin "16") (pinfunction "A16_16") (pintype "passive"))
      (node (ref "R33") (pin "2") (pinfunction "2_2") (pintype "passive"))
      (node (ref "U2") (pin "9") (pinfunction "D-_9") (pintype "passive"))
    )
    (net (code "166") (name "/bus33") (class "Default")
      (node (ref "P9") (pin "5") (pinfunction "5_5") (pintype "passive"))
      (node (ref "U11") (pin "1B12") (pinfunction "AA5/B5p_1B12") (pintype "passive"))
      (node (ref "U2") (pin "13") (pinfunction "YB_13") (pintype "passive"))
    )
    (net (code "167") (name "/bus33_n") (class "Default")
      (node (ref "J1") (pin "14") (pinfunction "A14_14") (pintype "passive"))
      (node (ref "J10") (pin "14") (pinfunction "A14_14") (pintype "passive"))
      (node (ref "J11") (pin "14") (pinfunction "A14_14") (pintype "passive"))
      (node (ref "J12") (pin "14") (pinfunction "A14_14") (pintype "passive"))
      (node (ref "J13") (pin "14") (pinfunction "A14_14") (pintype "passive"))
      (node (ref "J14") (pin "14") (pinfunction "A14_14") (pintype "passive"))
      (node (ref "J15") (pin "14") (pinfunction "A14_14") (pintype "passive"))
      (node (ref "J16") (pin "14") (pinfunction "A14_14") (pintype "passive"))
      (node (ref "J2") (pin "14") (pinfunction "A14_14") (pintype "passive"))
      (node (ref "J3") (pin "14") (pinfunction "A14_14") (pintype "passive"))
      (node (ref "J4") (pin "14") (pinfunction "A14_14") (pintype "passive"))
      (node (ref "J5") (pin "14") (pinfunction "A14_14") (pintype "passive"))
      (node (ref "J6") (pin "14") (pinfunction "A14_14") (pintype "passive"))
      (node (ref "J7") (pin "14") (pinfunction "A14_14") (pintype "passive"))
      (node (ref "J8") (pin "14") (pinfunction "A14_14") (pintype "passive"))
      (node (ref "J9") (pin "14") (pinfunction "A14_14") (pintype "passive"))
      (node (ref "R34") (pin "1") (pinfunction "1_1") (pintype "passive"))
      (node (ref "U2") (pin "14") (pinfunction "B+_14") (pintype "passive"))
    )
    (net (code "168") (name "/bus33_p") (class "Default")
      (node (ref "J1") (pin "13") (pinfunction "A13_13") (pintype "passive"))
      (node (ref "J10") (pin "13") (pinfunction "A13_13") (pintype "passive"))
      (node (ref "J11") (pin "13") (pinfunction "A13_13") (pintype "passive"))
      (node (ref "J12") (pin "13") (pinfunction "A13_13") (pintype "passive"))
      (node (ref "J13") (pin "13") (pinfunction "A13_13") (pintype "passive"))
      (node (ref "J14") (pin "13") (pinfunction "A13_13") (pintype "passive"))
      (node (ref "J15") (pin "13") (pinfunction "A13_13") (pintype "passive"))
      (node (ref "J16") (pin "13") (pinfunction "A13_13") (pintype "passive"))
      (node (ref "J2") (pin "13") (pinfunction "A13_13") (pintype "passive"))
      (node (ref "J3") (pin "13") (pinfunction "A13_13") (pintype "passive"))
      (node (ref "J4") (pin "13") (pinfunction "A13_13") (pintype "passive"))
      (node (ref "J5") (pin "13") (pinfunction "A13_13") (pintype "passive"))
      (node (ref "J6") (pin "13") (pinfunction "A13_13") (pintype "passive"))
      (node (ref "J7") (pin "13") (pinfunction "A13_13") (pintype "passive"))
      (node (ref "J8") (pin "13") (pinfunction "A13_13") (pintype "passive"))
      (node (ref "J9") (pin "13") (pinfunction "A13_13") (pintype "passive"))
      (node (ref "R34") (pin "2") (pinfunction "2_2") (pintype "passive"))
      (node (ref "U2") (pin "15") (pinfunction "B-_15") (pintype "passive"))
    )
    (net (code "169") (name "/bus34") (class "Default")
      (node (ref "P9") (pin "8") (pinfunction "8_8") (pintype "passive"))
      (node (ref "U11") (pin "1B15") (pinfunction "P2/L20p_1B15") (pintype "passive"))
      (node (ref "U2") (pin "3") (pinfunction "YA_3") (pintype "passive"))
    )
    (net (code "170") (name "/bus34_n") (class "Default")
      (node (ref "J1") (pin "19") (pinfunction "A19_19") (pintype "passive"))
      (node (ref "J10") (pin "19") (pinfunction "A19_19") (pintype "passive"))
      (node (ref "J11") (pin "19") (pinfunction "A19_19") (pintype "passive"))
      (node (ref "J12") (pin "19") (pinfunction "A19_19") (pintype "passive"))
      (node (ref "J13") (pin "19") (pinfunction "A19_19") (pintype "passive"))
      (node (ref "J14") (pin "19") (pinfunction "A19_19") (pintype "passive"))
      (node (ref "J15") (pin "19") (pinfunction "A19_19") (pintype "passive"))
      (node (ref "J16") (pin "19") (pinfunction "A19_19") (pintype "passive"))
      (node (ref "J2") (pin "19") (pinfunction "A19_19") (pintype "passive"))
      (node (ref "J3") (pin "19") (pinfunction "A19_19") (pintype "passive"))
      (node (ref "J4") (pin "19") (pinfunction "A19_19") (pintype "passive"))
      (node (ref "J5") (pin "19") (pinfunction "A19_19") (pintype "passive"))
      (node (ref "J6") (pin "19") (pinfunction "A19_19") (pintype "passive"))
      (node (ref "J7") (pin "19") (pinfunction "A19_19") (pintype "passive"))
      (node (ref "J8") (pin "19") (pinfunction "A19_19") (pintype "passive"))
      (node (ref "J9") (pin "19") (pinfunction "A19_19") (pintype "passive"))
      (node (ref "R35") (pin "1") (pinfunction "1_1") (pintype "passive"))
      (node (ref "U2") (pin "2") (pinfunction "A+_2") (pintype "passive"))
    )
    (net (code "171") (name "/bus34_p") (class "Default")
      (node (ref "J1") (pin "20") (pinfunction "A20_20") (pintype "passive"))
      (node (ref "J10") (pin "20") (pinfunction "A20_20") (pintype "passive"))
      (node (ref "J11") (pin "20") (pinfunction "A20_20") (pintype "passive"))
      (node (ref "J12") (pin "20") (pinfunction "A20_20") (pintype "passive"))
      (node (ref "J13") (pin "20") (pinfunction "A20_20") (pintype "passive"))
      (node (ref "J14") (pin "20") (pinfunction "A20_20") (pintype "passive"))
      (node (ref "J15") (pin "20") (pinfunction "A20_20") (pintype "passive"))
      (node (ref "J16") (pin "20") (pinfunction "A20_20") (pintype "passive"))
      (node (ref "J2") (pin "20") (pinfunction "A20_20") (pintype "passive"))
      (node (ref "J3") (pin "20") (pinfunction "A20_20") (pintype "passive"))
      (node (ref "J4") (pin "20") (pinfunction "A20_20") (pintype "passive"))
      (node (ref "J5") (pin "20") (pinfunction "A20_20") (pintype "passive"))
      (node (ref "J6") (pin "20") (pinfunction "A20_20") (pintype "passive"))
      (node (ref "J7") (pin "20") (pinfunction "A20_20") (pintype "passive"))
      (node (ref "J8") (pin "20") (pinfunction "A20_20") (pintype "passive"))
      (node (ref "J9") (pin "20") (pinfunction "A20_20") (pintype "passive"))
      (node (ref "R35") (pin "2") (pinfunction "2_2") (pintype "passive"))
      (node (ref "U2") (pin "1") (pinfunction "A-_1") (pintype "passive"))
    )
    (net (code "172") (name "/bus35") (class "Default")
      (node (ref "P9") (pin "7") (pinfunction "7_7") (pintype "passive"))
      (node (ref "U11") (pin "1B14") (pinfunction "AA6/B5n_1B14") (pintype "passive"))
      (node (ref "U2") (pin "5") (pinfunction "YC_5") (pintype "passive"))
    )
    (net (code "173") (name "/bus35_n") (class "Default")
      (node (ref "J1") (pin "18") (pinfunction "A18_18") (pintype "passive"))
      (node (ref "J10") (pin "18") (pinfunction "A18_18") (pintype "passive"))
      (node (ref "J11") (pin "18") (pinfunction "A18_18") (pintype "passive"))
      (node (ref "J12") (pin "18") (pinfunction "A18_18") (pintype "passive"))
      (node (ref "J13") (pin "18") (pinfunction "A18_18") (pintype "passive"))
      (node (ref "J14") (pin "18") (pinfunction "A18_18") (pintype "passive"))
      (node (ref "J15") (pin "18") (pinfunction "A18_18") (pintype "passive"))
      (node (ref "J16") (pin "18") (pinfunction "A18_18") (pintype "passive"))
      (node (ref "J2") (pin "18") (pinfunction "A18_18") (pintype "passive"))
      (node (ref "J3") (pin "18") (pinfunction "A18_18") (pintype "passive"))
      (node (ref "J4") (pin "18") (pinfunction "A18_18") (pintype "passive"))
      (node (ref "J5") (pin "18") (pinfunction "A18_18") (pintype "passive"))
      (node (ref "J6") (pin "18") (pinfunction "A18_18") (pintype "passive"))
      (node (ref "J7") (pin "18") (pinfunction "A18_18") (pintype "passive"))
      (node (ref "J8") (pin "18") (pinfunction "A18_18") (pintype "passive"))
      (node (ref "J9") (pin "18") (pinfunction "A18_18") (pintype "passive"))
      (node (ref "R36") (pin "1") (pinfunction "1_1") (pintype "passive"))
      (node (ref "U2") (pin "6") (pinfunction "C+_6") (pintype "passive"))
    )
    (net (code "174") (name "/bus35_p") (class "Default")
      (node (ref "J1") (pin "17") (pinfunction "A17_17") (pintype "passive"))
      (node (ref "J10") (pin "17") (pinfunction "A17_17") (pintype "passive"))
      (node (ref "J11") (pin "17") (pinfunction "A17_17") (pintype "passive"))
      (node (ref "J12") (pin "17") (pinfunction "A17_17") (pintype "passive"))
      (node (ref "J13") (pin "17") (pinfunction "A17_17") (pintype "passive"))
      (node (ref "J14") (pin "17") (pinfunction "A17_17") (pintype "passive"))
      (node (ref "J15") (pin "17") (pinfunction "A17_17") (pintype "passive"))
      (node (ref "J16") (pin "17") (pinfunction "A17_17") (pintype "passive"))
      (node (ref "J2") (pin "17") (pinfunction "A17_17") (pintype "passive"))
      (node (ref "J3") (pin "17") (pinfunction "A17_17") (pintype "passive"))
      (node (ref "J4") (pin "17") (pinfunction "A17_17") (pintype "passive"))
      (node (ref "J5") (pin "17") (pinfunction "A17_17") (pintype "passive"))
      (node (ref "J6") (pin "17") (pinfunction "A17_17") (pintype "passive"))
      (node (ref "J7") (pin "17") (pinfunction "A17_17") (pintype "passive"))
      (node (ref "J8") (pin "17") (pinfunction "A17_17") (pintype "passive"))
      (node (ref "J9") (pin "17") (pinfunction "A17_17") (pintype "passive"))
      (node (ref "R36") (pin "2") (pinfunction "2_2") (pintype "passive"))
      (node (ref "U2") (pin "7") (pinfunction "C-_7") (pintype "passive"))
    )
    (net (code "175") (name "/bus36") (class "Default")
      (node (ref "P9") (pin "2") (pinfunction "2_2") (pintype "passive"))
      (node (ref "U1") (pin "11") (pinfunction "YD_11") (pintype "passive"))
      (node (ref "U11") (pin "1B9") (pinfunction "M3/L18n_1B9") (pintype "passive"))
    )
    (net (code "176") (name "/bus36_n") (class "Default")
      (node (ref "J1") (pin "78") (pinfunction "B18_78") (pintype "passive"))
      (node (ref "J10") (pin "78") (pinfunction "B18_78") (pintype "passive"))
      (node (ref "J11") (pin "78") (pinfunction "B18_78") (pintype "passive"))
      (node (ref "J12") (pin "78") (pinfunction "B18_78") (pintype "passive"))
      (node (ref "J13") (pin "78") (pinfunction "B18_78") (pintype "passive"))
      (node (ref "J14") (pin "78") (pinfunction "B18_78") (pintype "passive"))
      (node (ref "J15") (pin "78") (pinfunction "B18_78") (pintype "passive"))
      (node (ref "J16") (pin "78") (pinfunction "B18_78") (pintype "passive"))
      (node (ref "J2") (pin "78") (pinfunction "B18_78") (pintype "passive"))
      (node (ref "J3") (pin "78") (pinfunction "B18_78") (pintype "passive"))
      (node (ref "J4") (pin "78") (pinfunction "B18_78") (pintype "passive"))
      (node (ref "J5") (pin "78") (pinfunction "B18_78") (pintype "passive"))
      (node (ref "J6") (pin "78") (pinfunction "B18_78") (pintype "passive"))
      (node (ref "J7") (pin "78") (pinfunction "B18_78") (pintype "passive"))
      (node (ref "J8") (pin "78") (pinfunction "B18_78") (pintype "passive"))
      (node (ref "J9") (pin "78") (pinfunction "B18_78") (pintype "passive"))
      (node (ref "R37") (pin "1") (pinfunction "1_1") (pintype "passive"))
      (node (ref "U1") (pin "10") (pinfunction "D+_10") (pintype "passive"))
    )
    (net (code "177") (name "/bus36_p") (class "Default")
      (node (ref "J1") (pin "77") (pinfunction "B17_77") (pintype "passive"))
      (node (ref "J10") (pin "77") (pinfunction "B17_77") (pintype "passive"))
      (node (ref "J11") (pin "77") (pinfunction "B17_77") (pintype "passive"))
      (node (ref "J12") (pin "77") (pinfunction "B17_77") (pintype "passive"))
      (node (ref "J13") (pin "77") (pinfunction "B17_77") (pintype "passive"))
      (node (ref "J14") (pin "77") (pinfunction "B17_77") (pintype "passive"))
      (node (ref "J15") (pin "77") (pinfunction "B17_77") (pintype "passive"))
      (node (ref "J16") (pin "77") (pinfunction "B17_77") (pintype "passive"))
      (node (ref "J2") (pin "77") (pinfunction "B17_77") (pintype "passive"))
      (node (ref "J3") (pin "77") (pinfunction "B17_77") (pintype "passive"))
      (node (ref "J4") (pin "77") (pinfunction "B17_77") (pintype "passive"))
      (node (ref "J5") (pin "77") (pinfunction "B17_77") (pintype "passive"))
      (node (ref "J6") (pin "77") (pinfunction "B17_77") (pintype "passive"))
      (node (ref "J7") (pin "77") (pinfunction "B17_77") (pintype "passive"))
      (node (ref "J8") (pin "77") (pinfunction "B17_77") (pintype "passive"))
      (node (ref "J9") (pin "77") (pinfunction "B17_77") (pintype "passive"))
      (node (ref "R37") (pin "2") (pinfunction "2_2") (pintype "passive"))
      (node (ref "U1") (pin "9") (pinfunction "D-_9") (pintype "passive"))
    )
    (net (code "178") (name "/bus37") (class "Default")
      (node (ref "P9") (pin "1") (pinfunction "1_1") (pintype "passive"))
      (node (ref "U1") (pin "13") (pinfunction "YB_13") (pintype "passive"))
      (node (ref "U11") (pin "1B8") (pinfunction "W6/B4p_1B8") (pintype "passive"))
    )
    (net (code "179") (name "/bus37_n") (class "Default")
      (node (ref "J1") (pin "79") (pinfunction "B19_79") (pintype "passive"))
      (node (ref "J10") (pin "79") (pinfunction "B19_79") (pintype "passive"))
      (node (ref "J11") (pin "79") (pinfunction "B19_79") (pintype "passive"))
      (node (ref "J12") (pin "79") (pinfunction "B19_79") (pintype "passive"))
      (node (ref "J13") (pin "79") (pinfunction "B19_79") (pintype "passive"))
      (node (ref "J14") (pin "79") (pinfunction "B19_79") (pintype "passive"))
      (node (ref "J15") (pin "79") (pinfunction "B19_79") (pintype "passive"))
      (node (ref "J16") (pin "79") (pinfunction "B19_79") (pintype "passive"))
      (node (ref "J2") (pin "79") (pinfunction "B19_79") (pintype "passive"))
      (node (ref "J3") (pin "79") (pinfunction "B19_79") (pintype "passive"))
      (node (ref "J4") (pin "79") (pinfunction "B19_79") (pintype "passive"))
      (node (ref "J5") (pin "79") (pinfunction "B19_79") (pintype "passive"))
      (node (ref "J6") (pin "79") (pinfunction "B19_79") (pintype "passive"))
      (node (ref "J7") (pin "79") (pinfunction "B19_79") (pintype "passive"))
      (node (ref "J8") (pin "79") (pinfunction "B19_79") (pintype "passive"))
      (node (ref "J9") (pin "79") (pinfunction "B19_79") (pintype "passive"))
      (node (ref "R38") (pin "1") (pinfunction "1_1") (pintype "passive"))
      (node (ref "U1") (pin "14") (pinfunction "B+_14") (pintype "passive"))
    )
    (net (code "180") (name "/bus37_p") (class "Default")
      (node (ref "J1") (pin "80") (pinfunction "B20_80") (pintype "passive"))
      (node (ref "J10") (pin "80") (pinfunction "B20_80") (pintype "passive"))
      (node (ref "J11") (pin "80") (pinfunction "B20_80") (pintype "passive"))
      (node (ref "J12") (pin "80") (pinfunction "B20_80") (pintype "passive"))
      (node (ref "J13") (pin "80") (pinfunction "B20_80") (pintype "passive"))
      (node (ref "J14") (pin "80") (pinfunction "B20_80") (pintype "passive"))
      (node (ref "J15") (pin "80") (pinfunction "B20_80") (pintype "passive"))
      (node (ref "J16") (pin "80") (pinfunction "B20_80") (pintype "passive"))
      (node (ref "J2") (pin "80") (pinfunction "B20_80") (pintype "passive"))
      (node (ref "J3") (pin "80") (pinfunction "B20_80") (pintype "passive"))
      (node (ref "J4") (pin "80") (pinfunction "B20_80") (pintype "passive"))
      (node (ref "J5") (pin "80") (pinfunction "B20_80") (pintype "passive"))
      (node (ref "J6") (pin "80") (pinfunction "B20_80") (pintype "passive"))
      (node (ref "J7") (pin "80") (pinfunction "B20_80") (pintype "passive"))
      (node (ref "J8") (pin "80") (pinfunction "B20_80") (pintype "passive"))
      (node (ref "J9") (pin "80") (pinfunction "B20_80") (pintype "passive"))
      (node (ref "R38") (pin "2") (pinfunction "2_2") (pintype "passive"))
      (node (ref "U1") (pin "15") (pinfunction "B-_15") (pintype "passive"))
    )
    (net (code "181") (name "/bus38") (class "Default")
      (node (ref "P9") (pin "4") (pinfunction "4_4") (pintype "passive"))
      (node (ref "U1") (pin "3") (pinfunction "YA_3") (pintype "passive"))
      (node (ref "U11") (pin "1B11") (pinfunction "N2/L19p_1B11") (pintype "passive"))
    )
    (net (code "182") (name "/bus38_n") (class "Default")
      (node (ref "J1") (pin "74") (pinfunction "B14_74") (pintype "passive"))
      (node (ref "J10") (pin "74") (pinfunction "B14_74") (pintype "passive"))
      (node (ref "J11") (pin "74") (pinfunction "B14_74") (pintype "passive"))
      (node (ref "J12") (pin "74") (pinfunction "B14_74") (pintype "passive"))
      (node (ref "J13") (pin "74") (pinfunction "B14_74") (pintype "passive"))
      (node (ref "J14") (pin "74") (pinfunction "B14_74") (pintype "passive"))
      (node (ref "J15") (pin "74") (pinfunction "B14_74") (pintype "passive"))
      (node (ref "J16") (pin "74") (pinfunction "B14_74") (pintype "passive"))
      (node (ref "J2") (pin "74") (pinfunction "B14_74") (pintype "passive"))
      (node (ref "J3") (pin "74") (pinfunction "B14_74") (pintype "passive"))
      (node (ref "J4") (pin "74") (pinfunction "B14_74") (pintype "passive"))
      (node (ref "J5") (pin "74") (pinfunction "B14_74") (pintype "passive"))
      (node (ref "J6") (pin "74") (pinfunction "B14_74") (pintype "passive"))
      (node (ref "J7") (pin "74") (pinfunction "B14_74") (pintype "passive"))
      (node (ref "J8") (pin "74") (pinfunction "B14_74") (pintype "passive"))
      (node (ref "J9") (pin "74") (pinfunction "B14_74") (pintype "passive"))
      (node (ref "R39") (pin "1") (pinfunction "1_1") (pintype "passive"))
      (node (ref "U1") (pin "2") (pinfunction "A+_2") (pintype "passive"))
    )
    (net (code "183") (name "/bus38_p") (class "Default")
      (node (ref "J1") (pin "73") (pinfunction "B13_73") (pintype "passive"))
      (node (ref "J10") (pin "73") (pinfunction "B13_73") (pintype "passive"))
      (node (ref "J11") (pin "73") (pinfunction "B13_73") (pintype "passive"))
      (node (ref "J12") (pin "73") (pinfunction "B13_73") (pintype "passive"))
      (node (ref "J13") (pin "73") (pinfunction "B13_73") (pintype "passive"))
      (node (ref "J14") (pin "73") (pinfunction "B13_73") (pintype "passive"))
      (node (ref "J15") (pin "73") (pinfunction "B13_73") (pintype "passive"))
      (node (ref "J16") (pin "73") (pinfunction "B13_73") (pintype "passive"))
      (node (ref "J2") (pin "73") (pinfunction "B13_73") (pintype "passive"))
      (node (ref "J3") (pin "73") (pinfunction "B13_73") (pintype "passive"))
      (node (ref "J4") (pin "73") (pinfunction "B13_73") (pintype "passive"))
      (node (ref "J5") (pin "73") (pinfunction "B13_73") (pintype "passive"))
      (node (ref "J6") (pin "73") (pinfunction "B13_73") (pintype "passive"))
      (node (ref "J7") (pin "73") (pinfunction "B13_73") (pintype "passive"))
      (node (ref "J8") (pin "73") (pinfunction "B13_73") (pintype "passive"))
      (node (ref "J9") (pin "73") (pinfunction "B13_73") (pintype "passive"))
      (node (ref "R39") (pin "2") (pinfunction "2_2") (pintype "passive"))
      (node (ref "U1") (pin "1") (pinfunction "A-_1") (pintype "passive"))
    )
    (net (code "184") (name "/bus39") (class "Default")
      (node (ref "P9") (pin "3") (pinfunction "3_3") (pintype "passive"))
      (node (ref "U1") (pin "5") (pinfunction "YC_5") (pintype "passive"))
      (node (ref "U11") (pin "1B10") (pinfunction "V7/B4n_1B10") (pintype "passive"))
    )
    (net (code "185") (name "/bus39_n") (class "Default")
      (node (ref "J1") (pin "75") (pinfunction "B15_75") (pintype "passive"))
      (node (ref "J10") (pin "75") (pinfunction "B15_75") (pintype "passive"))
      (node (ref "J11") (pin "75") (pinfunction "B15_75") (pintype "passive"))
      (node (ref "J12") (pin "75") (pinfunction "B15_75") (pintype "passive"))
      (node (ref "J13") (pin "75") (pinfunction "B15_75") (pintype "passive"))
      (node (ref "J14") (pin "75") (pinfunction "B15_75") (pintype "passive"))
      (node (ref "J15") (pin "75") (pinfunction "B15_75") (pintype "passive"))
      (node (ref "J16") (pin "75") (pinfunction "B15_75") (pintype "passive"))
      (node (ref "J2") (pin "75") (pinfunction "B15_75") (pintype "passive"))
      (node (ref "J3") (pin "75") (pinfunction "B15_75") (pintype "passive"))
      (node (ref "J4") (pin "75") (pinfunction "B15_75") (pintype "passive"))
      (node (ref "J5") (pin "75") (pinfunction "B15_75") (pintype "passive"))
      (node (ref "J6") (pin "75") (pinfunction "B15_75") (pintype "passive"))
      (node (ref "J7") (pin "75") (pinfunction "B15_75") (pintype "passive"))
      (node (ref "J8") (pin "75") (pinfunction "B15_75") (pintype "passive"))
      (node (ref "J9") (pin "75") (pinfunction "B15_75") (pintype "passive"))
      (node (ref "R40") (pin "1") (pinfunction "1_1") (pintype "passive"))
      (node (ref "U1") (pin "6") (pinfunction "C+_6") (pintype "passive"))
    )
    (net (code "186") (name "/bus39_p") (class "Default")
      (node (ref "J1") (pin "76") (pinfunction "B16_76") (pintype "passive"))
      (node (ref "J10") (pin "76") (pinfunction "B16_76") (pintype "passive"))
      (node (ref "J11") (pin "76") (pinfunction "B16_76") (pintype "passive"))
      (node (ref "J12") (pin "76") (pinfunction "B16_76") (pintype "passive"))
      (node (ref "J13") (pin "76") (pinfunction "B16_76") (pintype "passive"))
      (node (ref "J14") (pin "76") (pinfunction "B16_76") (pintype "passive"))
      (node (ref "J15") (pin "76") (pinfunction "B16_76") (pintype "passive"))
      (node (ref "J16") (pin "76") (pinfunction "B16_76") (pintype "passive"))
      (node (ref "J2") (pin "76") (pinfunction "B16_76") (pintype "passive"))
      (node (ref "J3") (pin "76") (pinfunction "B16_76") (pintype "passive"))
      (node (ref "J4") (pin "76") (pinfunction "B16_76") (pintype "passive"))
      (node (ref "J5") (pin "76") (pinfunction "B16_76") (pintype "passive"))
      (node (ref "J6") (pin "76") (pinfunction "B16_76") (pintype "passive"))
      (node (ref "J7") (pin "76") (pinfunction "B16_76") (pintype "passive"))
      (node (ref "J8") (pin "76") (pinfunction "B16_76") (pintype "passive"))
      (node (ref "J9") (pin "76") (pinfunction "B16_76") (pintype "passive"))
      (node (ref "R40") (pin "2") (pinfunction "2_2") (pintype "passive"))
      (node (ref "U1") (pin "7") (pinfunction "C-_7") (pintype "passive"))
    )
    (net (code "187") (name "3.3V_dig") (class "Default")
      (node (ref "C1") (pin "1") (pinfunction "1_1") (pintype "passive"))
      (node (ref "C2") (pin "1") (pinfunction "1_1") (pintype "passive"))
      (node (ref "C39") (pin "1") (pinfunction "1_1") (pintype "passive"))
      (node (ref "C40") (pin "1") (pinfunction "1_1") (pintype "passive"))
      (node (ref "C41") (pin "1") (pinfunction "1_1") (pintype "passive"))
      (node (ref "C42") (pin "1") (pinfunction "1_1") (pintype "passive"))
      (node (ref "C43") (pin "1") (pinfunction "1_1") (pintype "passive"))
      (node (ref "C44") (pin "1") (pinfunction "1_1") (pintype "passive"))
      (node (ref "C45") (pin "1") (pinfunction "1_1") (pintype "passive"))
      (node (ref "C46") (pin "1") (pinfunction "1_1") (pintype "passive"))
      (node (ref "C47") (pin "2") (pinfunction "2_2") (pintype "passive"))
      (node (ref "C48") (pin "2") (pinfunction "2_2") (pintype "passive"))
      (node (ref "C49") (pin "2") (pinfunction "2_2") (pintype "passive"))
      (node (ref "C50") (pin "2") (pinfunction "2_2") (pintype "passive"))
      (node (ref "P7") (pin "2") (pinfunction "2_2") (pintype "passive"))
      (node (ref "P7") (pin "4") (pinfunction "4_4") (pintype "passive"))
      (node (ref "P7") (pin "6") (pinfunction "6_6") (pintype "passive"))
      (node (ref "U1") (pin "12") (pinfunction "ENBD_12") (pintype "passive"))
      (node (ref "U1") (pin "16") (pinfunction "Vcc_16") (pintype "passive"))
      (node (ref "U1") (pin "4") (pinfunction "EAC_4") (pintype "passive"))
      (node (ref "U10") (pin "16") (pinfunction "Vcc_16") (pintype "passive"))
      (node (ref "U10") (pin "4") (pinfunction "EN_4") (pintype "passive"))
      (node (ref "U11") (pin "1A1") (pinfunction "3.3V_1A1") (pintype "passive"))
      (node (ref "U11") (pin "1C1") (pinfunction "3.3V_1C1") (pintype "passive"))
      (node (ref "U12") (pin "5") (pinfunction "DIR_5") (pintype "passive"))
      (node (ref "U12") (pin "6") (pinfunction "VCCB_6") (pintype "passive"))
      (node (ref "U13") (pin "5") (pinfunction "DIR_5") (pintype "passive"))
      (node (ref "U13") (pin "6") (pinfunction "VCCB_6") (pintype "passive"))
      (node (ref "U14") (pin "5") (pinfunction "DIR_5") (pintype "passive"))
      (node (ref "U14") (pin "6") (pinfunction "VCCB_6") (pintype "passive"))
      (node (ref "U15") (pin "5") (pinfunction "DIR_5") (pintype "passive"))
      (node (ref "U15") (pin "6") (pinfunction "VCCB_6") (pintype "passive"))
      (node (ref "U2") (pin "12") (pinfunction "ENBD_12") (pintype "passive"))
      (node (ref "U2") (pin "16") (pinfunction "Vcc_16") (pintype "passive"))
      (node (ref "U2") (pin "4") (pinfunction "EAC_4") (pintype "passive"))
      (node (ref "U3") (pin "16") (pinfunction "Vcc_16") (pintype "passive"))
      (node (ref "U3") (pin "4") (pinfunction "EN_4") (pintype "passive"))
      (node (ref "U4") (pin "16") (pinfunction "Vcc_16") (pintype "passive"))
      (node (ref "U4") (pin "4") (pinfunction "EN_4") (pintype "passive"))
      (node (ref "U5") (pin "16") (pinfunction "Vcc_16") (pintype "passive"))
      (node (ref "U5") (pin "4") (pinfunction "EN_4") (pintype "passive"))
      (node (ref "U6") (pin "16") (pinfunction "Vcc_16") (pintype "passive"))
      (node (ref "U6") (pin "4") (pinfunction "EN_4") (pintype "passive"))
      (node (ref "U7") (pin "16") (pinfunction "Vcc_16") (pintype "passive"))
      (node (ref "U7") (pin "4") (pinfunction "EN_4") (pintype "passive"))
      (node (ref "U8") (pin "16") (pinfunction "Vcc_16") (pintype "passive"))
      (node (ref "U8") (pin "4") (pinfunction "EN_4") (pintype "passive"))
      (node (ref "U9") (pin "16") (pinfunction "Vcc_16") (pintype "passive"))
      (node (ref "U9") (pin "4") (pinfunction "EN_4") (pintype "passive"))
    )
    (net (code "188") (name "5V_ANA_BUS") (class "Default")
      (node (ref "C16") (pin "1") (pinfunction "1_1") (pintype "passive"))
      (node (ref "C18") (pin "1") (pinfunction "1_1") (pintype "passive"))
      (node (ref "C20") (pin "1") (pinfunction "1_1") (pintype "passive"))
      (node (ref "C22") (pin "1") (pinfunction "1_1") (pintype "passive"))
      (node (ref "C25") (pin "2") (pinfunction "2_2") (pintype "passive"))
      (node (ref "C26") (pin "2") (pinfunction "2_2") (pintype "passive"))
      (node (ref "C29") (pin "2") (pinfunction "2_2") (pintype "passive"))
      (node (ref "C30") (pin "2") (pinfunction "2_2") (pintype "passive"))
      (node (ref "C33") (pin "2") (pinfunction "2_2") (pintype "passive"))
      (node (ref "C34") (pin "2") (pinfunction "2_2") (pintype "passive"))
      (node (ref "C37") (pin "2") (pinfunction "2_2") (pintype "passive"))
      (node (ref "C38") (pin "2") (pinfunction "2_2") (pintype "passive"))
      (node (ref "J1") (pin "118") (pinfunction "B58_118") (pintype "passive"))
      (node (ref "J1") (pin "58") (pinfunction "A58_58") (pintype "passive"))
      (node (ref "J10") (pin "118") (pinfunction "B58_118") (pintype "passive"))
      (node (ref "J10") (pin "58") (pinfunction "A58_58") (pintype "passive"))
      (node (ref "J11") (pin "118") (pinfunction "B58_118") (pintype "passive"))
      (node (ref "J11") (pin "58") (pinfunction "A58_58") (pintype "passive"))
      (node (ref "J12") (pin "118") (pinfunction "B58_118") (pintype "passive"))
      (node (ref "J12") (pin "58") (pinfunction "A58_58") (pintype "passive"))
      (node (ref "J13") (pin "118") (pinfunction "B58_118") (pintype "passive"))
      (node (ref "J13") (pin "58") (pinfunction "A58_58") (pintype "passive"))
      (node (ref "J14") (pin "118") (pinfunction "B58_118") (pintype "passive"))
      (node (ref "J14") (pin "58") (pinfunction "A58_58") (pintype "passive"))
      (node (ref "J15") (pin "118") (pinfunction "B58_118") (pintype "passive"))
      (node (ref "J15") (pin "58") (pinfunction "A58_58") (pintype "passive"))
      (node (ref "J16") (pin "118") (pinfunction "B58_118") (pintype "passive"))
      (node (ref "J16") (pin "58") (pinfunction "A58_58") (pintype "passive"))
      (node (ref "J2") (pin "118") (pinfunction "B58_118") (pintype "passive"))
      (node (ref "J2") (pin "58") (pinfunction "A58_58") (pintype "passive"))
      (node (ref "J3") (pin "118") (pinfunction "B58_118") (pintype "passive"))
      (node (ref "J3") (pin "58") (pinfunction "A58_58") (pintype "passive"))
      (node (ref "J4") (pin "118") (pinfunction "B58_118") (pintype "passive"))
      (node (ref "J4") (pin "58") (pinfunction "A58_58") (pintype "passive"))
      (node (ref "J5") (pin "118") (pinfunction "B58_118") (pintype "passive"))
      (node (ref "J5") (pin "58") (pinfunction "A58_58") (pintype "passive"))
      (node (ref "J6") (pin "118") (pinfunction "B58_118") (pintype "passive"))
      (node (ref "J6") (pin "58") (pinfunction "A58_58") (pintype "passive"))
      (node (ref "J7") (pin "118") (pinfunction "B58_118") (pintype "passive"))
      (node (ref "J7") (pin "58") (pinfunction "A58_58") (pintype "passive"))
      (node (ref "J8") (pin "118") (pinfunction "B58_118") (pintype "passive"))
      (node (ref "J8") (pin "58") (pinfunction "A58_58") (pintype "passive"))
      (node (ref "J9") (pin "118") (pinfunction "B58_118") (pintype "passive"))
      (node (ref "J9") (pin "58") (pinfunction "A58_58") (pintype "passive"))
    )
    (net (code "189") (name "5V_DIG_BUS") (class "Default")
      (node (ref "C10") (pin "2") (pinfunction "2_2") (pintype "passive"))
      (node (ref "C11") (pin "2") (pinfunction "2_2") (pintype "passive"))
      (node (ref "C12") (pin "2") (pinfunction "2_2") (pintype "passive"))
      (node (ref "C13") (pin "2") (pinfunction "2_2") (pintype "passive"))
      (node (ref "C14") (pin "2") (pinfunction "2_2") (pintype "passive"))
      (node (ref "C3") (pin "1") (pinfunction "1_1") (pintype "passive"))
      (node (ref "C4") (pin "1") (pinfunction "1_1") (pintype "passive"))
      (node (ref "C5") (pin "1") (pinfunction "1_1") (pintype "passive"))
      (node (ref "C6") (pin "1") (pinfunction "1_1") (pintype "passive"))
      (node (ref "C7") (pin "2") (pinfunction "2_2") (pintype "passive"))
      (node (ref "C8") (pin "2") (pinfunction "2_2") (pintype "passive"))
      (node (ref "C9") (pin "2") (pinfunction "2_2") (pintype "passive"))
      (node (ref "J1") (pin "1") (pinfunction "A1_1") (pintype "passive"))
      (node (ref "J1") (pin "61") (pinfunction "B1_61") (pintype "passive"))
      (node (ref "J10") (pin "1") (pinfunction "A1_1") (pintype "passive"))
      (node (ref "J10") (pin "61") (pinfunction "B1_61") (pintype "passive"))
      (node (ref "J11") (pin "1") (pinfunction "A1_1") (pintype "passive"))
      (node (ref "J11") (pin "61") (pinfunction "B1_61") (pintype "passive"))
      (node (ref "J12") (pin "1") (pinfunction "A1_1") (pintype "passive"))
      (node (ref "J12") (pin "61") (pinfunction "B1_61") (pintype "passive"))
      (node (ref "J13") (pin "1") (pinfunction "A1_1") (pintype "passive"))
      (node (ref "J13") (pin "61") (pinfunction "B1_61") (pintype "passive"))
      (node (ref "J14") (pin "1") (pinfunction "A1_1") (pintype "passive"))
      (node (ref "J14") (pin "61") (pinfunction "B1_61") (pintype "passive"))
      (node (ref "J15") (pin "1") (pinfunction "A1_1") (pintype "passive"))
      (node (ref "J15") (pin "61") (pinfunction "B1_61") (pintype "passive"))
      (node (ref "J16") (pin "1") (pinfunction "A1_1") (pintype "passive"))
      (node (ref "J16") (pin "61") (pinfunction "B1_61") (pintype "passive"))
      (node (ref "J2") (pin "1") (pinfunction "A1_1") (pintype "passive"))
      (node (ref "J2") (pin "61") (pinfunction "B1_61") (pintype "passive"))
      (node (ref "J3") (pin "1") (pinfunction "A1_1") (pintype "passive"))
      (node (ref "J3") (pin "61") (pinfunction "B1_61") (pintype "passive"))
      (node (ref "J4") (pin "1") (pinfunction "A1_1") (pintype "passive"))
      (node (ref "J4") (pin "61") (pinfunction "B1_61") (pintype "passive"))
      (node (ref "J5") (pin "1") (pinfunction "A1_1") (pintype "passive"))
      (node (ref "J5") (pin "61") (pinfunction "B1_61") (pintype "passive"))
      (node (ref "J6") (pin "1") (pinfunction "A1_1") (pintype "passive"))
      (node (ref "J6") (pin "61") (pinfunction "B1_61") (pintype "passive"))
      (node (ref "J7") (pin "1") (pinfunction "A1_1") (pintype "passive"))
      (node (ref "J7") (pin "61") (pinfunction "B1_61") (pintype "passive"))
      (node (ref "J8") (pin "1") (pinfunction "A1_1") (pintype "passive"))
      (node (ref "J8") (pin "61") (pinfunction "B1_61") (pintype "passive"))
      (node (ref "J9") (pin "1") (pinfunction "A1_1") (pintype "passive"))
      (node (ref "J9") (pin "61") (pinfunction "B1_61") (pintype "passive"))
      (node (ref "U12") (pin "1") (pinfunction "VCCA_1") (pintype "passive"))
      (node (ref "U13") (pin "1") (pinfunction "VCCA_1") (pintype "passive"))
      (node (ref "U14") (pin "1") (pinfunction "VCCA_1") (pintype "passive"))
      (node (ref "U15") (pin "1") (pinfunction "VCCA_1") (pintype "passive"))
    )
    (net (code "190") (name "8V_BUS") (class "Default")
      (node (ref "C15") (pin "1") (pinfunction "1_1") (pintype "passive"))
      (node (ref "C17") (pin "1") (pinfunction "1_1") (pintype "passive"))
      (node (ref "C19") (pin "1") (pinfunction "1_1") (pintype "passive"))
      (node (ref "C21") (pin "1") (pinfunction "1_1") (pintype "passive"))
      (node (ref "C23") (pin "2") (pinfunction "2_2") (pintype "passive"))
      (node (ref "C24") (pin "2") (pinfunction "2_2") (pintype "passive"))
      (node (ref "C27") (pin "2") (pinfunction "2_2") (pintype "passive"))
      (node (ref "C28") (pin "2") (pinfunction "2_2") (pintype "passive"))
      (node (ref "C31") (pin "2") (pinfunction "2_2") (pintype "passive"))
      (node (ref "C32") (pin "2") (pinfunction "2_2") (pintype "passive"))
      (node (ref "C35") (pin "2") (pinfunction "2_2") (pintype "passive"))
      (node (ref "C36") (pin "2") (pinfunction "2_2") (pintype "passive"))
      (node (ref "J1") (pin "120") (pinfunction "B60_120") (pintype "passive"))
      (node (ref "J1") (pin "60") (pinfunction "A60_60") (pintype "passive"))
      (node (ref "J10") (pin "120") (pinfunction "B60_120") (pintype "passive"))
      (node (ref "J10") (pin "60") (pinfunction "A60_60") (pintype "passive"))
      (node (ref "J11") (pin "120") (pinfunction "B60_120") (pintype "passive"))
      (node (ref "J11") (pin "60") (pinfunction "A60_60") (pintype "passive"))
      (node (ref "J12") (pin "120") (pinfunction "B60_120") (pintype "passive"))
      (node (ref "J12") (pin "60") (pinfunction "A60_60") (pintype "passive"))
      (node (ref "J13") (pin "120") (pinfunction "B60_120") (pintype "passive"))
      (node (ref "J13") (pin "60") (pinfunction "A60_60") (pintype "passive"))
      (node (ref "J14") (pin "120") (pinfunction "B60_120") (pintype "passive"))
      (node (ref "J14") (pin "60") (pinfunction "A60_60") (pintype "passive"))
      (node (ref "J15") (pin "120") (pinfunction "B60_120") (pintype "passive"))
      (node (ref "J15") (pin "60") (pinfunction "A60_60") (pintype "passive"))
      (node (ref "J16") (pin "120") (pinfunction "B60_120") (pintype "passive"))
      (node (ref "J16") (pin "60") (pinfunction "A60_60") (pintype "passive"))
      (node (ref "J2") (pin "120") (pinfunction "B60_120") (pintype "passive"))
      (node (ref "J2") (pin "60") (pinfunction "A60_60") (pintype "passive"))
      (node (ref "J3") (pin "120") (pinfunction "B60_120") (pintype "passive"))
      (node (ref "J3") (pin "60") (pinfunction "A60_60") (pintype "passive"))
      (node (ref "J4") (pin "120") (pinfunction "B60_120") (pintype "passive"))
      (node (ref "J4") (pin "60") (pinfunction "A60_60") (pintype "passive"))
      (node (ref "J5") (pin "120") (pinfunction "B60_120") (pintype "passive"))
      (node (ref "J5") (pin "60") (pinfunction "A60_60") (pintype "passive"))
      (node (ref "J6") (pin "120") (pinfunction "B60_120") (pintype "passive"))
      (node (ref "J6") (pin "60") (pinfunction "A60_60") (pintype "passive"))
      (node (ref "J7") (pin "120") (pinfunction "B60_120") (pintype "passive"))
      (node (ref "J7") (pin "60") (pinfunction "A60_60") (pintype "passive"))
      (node (ref "J8") (pin "120") (pinfunction "B60_120") (pintype "passive"))
      (node (ref "J8") (pin "60") (pinfunction "A60_60") (pintype "passive"))
      (node (ref "J9") (pin "120") (pinfunction "B60_120") (pintype "passive"))
      (node (ref "J9") (pin "60") (pinfunction "A60_60") (pintype "passive"))
    )
    (net (code "191") (name "AGND") (class "Default")
      (node (ref "C1") (pin "2") (pinfunction "2_2") (pintype "passive"))
      (node (ref "C10") (pin "1") (pinfunction "1_1") (pintype "passive"))
      (node (ref "C11") (pin "1") (pinfunction "1_1") (pintype "passive"))
      (node (ref "C12") (pin "1") (pinfunction "1_1") (pintype "passive"))
      (node (ref "C13") (pin "1") (pinfunction "1_1") (pintype "passive"))
      (node (ref "C14") (pin "1") (pinfunction "1_1") (pintype "passive"))
      (node (ref "C15") (pin "2") (pinfunction "2_2") (pintype "passive"))
      (node (ref "C16") (pin "2") (pinfunction "2_2") (pintype "passive"))
      (node (ref "C17") (pin "2") (pinfunction "2_2") (pintype "passive"))
      (node (ref "C18") (pin "2") (pinfunction "2_2") (pintype "passive"))
      (node (ref "C19") (pin "2") (pinfunction "2_2") (pintype "passive"))
      (node (ref "C2") (pin "2") (pinfunction "2_2") (pintype "passive"))
      (node (ref "C20") (pin "2") (pinfunction "2_2") (pintype "passive"))
      (node (ref "C21") (pin "2") (pinfunction "2_2") (pintype "passive"))
      (node (ref "C22") (pin "2") (pinfunction "2_2") (pintype "passive"))
      (node (ref "C23") (pin "1") (pinfunction "1_1") (pintype "passive"))
      (node (ref "C24") (pin "1") (pinfunction "1_1") (pintype "passive"))
      (node (ref "C25") (pin "1") (pinfunction "1_1") (pintype "passive"))
      (node (ref "C26") (pin "1") (pinfunction "1_1") (pintype "passive"))
      (node (ref "C27") (pin "1") (pinfunction "1_1") (pintype "passive"))
      (node (ref "C28") (pin "1") (pinfunction "1_1") (pintype "passive"))
      (node (ref "C29") (pin "1") (pinfunction "1_1") (pintype "passive"))
      (node (ref "C3") (pin "2") (pinfunction "2_2") (pintype "passive"))
      (node (ref "C30") (pin "1") (pinfunction "1_1") (pintype "passive"))
      (node (ref "C31") (pin "1") (pinfunction "1_1") (pintype "passive"))
      (node (ref "C32") (pin "1") (pinfunction "1_1") (pintype "passive"))
      (node (ref "C33") (pin "1") (pinfunction "1_1") (pintype "passive"))
      (node (ref "C34") (pin "1") (pinfunction "1_1") (pintype "passive"))
      (node (ref "C35") (pin "1") (pinfunction "1_1") (pintype "passive"))
      (node (ref "C36") (pin "1") (pinfunction "1_1") (pintype "passive"))
      (node (ref "C37") (pin "1") (pinfunction "1_1") (pintype "passive"))
      (node (ref "C38") (pin "1") (pinfunction "1_1") (pintype "passive"))
      (node (ref "C39") (pin "2") (pinfunction "2_2") (pintype "passive"))
      (node (ref "C4") (pin "2") (pinfunction "2_2") (pintype "passive"))
      (node (ref "C40") (pin "2") (pinfunction "2_2") (pintype "passive"))
      (node (ref "C41") (pin "2") (pinfunction "2_2") (pintype "passive"))
      (node (ref "C42") (pin "2") (pinfunction "2_2") (pintype "passive"))
      (node (ref "C43") (pin "2") (pinfunction "2_2") (pintype "passive"))
      (node (ref "C44") (pin "2") (pinfunction "2_2") (pintype "passive"))
      (node (ref "C45") (pin "2") (pinfunction "2_2") (pintype "passive"))
      (node (ref "C46") (pin "2") (pinfunction "2_2") (pintype "passive"))
      (node (ref "C47") (pin "1") (pinfunction "1_1") (pintype "passive"))
      (node (ref "C48") (pin "1") (pinfunction "1_1") (pintype "passive"))
      (node (ref "C49") (pin "1") (pinfunction "1_1") (pintype "passive"))
      (node (ref "C5") (pin "2") (pinfunction "2_2") (pintype "passive"))
      (node (ref "C50") (pin "1") (pinfunction "1_1") (pintype "passive"))
      (node (ref "C6") (pin "2") (pinfunction "2_2") (pintype "passive"))
      (node (ref "C7") (pin "1") (pinfunction "1_1") (pintype "passive"))
      (node (ref "C8") (pin "1") (pinfunction "1_1") (pintype "passive"))
      (node (ref "C9") (pin "1") (pinfunction "1_1") (pintype "passive"))
      (node (ref "J1") (pin "10") (pinfunction "A10_10") (pintype "passive"))
      (node (ref "J1") (pin "108") (pinfunction "B48_108") (pintype "passive"))
      (node (ref "J1") (pin "11") (pinfunction "A11_11") (pintype "passive"))
      (node (ref "J1") (pin "117") (pinfunction "B57_117") (pintype "passive"))
      (node (ref "J1") (pin "119") (pinfunction "B59_119") (pintype "passive"))
      (node (ref "J1") (pin "12") (pinfunction "A12_12") (pintype "passive"))
      (node (ref "J1") (pin "2") (pinfunction "A2_2") (pintype "passive"))
      (node (ref "J1") (pin "21") (pinfunction "A21_21") (pintype "passive"))
      (node (ref "J1") (pin "3") (pinfunction "A3_3") (pintype "passive"))
      (node (ref "J1") (pin "30") (pinfunction "A30_30") (pintype "passive"))
      (node (ref "J1") (pin "39") (pinfunction "A39_39") (pintype "passive"))
      (node (ref "J1") (pin "4") (pinfunction "A4_4") (pintype "passive"))
      (node (ref "J1") (pin "48") (pinfunction "A48_48") (pintype "passive"))
      (node (ref "J1") (pin "5") (pinfunction "A5_5") (pintype "passive"))
      (node (ref "J1") (pin "57") (pinfunction "A57_57") (pintype "passive"))
      (node (ref "J1") (pin "59") (pinfunction "A59_59") (pintype "passive"))
      (node (ref "J1") (pin "6") (pinfunction "A6_6") (pintype "passive"))
      (node (ref "J1") (pin "62") (pinfunction "B2_62") (pintype "passive"))
      (node (ref "J1") (pin "63") (pinfunction "B3_63") (pintype "passive"))
      (node (ref "J1") (pin "64") (pinfunction "B4_64") (pintype "passive"))
      (node (ref "J1") (pin "65") (pinfunction "B5_65") (pintype "passive"))
      (node (ref "J1") (pin "66") (pinfunction "B6_66") (pintype "passive"))
      (node (ref "J1") (pin "67") (pinfunction "B7_67") (pintype "passive"))
      (node (ref "J1") (pin "68") (pinfunction "B8_68") (pintype "passive"))
      (node (ref "J1") (pin "69") (pinfunction "B9_69") (pintype "passive"))
      (node (ref "J1") (pin "7") (pinfunction "A7_7") (pintype "passive"))
      (node (ref "J1") (pin "70") (pinfunction "B10_70") (pintype "passive"))
      (node (ref "J1") (pin "71") (pinfunction "B11_71") (pintype "passive"))
      (node (ref "J1") (pin "72") (pinfunction "B12_72") (pintype "passive"))
      (node (ref "J1") (pin "8") (pinfunction "A8_8") (pintype "passive"))
      (node (ref "J1") (pin "81") (pinfunction "B21_81") (pintype "passive"))
      (node (ref "J1") (pin "9") (pinfunction "A9_9") (pintype "passive"))
      (node (ref "J1") (pin "90") (pinfunction "B30_90") (pintype "passive"))
      (node (ref "J1") (pin "99") (pinfunction "B39_99") (pintype "passive"))
      (node (ref "J10") (pin "10") (pinfunction "A10_10") (pintype "passive"))
      (node (ref "J10") (pin "108") (pinfunction "B48_108") (pintype "passive"))
      (node (ref "J10") (pin "11") (pinfunction "A11_11") (pintype "passive"))
      (node (ref "J10") (pin "117") (pinfunction "B57_117") (pintype "passive"))
      (node (ref "J10") (pin "119") (pinfunction "B59_119") (pintype "passive"))
      (node (ref "J10") (pin "12") (pinfunction "A12_12") (pintype "passive"))
      (node (ref "J10") (pin "2") (pinfunction "A2_2") (pintype "passive"))
      (node (ref "J10") (pin "21") (pinfunction "A21_21") (pintype "passive"))
      (node (ref "J10") (pin "3") (pinfunction "A3_3") (pintype "passive"))
      (node (ref "J10") (pin "30") (pinfunction "A30_30") (pintype "passive"))
      (node (ref "J10") (pin "39") (pinfunction "A39_39") (pintype "passive"))
      (node (ref "J10") (pin "4") (pinfunction "A4_4") (pintype "passive"))
      (node (ref "J10") (pin "48") (pinfunction "A48_48") (pintype "passive"))
      (node (ref "J10") (pin "5") (pinfunction "A5_5") (pintype "passive"))
      (node (ref "J10") (pin "57") (pinfunction "A57_57") (pintype "passive"))
      (node (ref "J10") (pin "59") (pinfunction "A59_59") (pintype "passive"))
      (node (ref "J10") (pin "6") (pinfunction "A6_6") (pintype "passive"))
      (node (ref "J10") (pin "62") (pinfunction "B2_62") (pintype "passive"))
      (node (ref "J10") (pin "63") (pinfunction "B3_63") (pintype "passive"))
      (node (ref "J10") (pin "64") (pinfunction "B4_64") (pintype "passive"))
      (node (ref "J10") (pin "65") (pinfunction "B5_65") (pintype "passive"))
      (node (ref "J10") (pin "66") (pinfunction "B6_66") (pintype "passive"))
      (node (ref "J10") (pin "67") (pinfunction "B7_67") (pintype "passive"))
      (node (ref "J10") (pin "68") (pinfunction "B8_68") (pintype "passive"))
      (node (ref "J10") (pin "69") (pinfunction "B9_69") (pintype "passive"))
      (node (ref "J10") (pin "7") (pinfunction "A7_7") (pintype "passive"))
      (node (ref "J10") (pin "70") (pinfunction "B10_70") (pintype "passive"))
      (node (ref "J10") (pin "71") (pinfunction "B11_71") (pintype "passive"))
      (node (ref "J10") (pin "72") (pinfunction "B12_72") (pintype "passive"))
      (node (ref "J10") (pin "8") (pinfunction "A8_8") (pintype "passive"))
      (node (ref "J10") (pin "81") (pinfunction "B21_81") (pintype "passive"))
      (node (ref "J10") (pin "9") (pinfunction "A9_9") (pintype "passive"))
      (node (ref "J10") (pin "90") (pinfunction "B30_90") (pintype "passive"))
      (node (ref "J10") (pin "99") (pinfunction "B39_99") (pintype "passive"))
      (node (ref "J11") (pin "10") (pinfunction "A10_10") (pintype "passive"))
      (node (ref "J11") (pin "108") (pinfunction "B48_108") (pintype "passive"))
      (node (ref "J11") (pin "11") (pinfunction "A11_11") (pintype "passive"))
      (node (ref "J11") (pin "117") (pinfunction "B57_117") (pintype "passive"))
      (node (ref "J11") (pin "119") (pinfunction "B59_119") (pintype "passive"))
      (node (ref "J11") (pin "12") (pinfunction "A12_12") (pintype "passive"))
      (node (ref "J11") (pin "2") (pinfunction "A2_2") (pintype "passive"))
      (node (ref "J11") (pin "21") (pinfunction "A21_21") (pintype "passive"))
      (node (ref "J11") (pin "3") (pinfunction "A3_3") (pintype "passive"))
      (node (ref "J11") (pin "30") (pinfunction "A30_30") (pintype "passive"))
      (node (ref "J11") (pin "39") (pinfunction "A39_39") (pintype "passive"))
      (node (ref "J11") (pin "4") (pinfunction "A4_4") (pintype "passive"))
      (node (ref "J11") (pin "48") (pinfunction "A48_48") (pintype "passive"))
      (node (ref "J11") (pin "5") (pinfunction "A5_5") (pintype "passive"))
      (node (ref "J11") (pin "57") (pinfunction "A57_57") (pintype "passive"))
      (node (ref "J11") (pin "59") (pinfunction "A59_59") (pintype "passive"))
      (node (ref "J11") (pin "6") (pinfunction "A6_6") (pintype "passive"))
      (node (ref "J11") (pin "62") (pinfunction "B2_62") (pintype "passive"))
      (node (ref "J11") (pin "63") (pinfunction "B3_63") (pintype "passive"))
      (node (ref "J11") (pin "64") (pinfunction "B4_64") (pintype "passive"))
      (node (ref "J11") (pin "65") (pinfunction "B5_65") (pintype "passive"))
      (node (ref "J11") (pin "66") (pinfunction "B6_66") (pintype "passive"))
      (node (ref "J11") (pin "67") (pinfunction "B7_67") (pintype "passive"))
      (node (ref "J11") (pin "68") (pinfunction "B8_68") (pintype "passive"))
      (node (ref "J11") (pin "69") (pinfunction "B9_69") (pintype "passive"))
      (node (ref "J11") (pin "7") (pinfunction "A7_7") (pintype "passive"))
      (node (ref "J11") (pin "70") (pinfunction "B10_70") (pintype "passive"))
      (node (ref "J11") (pin "71") (pinfunction "B11_71") (pintype "passive"))
      (node (ref "J11") (pin "72") (pinfunction "B12_72") (pintype "passive"))
      (node (ref "J11") (pin "8") (pinfunction "A8_8") (pintype "passive"))
      (node (ref "J11") (pin "81") (pinfunction "B21_81") (pintype "passive"))
      (node (ref "J11") (pin "9") (pinfunction "A9_9") (pintype "passive"))
      (node (ref "J11") (pin "90") (pinfunction "B30_90") (pintype "passive"))
      (node (ref "J11") (pin "99") (pinfunction "B39_99") (pintype "passive"))
      (node (ref "J12") (pin "10") (pinfunction "A10_10") (pintype "passive"))
      (node (ref "J12") (pin "108") (pinfunction "B48_108") (pintype "passive"))
      (node (ref "J12") (pin "11") (pinfunction "A11_11") (pintype "passive"))
      (node (ref "J12") (pin "117") (pinfunction "B57_117") (pintype "passive"))
      (node (ref "J12") (pin "119") (pinfunction "B59_119") (pintype "passive"))
      (node (ref "J12") (pin "12") (pinfunction "A12_12") (pintype "passive"))
      (node (ref "J12") (pin "2") (pinfunction "A2_2") (pintype "passive"))
      (node (ref "J12") (pin "21") (pinfunction "A21_21") (pintype "passive"))
      (node (ref "J12") (pin "3") (pinfunction "A3_3") (pintype "passive"))
      (node (ref "J12") (pin "30") (pinfunction "A30_30") (pintype "passive"))
      (node (ref "J12") (pin "39") (pinfunction "A39_39") (pintype "passive"))
      (node (ref "J12") (pin "4") (pinfunction "A4_4") (pintype "passive"))
      (node (ref "J12") (pin "48") (pinfunction "A48_48") (pintype "passive"))
      (node (ref "J12") (pin "5") (pinfunction "A5_5") (pintype "passive"))
      (node (ref "J12") (pin "57") (pinfunction "A57_57") (pintype "passive"))
      (node (ref "J12") (pin "59") (pinfunction "A59_59") (pintype "passive"))
      (node (ref "J12") (pin "6") (pinfunction "A6_6") (pintype "passive"))
      (node (ref "J12") (pin "62") (pinfunction "B2_62") (pintype "passive"))
      (node (ref "J12") (pin "63") (pinfunction "B3_63") (pintype "passive"))
      (node (ref "J12") (pin "64") (pinfunction "B4_64") (pintype "passive"))
      (node (ref "J12") (pin "65") (pinfunction "B5_65") (pintype "passive"))
      (node (ref "J12") (pin "66") (pinfunction "B6_66") (pintype "passive"))
      (node (ref "J12") (pin "67") (pinfunction "B7_67") (pintype "passive"))
      (node (ref "J12") (pin "68") (pinfunction "B8_68") (pintype "passive"))
      (node (ref "J12") (pin "69") (pinfunction "B9_69") (pintype "passive"))
      (node (ref "J12") (pin "7") (pinfunction "A7_7") (pintype "passive"))
      (node (ref "J12") (pin "70") (pinfunction "B10_70") (pintype "passive"))
      (node (ref "J12") (pin "71") (pinfunction "B11_71") (pintype "passive"))
      (node (ref "J12") (pin "72") (pinfunction "B12_72") (pintype "passive"))
      (node (ref "J12") (pin "8") (pinfunction "A8_8") (pintype "passive"))
      (node (ref "J12") (pin "81") (pinfunction "B21_81") (pintype "passive"))
      (node (ref "J12") (pin "9") (pinfunction "A9_9") (pintype "passive"))
      (node (ref "J12") (pin "90") (pinfunction "B30_90") (pintype "passive"))
      (node (ref "J12") (pin "99") (pinfunction "B39_99") (pintype "passive"))
      (node (ref "J13") (pin "10") (pinfunction "A10_10") (pintype "passive"))
      (node (ref "J13") (pin "108") (pinfunction "B48_108") (pintype "passive"))
      (node (ref "J13") (pin "11") (pinfunction "A11_11") (pintype "passive"))
      (node (ref "J13") (pin "117") (pinfunction "B57_117") (pintype "passive"))
      (node (ref "J13") (pin "119") (pinfunction "B59_119") (pintype "passive"))
      (node (ref "J13") (pin "12") (pinfunction "A12_12") (pintype "passive"))
      (node (ref "J13") (pin "2") (pinfunction "A2_2") (pintype "passive"))
      (node (ref "J13") (pin "21") (pinfunction "A21_21") (pintype "passive"))
      (node (ref "J13") (pin "3") (pinfunction "A3_3") (pintype "passive"))
      (node (ref "J13") (pin "30") (pinfunction "A30_30") (pintype "passive"))
      (node (ref "J13") (pin "39") (pinfunction "A39_39") (pintype "passive"))
      (node (ref "J13") (pin "4") (pinfunction "A4_4") (pintype "passive"))
      (node (ref "J13") (pin "48") (pinfunction "A48_48") (pintype "passive"))
      (node (ref "J13") (pin "5") (pinfunction "A5_5") (pintype "passive"))
      (node (ref "J13") (pin "57") (pinfunction "A57_57") (pintype "passive"))
      (node (ref "J13") (pin "59") (pinfunction "A59_59") (pintype "passive"))
      (node (ref "J13") (pin "6") (pinfunction "A6_6") (pintype "passive"))
      (node (ref "J13") (pin "62") (pinfunction "B2_62") (pintype "passive"))
      (node (ref "J13") (pin "63") (pinfunction "B3_63") (pintype "passive"))
      (node (ref "J13") (pin "64") (pinfunction "B4_64") (pintype "passive"))
      (node (ref "J13") (pin "65") (pinfunction "B5_65") (pintype "passive"))
      (node (ref "J13") (pin "66") (pinfunction "B6_66") (pintype "passive"))
      (node (ref "J13") (pin "67") (pinfunction "B7_67") (pintype "passive"))
      (node (ref "J13") (pin "68") (pinfunction "B8_68") (pintype "passive"))
      (node (ref "J13") (pin "69") (pinfunction "B9_69") (pintype "passive"))
      (node (ref "J13") (pin "7") (pinfunction "A7_7") (pintype "passive"))
      (node (ref "J13") (pin "70") (pinfunction "B10_70") (pintype "passive"))
      (node (ref "J13") (pin "71") (pinfunction "B11_71") (pintype "passive"))
      (node (ref "J13") (pin "72") (pinfunction "B12_72") (pintype "passive"))
      (node (ref "J13") (pin "8") (pinfunction "A8_8") (pintype "passive"))
      (node (ref "J13") (pin "81") (pinfunction "B21_81") (pintype "passive"))
      (node (ref "J13") (pin "9") (pinfunction "A9_9") (pintype "passive"))
      (node (ref "J13") (pin "90") (pinfunction "B30_90") (pintype "passive"))
      (node (ref "J13") (pin "99") (pinfunction "B39_99") (pintype "passive"))
      (node (ref "J14") (pin "10") (pinfunction "A10_10") (pintype "passive"))
      (node (ref "J14") (pin "108") (pinfunction "B48_108") (pintype "passive"))
      (node (ref "J14") (pin "11") (pinfunction "A11_11") (pintype "passive"))
      (node (ref "J14") (pin "117") (pinfunction "B57_117") (pintype "passive"))
      (node (ref "J14") (pin "119") (pinfunction "B59_119") (pintype "passive"))
      (node (ref "J14") (pin "12") (pinfunction "A12_12") (pintype "passive"))
      (node (ref "J14") (pin "2") (pinfunction "A2_2") (pintype "passive"))
      (node (ref "J14") (pin "21") (pinfunction "A21_21") (pintype "passive"))
      (node (ref "J14") (pin "3") (pinfunction "A3_3") (pintype "passive"))
      (node (ref "J14") (pin "30") (pinfunction "A30_30") (pintype "passive"))
      (node (ref "J14") (pin "39") (pinfunction "A39_39") (pintype "passive"))
      (node (ref "J14") (pin "4") (pinfunction "A4_4") (pintype "passive"))
      (node (ref "J14") (pin "48") (pinfunction "A48_48") (pintype "passive"))
      (node (ref "J14") (pin "5") (pinfunction "A5_5") (pintype "passive"))
      (node (ref "J14") (pin "57") (pinfunction "A57_57") (pintype "passive"))
      (node (ref "J14") (pin "59") (pinfunction "A59_59") (pintype "passive"))
      (node (ref "J14") (pin "6") (pinfunction "A6_6") (pintype "passive"))
      (node (ref "J14") (pin "62") (pinfunction "B2_62") (pintype "passive"))
      (node (ref "J14") (pin "63") (pinfunction "B3_63") (pintype "passive"))
      (node (ref "J14") (pin "64") (pinfunction "B4_64") (pintype "passive"))
      (node (ref "J14") (pin "65") (pinfunction "B5_65") (pintype "passive"))
      (node (ref "J14") (pin "66") (pinfunction "B6_66") (pintype "passive"))
      (node (ref "J14") (pin "67") (pinfunction "B7_67") (pintype "passive"))
      (node (ref "J14") (pin "68") (pinfunction "B8_68") (pintype "passive"))
      (node (ref "J14") (pin "69") (pinfunction "B9_69") (pintype "passive"))
      (node (ref "J14") (pin "7") (pinfunction "A7_7") (pintype "passive"))
      (node (ref "J14") (pin "70") (pinfunction "B10_70") (pintype "passive"))
      (node (ref "J14") (pin "71") (pinfunction "B11_71") (pintype "passive"))
      (node (ref "J14") (pin "72") (pinfunction "B12_72") (pintype "passive"))
      (node (ref "J14") (pin "8") (pinfunction "A8_8") (pintype "passive"))
      (node (ref "J14") (pin "81") (pinfunction "B21_81") (pintype "passive"))
      (node (ref "J14") (pin "9") (pinfunction "A9_9") (pintype "passive"))
      (node (ref "J14") (pin "90") (pinfunction "B30_90") (pintype "passive"))
      (node (ref "J14") (pin "99") (pinfunction "B39_99") (pintype "passive"))
      (node (ref "J15") (pin "10") (pinfunction "A10_10") (pintype "passive"))
      (node (ref "J15") (pin "108") (pinfunction "B48_108") (pintype "passive"))
      (node (ref "J15") (pin "11") (pinfunction "A11_11") (pintype "passive"))
      (node (ref "J15") (pin "117") (pinfunction "B57_117") (pintype "passive"))
      (node (ref "J15") (pin "119") (pinfunction "B59_119") (pintype "passive"))
      (node (ref "J15") (pin "12") (pinfunction "A12_12") (pintype "passive"))
      (node (ref "J15") (pin "2") (pinfunction "A2_2") (pintype "passive"))
      (node (ref "J15") (pin "21") (pinfunction "A21_21") (pintype "passive"))
      (node (ref "J15") (pin "3") (pinfunction "A3_3") (pintype "passive"))
      (node (ref "J15") (pin "30") (pinfunction "A30_30") (pintype "passive"))
      (node (ref "J15") (pin "39") (pinfunction "A39_39") (pintype "passive"))
      (node (ref "J15") (pin "4") (pinfunction "A4_4") (pintype "passive"))
      (node (ref "J15") (pin "48") (pinfunction "A48_48") (pintype "passive"))
      (node (ref "J15") (pin "5") (pinfunction "A5_5") (pintype "passive"))
      (node (ref "J15") (pin "57") (pinfunction "A57_57") (pintype "passive"))
      (node (ref "J15") (pin "59") (pinfunction "A59_59") (pintype "passive"))
      (node (ref "J15") (pin "6") (pinfunction "A6_6") (pintype "passive"))
      (node (ref "J15") (pin "62") (pinfunction "B2_62") (pintype "passive"))
      (node (ref "J15") (pin "63") (pinfunction "B3_63") (pintype "passive"))
      (node (ref "J15") (pin "64") (pinfunction "B4_64") (pintype "passive"))
      (node (ref "J15") (pin "65") (pinfunction "B5_65") (pintype "passive"))
      (node (ref "J15") (pin "66") (pinfunction "B6_66") (pintype "passive"))
      (node (ref "J15") (pin "67") (pinfunction "B7_67") (pintype "passive"))
      (node (ref "J15") (pin "68") (pinfunction "B8_68") (pintype "passive"))
      (node (ref "J15") (pin "69") (pinfunction "B9_69") (pintype "passive"))
      (node (ref "J15") (pin "7") (pinfunction "A7_7") (pintype "passive"))
      (node (ref "J15") (pin "70") (pinfunction "B10_70") (pintype "passive"))
      (node (ref "J15") (pin "71") (pinfunction "B11_71") (pintype "passive"))
      (node (ref "J15") (pin "72") (pinfunction "B12_72") (pintype "passive"))
      (node (ref "J15") (pin "8") (pinfunction "A8_8") (pintype "passive"))
      (node (ref "J15") (pin "81") (pinfunction "B21_81") (pintype "passive"))
      (node (ref "J15") (pin "9") (pinfunction "A9_9") (pintype "passive"))
      (node (ref "J15") (pin "90") (pinfunction "B30_90") (pintype "passive"))
      (node (ref "J15") (pin "99") (pinfunction "B39_99") (pintype "passive"))
      (node (ref "J16") (pin "10") (pinfunction "A10_10") (pintype "passive"))
      (node (ref "J16") (pin "108") (pinfunction "B48_108") (pintype "passive"))
      (node (ref "J16") (pin "11") (pinfunction "A11_11") (pintype "passive"))
      (node (ref "J16") (pin "117") (pinfunction "B57_117") (pintype "passive"))
      (node (ref "J16") (pin "119") (pinfunction "B59_119") (pintype "passive"))
      (node (ref "J16") (pin "12") (pinfunction "A12_12") (pintype "passive"))
      (node (ref "J16") (pin "2") (pinfunction "A2_2") (pintype "passive"))
      (node (ref "J16") (pin "21") (pinfunction "A21_21") (pintype "passive"))
      (node (ref "J16") (pin "3") (pinfunction "A3_3") (pintype "passive"))
      (node (ref "J16") (pin "30") (pinfunction "A30_30") (pintype "passive"))
      (node (ref "J16") (pin "39") (pinfunction "A39_39") (pintype "passive"))
      (node (ref "J16") (pin "4") (pinfunction "A4_4") (pintype "passive"))
      (node (ref "J16") (pin "48") (pinfunction "A48_48") (pintype "passive"))
      (node (ref "J16") (pin "5") (pinfunction "A5_5") (pintype "passive"))
      (node (ref "J16") (pin "57") (pinfunction "A57_57") (pintype "passive"))
      (node (ref "J16") (pin "59") (pinfunction "A59_59") (pintype "passive"))
      (node (ref "J16") (pin "6") (pinfunction "A6_6") (pintype "passive"))
      (node (ref "J16") (pin "62") (pinfunction "B2_62") (pintype "passive"))
      (node (ref "J16") (pin "63") (pinfunction "B3_63") (pintype "passive"))
      (node (ref "J16") (pin "64") (pinfunction "B4_64") (pintype "passive"))
      (node (ref "J16") (pin "65") (pinfunction "B5_65") (pintype "passive"))
      (node (ref "J16") (pin "66") (pinfunction "B6_66") (pintype "passive"))
      (node (ref "J16") (pin "67") (pinfunction "B7_67") (pintype "passive"))
      (node (ref "J16") (pin "68") (pinfunction "B8_68") (pintype "passive"))
      (node (ref "J16") (pin "69") (pinfunction "B9_69") (pintype "passive"))
      (node (ref "J16") (pin "7") (pinfunction "A7_7") (pintype "passive"))
      (node (ref "J16") (pin "70") (pinfunction "B10_70") (pintype "passive"))
      (node (ref "J16") (pin "71") (pinfunction "B11_71") (pintype "passive"))
      (node (ref "J16") (pin "72") (pinfunction "B12_72") (pintype "passive"))
      (node (ref "J16") (pin "8") (pinfunction "A8_8") (pintype "passive"))
      (node (ref "J16") (pin "81") (pinfunction "B21_81") (pintype "passive"))
      (node (ref "J16") (pin "9") (pinfunction "A9_9") (pintype "passive"))
      (node (ref "J16") (pin "90") (pinfunction "B30_90") (pintype "passive"))
      (node (ref "J16") (pin "99") (pinfunction "B39_99") (pintype "passive"))
      (node (ref "J2") (pin "10") (pinfunction "A10_10") (pintype "passive"))
      (node (ref "J2") (pin "108") (pinfunction "B48_108") (pintype "passive"))
      (node (ref "J2") (pin "11") (pinfunction "A11_11") (pintype "passive"))
      (node (ref "J2") (pin "117") (pinfunction "B57_117") (pintype "passive"))
      (node (ref "J2") (pin "119") (pinfunction "B59_119") (pintype "passive"))
      (node (ref "J2") (pin "12") (pinfunction "A12_12") (pintype "passive"))
      (node (ref "J2") (pin "2") (pinfunction "A2_2") (pintype "passive"))
      (node (ref "J2") (pin "21") (pinfunction "A21_21") (pintype "passive"))
      (node (ref "J2") (pin "3") (pinfunction "A3_3") (pintype "passive"))
      (node (ref "J2") (pin "30") (pinfunction "A30_30") (pintype "passive"))
      (node (ref "J2") (pin "39") (pinfunction "A39_39") (pintype "passive"))
      (node (ref "J2") (pin "4") (pinfunction "A4_4") (pintype "passive"))
      (node (ref "J2") (pin "48") (pinfunction "A48_48") (pintype "passive"))
      (node (ref "J2") (pin "5") (pinfunction "A5_5") (pintype "passive"))
      (node (ref "J2") (pin "57") (pinfunction "A57_57") (pintype "passive"))
      (node (ref "J2") (pin "59") (pinfunction "A59_59") (pintype "passive"))
      (node (ref "J2") (pin "6") (pinfunction "A6_6") (pintype "passive"))
      (node (ref "J2") (pin "62") (pinfunction "B2_62") (pintype "passive"))
      (node (ref "J2") (pin "63") (pinfunction "B3_63") (pintype "passive"))
      (node (ref "J2") (pin "64") (pinfunction "B4_64") (pintype "passive"))
      (node (ref "J2") (pin "65") (pinfunction "B5_65") (pintype "passive"))
      (node (ref "J2") (pin "66") (pinfunction "B6_66") (pintype "passive"))
      (node (ref "J2") (pin "67") (pinfunction "B7_67") (pintype "passive"))
      (node (ref "J2") (pin "68") (pinfunction "B8_68") (pintype "passive"))
      (node (ref "J2") (pin "69") (pinfunction "B9_69") (pintype "passive"))
      (node (ref "J2") (pin "7") (pinfunction "A7_7") (pintype "passive"))
      (node (ref "J2") (pin "70") (pinfunction "B10_70") (pintype "passive"))
      (node (ref "J2") (pin "71") (pinfunction "B11_71") (pintype "passive"))
      (node (ref "J2") (pin "72") (pinfunction "B12_72") (pintype "passive"))
      (node (ref "J2") (pin "8") (pinfunction "A8_8") (pintype "passive"))
      (node (ref "J2") (pin "81") (pinfunction "B21_81") (pintype "passive"))
      (node (ref "J2") (pin "9") (pinfunction "A9_9") (pintype "passive"))
      (node (ref "J2") (pin "90") (pinfunction "B30_90") (pintype "passive"))
      (node (ref "J2") (pin "99") (pinfunction "B39_99") (pintype "passive"))
      (node (ref "J3") (pin "10") (pinfunction "A10_10") (pintype "passive"))
      (node (ref "J3") (pin "108") (pinfunction "B48_108") (pintype "passive"))
      (node (ref "J3") (pin "11") (pinfunction "A11_11") (pintype "passive"))
      (node (ref "J3") (pin "117") (pinfunction "B57_117") (pintype "passive"))
      (node (ref "J3") (pin "119") (pinfunction "B59_119") (pintype "passive"))
      (node (ref "J3") (pin "12") (pinfunction "A12_12") (pintype "passive"))
      (node (ref "J3") (pin "2") (pinfunction "A2_2") (pintype "passive"))
      (node (ref "J3") (pin "21") (pinfunction "A21_21") (pintype "passive"))
      (node (ref "J3") (pin "3") (pinfunction "A3_3") (pintype "passive"))
      (node (ref "J3") (pin "30") (pinfunction "A30_30") (pintype "passive"))
      (node (ref "J3") (pin "39") (pinfunction "A39_39") (pintype "passive"))
      (node (ref "J3") (pin "4") (pinfunction "A4_4") (pintype "passive"))
      (node (ref "J3") (pin "48") (pinfunction "A48_48") (pintype "passive"))
      (node (ref "J3") (pin "5") (pinfunction "A5_5") (pintype "passive"))
      (node (ref "J3") (pin "57") (pinfunction "A57_57") (pintype "passive"))
      (node (ref "J3") (pin "59") (pinfunction "A59_59") (pintype "passive"))
      (node (ref "J3") (pin "6") (pinfunction "A6_6") (pintype "passive"))
      (node (ref "J3") (pin "62") (pinfunction "B2_62") (pintype "passive"))
      (node (ref "J3") (pin "63") (pinfunction "B3_63") (pintype "passive"))
      (node (ref "J3") (pin "64") (pinfunction "B4_64") (pintype "passive"))
      (node (ref "J3") (pin "65") (pinfunction "B5_65") (pintype "passive"))
      (node (ref "J3") (pin "66") (pinfunction "B6_66") (pintype "passive"))
      (node (ref "J3") (pin "67") (pinfunction "B7_67") (pintype "passive"))
      (node (ref "J3") (pin "68") (pinfunction "B8_68") (pintype "passive"))
      (node (ref "J3") (pin "69") (pinfunction "B9_69") (pintype "passive"))
      (node (ref "J3") (pin "7") (pinfunction "A7_7") (pintype "passive"))
      (node (ref "J3") (pin "70") (pinfunction "B10_70") (pintype "passive"))
      (node (ref "J3") (pin "71") (pinfunction "B11_71") (pintype "passive"))
      (node (ref "J3") (pin "72") (pinfunction "B12_72") (pintype "passive"))
      (node (ref "J3") (pin "8") (pinfunction "A8_8") (pintype "passive"))
      (node (ref "J3") (pin "81") (pinfunction "B21_81") (pintype "passive"))
      (node (ref "J3") (pin "9") (pinfunction "A9_9") (pintype "passive"))
      (node (ref "J3") (pin "90") (pinfunction "B30_90") (pintype "passive"))
      (node (ref "J3") (pin "99") (pinfunction "B39_99") (pintype "passive"))
      (node (ref "J4") (pin "10") (pinfunction "A10_10") (pintype "passive"))
      (node (ref "J4") (pin "108") (pinfunction "B48_108") (pintype "passive"))
      (node (ref "J4") (pin "11") (pinfunction "A11_11") (pintype "passive"))
      (node (ref "J4") (pin "117") (pinfunction "B57_117") (pintype "passive"))
      (node (ref "J4") (pin "119") (pinfunction "B59_119") (pintype "passive"))
      (node (ref "J4") (pin "12") (pinfunction "A12_12") (pintype "passive"))
      (node (ref "J4") (pin "2") (pinfunction "A2_2") (pintype "passive"))
      (node (ref "J4") (pin "21") (pinfunction "A21_21") (pintype "passive"))
      (node (ref "J4") (pin "3") (pinfunction "A3_3") (pintype "passive"))
      (node (ref "J4") (pin "30") (pinfunction "A30_30") (pintype "passive"))
      (node (ref "J4") (pin "39") (pinfunction "A39_39") (pintype "passive"))
      (node (ref "J4") (pin "4") (pinfunction "A4_4") (pintype "passive"))
      (node (ref "J4") (pin "48") (pinfunction "A48_48") (pintype "passive"))
      (node (ref "J4") (pin "5") (pinfunction "A5_5") (pintype "passive"))
      (node (ref "J4") (pin "57") (pinfunction "A57_57") (pintype "passive"))
      (node (ref "J4") (pin "59") (pinfunction "A59_59") (pintype "passive"))
      (node (ref "J4") (pin "6") (pinfunction "A6_6") (pintype "passive"))
      (node (ref "J4") (pin "62") (pinfunction "B2_62") (pintype "passive"))
      (node (ref "J4") (pin "63") (pinfunction "B3_63") (pintype "passive"))
      (node (ref "J4") (pin "64") (pinfunction "B4_64") (pintype "passive"))
      (node (ref "J4") (pin "65") (pinfunction "B5_65") (pintype "passive"))
      (node (ref "J4") (pin "66") (pinfunction "B6_66") (pintype "passive"))
      (node (ref "J4") (pin "67") (pinfunction "B7_67") (pintype "passive"))
      (node (ref "J4") (pin "68") (pinfunction "B8_68") (pintype "passive"))
      (node (ref "J4") (pin "69") (pinfunction "B9_69") (pintype "passive"))
      (node (ref "J4") (pin "7") (pinfunction "A7_7") (pintype "passive"))
      (node (ref "J4") (pin "70") (pinfunction "B10_70") (pintype "passive"))
      (node (ref "J4") (pin "71") (pinfunction "B11_71") (pintype "passive"))
      (node (ref "J4") (pin "72") (pinfunction "B12_72") (pintype "passive"))
      (node (ref "J4") (pin "8") (pinfunction "A8_8") (pintype "passive"))
      (node (ref "J4") (pin "81") (pinfunction "B21_81") (pintype "passive"))
      (node (ref "J4") (pin "9") (pinfunction "A9_9") (pintype "passive"))
      (node (ref "J4") (pin "90") (pinfunction "B30_90") (pintype "passive"))
      (node (ref "J4") (pin "99") (pinfunction "B39_99") (pintype "passive"))
      (node (ref "J5") (pin "10") (pinfunction "A10_10") (pintype "passive"))
      (node (ref "J5") (pin "108") (pinfunction "B48_108") (pintype "passive"))
      (node (ref "J5") (pin "11") (pinfunction "A11_11") (pintype "passive"))
      (node (ref "J5") (pin "117") (pinfunction "B57_117") (pintype "passive"))
      (node (ref "J5") (pin "119") (pinfunction "B59_119") (pintype "passive"))
      (node (ref "J5") (pin "12") (pinfunction "A12_12") (pintype "passive"))
      (node (ref "J5") (pin "2") (pinfunction "A2_2") (pintype "passive"))
      (node (ref "J5") (pin "21") (pinfunction "A21_21") (pintype "passive"))
      (node (ref "J5") (pin "3") (pinfunction "A3_3") (pintype "passive"))
      (node (ref "J5") (pin "30") (pinfunction "A30_30") (pintype "passive"))
      (node (ref "J5") (pin "39") (pinfunction "A39_39") (pintype "passive"))
      (node (ref "J5") (pin "4") (pinfunction "A4_4") (pintype "passive"))
      (node (ref "J5") (pin "48") (pinfunction "A48_48") (pintype "passive"))
      (node (ref "J5") (pin "5") (pinfunction "A5_5") (pintype "passive"))
      (node (ref "J5") (pin "57") (pinfunction "A57_57") (pintype "passive"))
      (node (ref "J5") (pin "59") (pinfunction "A59_59") (pintype "passive"))
      (node (ref "J5") (pin "6") (pinfunction "A6_6") (pintype "passive"))
      (node (ref "J5") (pin "62") (pinfunction "B2_62") (pintype "passive"))
      (node (ref "J5") (pin "63") (pinfunction "B3_63") (pintype "passive"))
      (node (ref "J5") (pin "64") (pinfunction "B4_64") (pintype "passive"))
      (node (ref "J5") (pin "65") (pinfunction "B5_65") (pintype "passive"))
      (node (ref "J5") (pin "66") (pinfunction "B6_66") (pintype "passive"))
      (node (ref "J5") (pin "67") (pinfunction "B7_67") (pintype "passive"))
      (node (ref "J5") (pin "68") (pinfunction "B8_68") (pintype "passive"))
      (node (ref "J5") (pin "69") (pinfunction "B9_69") (pintype "passive"))
      (node (ref "J5") (pin "7") (pinfunction "A7_7") (pintype "passive"))
      (node (ref "J5") (pin "70") (pinfunction "B10_70") (pintype "passive"))
      (node (ref "J5") (pin "71") (pinfunction "B11_71") (pintype "passive"))
      (node (ref "J5") (pin "72") (pinfunction "B12_72") (pintype "passive"))
      (node (ref "J5") (pin "8") (pinfunction "A8_8") (pintype "passive"))
      (node (ref "J5") (pin "81") (pinfunction "B21_81") (pintype "passive"))
      (node (ref "J5") (pin "9") (pinfunction "A9_9") (pintype "passive"))
      (node (ref "J5") (pin "90") (pinfunction "B30_90") (pintype "passive"))
      (node (ref "J5") (pin "99") (pinfunction "B39_99") (pintype "passive"))
      (node (ref "J6") (pin "10") (pinfunction "A10_10") (pintype "passive"))
      (node (ref "J6") (pin "108") (pinfunction "B48_108") (pintype "passive"))
      (node (ref "J6") (pin "11") (pinfunction "A11_11") (pintype "passive"))
      (node (ref "J6") (pin "117") (pinfunction "B57_117") (pintype "passive"))
      (node (ref "J6") (pin "119") (pinfunction "B59_119") (pintype "passive"))
      (node (ref "J6") (pin "12") (pinfunction "A12_12") (pintype "passive"))
      (node (ref "J6") (pin "2") (pinfunction "A2_2") (pintype "passive"))
      (node (ref "J6") (pin "21") (pinfunction "A21_21") (pintype "passive"))
      (node (ref "J6") (pin "3") (pinfunction "A3_3") (pintype "passive"))
      (node (ref "J6") (pin "30") (pinfunction "A30_30") (pintype "passive"))
      (node (ref "J6") (pin "39") (pinfunction "A39_39") (pintype "passive"))
      (node (ref "J6") (pin "4") (pinfunction "A4_4") (pintype "passive"))
      (node (ref "J6") (pin "48") (pinfunction "A48_48") (pintype "passive"))
      (node (ref "J6") (pin "5") (pinfunction "A5_5") (pintype "passive"))
      (node (ref "J6") (pin "57") (pinfunction "A57_57") (pintype "passive"))
      (node (ref "J6") (pin "59") (pinfunction "A59_59") (pintype "passive"))
      (node (ref "J6") (pin "6") (pinfunction "A6_6") (pintype "passive"))
      (node (ref "J6") (pin "62") (pinfunction "B2_62") (pintype "passive"))
      (node (ref "J6") (pin "63") (pinfunction "B3_63") (pintype "passive"))
      (node (ref "J6") (pin "64") (pinfunction "B4_64") (pintype "passive"))
      (node (ref "J6") (pin "65") (pinfunction "B5_65") (pintype "passive"))
      (node (ref "J6") (pin "66") (pinfunction "B6_66") (pintype "passive"))
      (node (ref "J6") (pin "67") (pinfunction "B7_67") (pintype "passive"))
      (node (ref "J6") (pin "68") (pinfunction "B8_68") (pintype "passive"))
      (node (ref "J6") (pin "69") (pinfunction "B9_69") (pintype "passive"))
      (node (ref "J6") (pin "7") (pinfunction "A7_7") (pintype "passive"))
      (node (ref "J6") (pin "70") (pinfunction "B10_70") (pintype "passive"))
      (node (ref "J6") (pin "71") (pinfunction "B11_71") (pintype "passive"))
      (node (ref "J6") (pin "72") (pinfunction "B12_72") (pintype "passive"))
      (node (ref "J6") (pin "8") (pinfunction "A8_8") (pintype "passive"))
      (node (ref "J6") (pin "81") (pinfunction "B21_81") (pintype "passive"))
      (node (ref "J6") (pin "9") (pinfunction "A9_9") (pintype "passive"))
      (node (ref "J6") (pin "90") (pinfunction "B30_90") (pintype "passive"))
      (node (ref "J6") (pin "99") (pinfunction "B39_99") (pintype "passive"))
      (node (ref "J7") (pin "10") (pinfunction "A10_10") (pintype "passive"))
      (node (ref "J7") (pin "108") (pinfunction "B48_108") (pintype "passive"))
      (node (ref "J7") (pin "11") (pinfunction "A11_11") (pintype "passive"))
      (node (ref "J7") (pin "117") (pinfunction "B57_117") (pintype "passive"))
      (node (ref "J7") (pin "119") (pinfunction "B59_119") (pintype "passive"))
      (node (ref "J7") (pin "12") (pinfunction "A12_12") (pintype "passive"))
      (node (ref "J7") (pin "2") (pinfunction "A2_2") (pintype "passive"))
      (node (ref "J7") (pin "21") (pinfunction "A21_21") (pintype "passive"))
      (node (ref "J7") (pin "3") (pinfunction "A3_3") (pintype "passive"))
      (node (ref "J7") (pin "30") (pinfunction "A30_30") (pintype "passive"))
      (node (ref "J7") (pin "39") (pinfunction "A39_39") (pintype "passive"))
      (node (ref "J7") (pin "4") (pinfunction "A4_4") (pintype "passive"))
      (node (ref "J7") (pin "48") (pinfunction "A48_48") (pintype "passive"))
      (node (ref "J7") (pin "5") (pinfunction "A5_5") (pintype "passive"))
      (node (ref "J7") (pin "57") (pinfunction "A57_57") (pintype "passive"))
      (node (ref "J7") (pin "59") (pinfunction "A59_59") (pintype "passive"))
      (node (ref "J7") (pin "6") (pinfunction "A6_6") (pintype "passive"))
      (node (ref "J7") (pin "62") (pinfunction "B2_62") (pintype "passive"))
      (node (ref "J7") (pin "63") (pinfunction "B3_63") (pintype "passive"))
      (node (ref "J7") (pin "64") (pinfunction "B4_64") (pintype "passive"))
      (node (ref "J7") (pin "65") (pinfunction "B5_65") (pintype "passive"))
      (node (ref "J7") (pin "66") (pinfunction "B6_66") (pintype "passive"))
      (node (ref "J7") (pin "67") (pinfunction "B7_67") (pintype "passive"))
      (node (ref "J7") (pin "68") (pinfunction "B8_68") (pintype "passive"))
      (node (ref "J7") (pin "69") (pinfunction "B9_69") (pintype "passive"))
      (node (ref "J7") (pin "7") (pinfunction "A7_7") (pintype "passive"))
      (node (ref "J7") (pin "70") (pinfunction "B10_70") (pintype "passive"))
      (node (ref "J7") (pin "71") (pinfunction "B11_71") (pintype "passive"))
      (node (ref "J7") (pin "72") (pinfunction "B12_72") (pintype "passive"))
      (node (ref "J7") (pin "8") (pinfunction "A8_8") (pintype "passive"))
      (node (ref "J7") (pin "81") (pinfunction "B21_81") (pintype "passive"))
      (node (ref "J7") (pin "9") (pinfunction "A9_9") (pintype "passive"))
      (node (ref "J7") (pin "90") (pinfunction "B30_90") (pintype "passive"))
      (node (ref "J7") (pin "99") (pinfunction "B39_99") (pintype "passive"))
      (node (ref "J8") (pin "10") (pinfunction "A10_10") (pintype "passive"))
      (node (ref "J8") (pin "108") (pinfunction "B48_108") (pintype "passive"))
      (node (ref "J8") (pin "11") (pinfunction "A11_11") (pintype "passive"))
      (node (ref "J8") (pin "117") (pinfunction "B57_117") (pintype "passive"))
      (node (ref "J8") (pin "119") (pinfunction "B59_119") (pintype "passive"))
      (node (ref "J8") (pin "12") (pinfunction "A12_12") (pintype "passive"))
      (node (ref "J8") (pin "2") (pinfunction "A2_2") (pintype "passive"))
      (node (ref "J8") (pin "21") (pinfunction "A21_21") (pintype "passive"))
      (node (ref "J8") (pin "3") (pinfunction "A3_3") (pintype "passive"))
      (node (ref "J8") (pin "30") (pinfunction "A30_30") (pintype "passive"))
      (node (ref "J8") (pin "39") (pinfunction "A39_39") (pintype "passive"))
      (node (ref "J8") (pin "4") (pinfunction "A4_4") (pintype "passive"))
      (node (ref "J8") (pin "48") (pinfunction "A48_48") (pintype "passive"))
      (node (ref "J8") (pin "5") (pinfunction "A5_5") (pintype "passive"))
      (node (ref "J8") (pin "57") (pinfunction "A57_57") (pintype "passive"))
      (node (ref "J8") (pin "59") (pinfunction "A59_59") (pintype "passive"))
      (node (ref "J8") (pin "6") (pinfunction "A6_6") (pintype "passive"))
      (node (ref "J8") (pin "62") (pinfunction "B2_62") (pintype "passive"))
      (node (ref "J8") (pin "63") (pinfunction "B3_63") (pintype "passive"))
      (node (ref "J8") (pin "64") (pinfunction "B4_64") (pintype "passive"))
      (node (ref "J8") (pin "65") (pinfunction "B5_65") (pintype "passive"))
      (node (ref "J8") (pin "66") (pinfunction "B6_66") (pintype "passive"))
      (node (ref "J8") (pin "67") (pinfunction "B7_67") (pintype "passive"))
      (node (ref "J8") (pin "68") (pinfunction "B8_68") (pintype "passive"))
      (node (ref "J8") (pin "69") (pinfunction "B9_69") (pintype "passive"))
      (node (ref "J8") (pin "7") (pinfunction "A7_7") (pintype "passive"))
      (node (ref "J8") (pin "70") (pinfunction "B10_70") (pintype "passive"))
      (node (ref "J8") (pin "71") (pinfunction "B11_71") (pintype "passive"))
      (node (ref "J8") (pin "72") (pinfunction "B12_72") (pintype "passive"))
      (node (ref "J8") (pin "8") (pinfunction "A8_8") (pintype "passive"))
      (node (ref "J8") (pin "81") (pinfunction "B21_81") (pintype "passive"))
      (node (ref "J8") (pin "9") (pinfunction "A9_9") (pintype "passive"))
      (node (ref "J8") (pin "90") (pinfunction "B30_90") (pintype "passive"))
      (node (ref "J8") (pin "99") (pinfunction "B39_99") (pintype "passive"))
      (node (ref "J9") (pin "10") (pinfunction "A10_10") (pintype "passive"))
      (node (ref "J9") (pin "108") (pinfunction "B48_108") (pintype "passive"))
      (node (ref "J9") (pin "11") (pinfunction "A11_11") (pintype "passive"))
      (node (ref "J9") (pin "117") (pinfunction "B57_117") (pintype "passive"))
      (node (ref "J9") (pin "119") (pinfunction "B59_119") (pintype "passive"))
      (node (ref "J9") (pin "12") (pinfunction "A12_12") (pintype "passive"))
      (node (ref "J9") (pin "2") (pinfunction "A2_2") (pintype "passive"))
      (node (ref "J9") (pin "21") (pinfunction "A21_21") (pintype "passive"))
      (node (ref "J9") (pin "3") (pinfunction "A3_3") (pintype "passive"))
      (node (ref "J9") (pin "30") (pinfunction "A30_30") (pintype "passive"))
      (node (ref "J9") (pin "39") (pinfunction "A39_39") (pintype "passive"))
      (node (ref "J9") (pin "4") (pinfunction "A4_4") (pintype "passive"))
      (node (ref "J9") (pin "48") (pinfunction "A48_48") (pintype "passive"))
      (node (ref "J9") (pin "5") (pinfunction "A5_5") (pintype "passive"))
      (node (ref "J9") (pin "57") (pinfunction "A57_57") (pintype "passive"))
      (node (ref "J9") (pin "59") (pinfunction "A59_59") (pintype "passive"))
      (node (ref "J9") (pin "6") (pinfunction "A6_6") (pintype "passive"))
      (node (ref "J9") (pin "62") (pinfunction "B2_62") (pintype "passive"))
      (node (ref "J9") (pin "63") (pinfunction "B3_63") (pintype "passive"))
      (node (ref "J9") (pin "64") (pinfunction "B4_64") (pintype "passive"))
      (node (ref "J9") (pin "65") (pinfunction "B5_65") (pintype "passive"))
      (node (ref "J9") (pin "66") (pinfunction "B6_66") (pintype "passive"))
      (node (ref "J9") (pin "67") (pinfunction "B7_67") (pintype "passive"))
      (node (ref "J9") (pin "68") (pinfunction "B8_68") (pintype "passive"))
      (node (ref "J9") (pin "69") (pinfunction "B9_69") (pintype "passive"))
      (node (ref "J9") (pin "7") (pinfunction "A7_7") (pintype "passive"))
      (node (ref "J9") (pin "70") (pinfunction "B10_70") (pintype "passive"))
      (node (ref "J9") (pin "71") (pinfunction "B11_71") (pintype "passive"))
      (node (ref "J9") (pin "72") (pinfunction "B12_72") (pintype "passive"))
      (node (ref "J9") (pin "8") (pinfunction "A8_8") (pintype "passive"))
      (node (ref "J9") (pin "81") (pinfunction "B21_81") (pintype "passive"))
      (node (ref "J9") (pin "9") (pinfunction "A9_9") (pintype "passive"))
      (node (ref "J9") (pin "90") (pinfunction "B30_90") (pintype "passive"))
      (node (ref "J9") (pin "99") (pinfunction "B39_99") (pintype "passive"))
      (node (ref "P1") (pin "2") (pinfunction "Y_2") (pintype "passive"))
      (node (ref "P10") (pin "15") (pinfunction "15_15") (pintype "passive"))
      (node (ref "P10") (pin "38") (pinfunction "38_38") (pintype "passive"))
      (node (ref "P10") (pin "40") (pinfunction "40_40") (pintype "passive"))
      (node (ref "P2") (pin "2") (pinfunction "Y_2") (pintype "passive"))
      (node (ref "P3") (pin "2") (pinfunction "Y_2") (pintype "passive"))
      (node (ref "P4") (pin "2") (pinfunction "Y_2") (pintype "passive"))
      (node (ref "P5") (pin "1") (pinfunction "1_1") (pintype "passive"))
      (node (ref "P5") (pin "40") (pinfunction "40_40") (pintype "passive"))
      (node (ref "P6") (pin "1") (pinfunction "1_1") (pintype "passive"))
      (node (ref "P6") (pin "20") (pinfunction "20_20") (pintype "passive"))
      (node (ref "P7") (pin "1") (pinfunction "1_1") (pintype "passive"))
      (node (ref "P7") (pin "13") (pinfunction "13_13") (pintype "passive"))
      (node (ref "P7") (pin "14") (pinfunction "14_14") (pintype "passive"))
      (node (ref "P7") (pin "36") (pinfunction "36_36") (pintype "passive"))
      (node (ref "P8") (pin "14") (pinfunction "14_14") (pintype "passive"))
      (node (ref "P8") (pin "2") (pinfunction "2_2") (pintype "passive"))
      (node (ref "P8") (pin "35") (pinfunction "35_35") (pintype "passive"))
      (node (ref "P9") (pin "16") (pinfunction "16_16") (pintype "passive"))
      (node (ref "P9") (pin "38") (pinfunction "38_38") (pintype "passive"))
      (node (ref "P9") (pin "40") (pinfunction "40_40") (pintype "passive"))
      (node (ref "R41") (pin "1") (pinfunction "1_1") (pintype "passive"))
      (node (ref "R42") (pin "1") (pinfunction "1_1") (pintype "passive"))
      (node (ref "R43") (pin "1") (pinfunction "1_1") (pintype "passive"))
      (node (ref "R44") (pin "1") (pinfunction "1_1") (pintype "passive"))
      (node (ref "R45") (pin "1") (pinfunction "1_1") (pintype "passive"))
      (node (ref "R46") (pin "1") (pinfunction "1_1") (pintype "passive"))
      (node (ref "R47") (pin "1") (pinfunction "1_1") (pintype "passive"))
      (node (ref "R48") (pin "1") (pinfunction "1_1") (pintype "passive"))
      (node (ref "U1") (pin "8") (pinfunction "GND_8") (pintype "passive"))
      (node (ref "U10") (pin "12") (pinfunction "EN#_12") (pintype "passive"))
      (node (ref "U10") (pin "8") (pinfunction "GND_8") (pintype "passive"))
      (node (ref "U11") (pin "1A2") (pinfunction "GND_1A2") (pintype "passive"))
      (node (ref "U11") (pin "1B2") (pinfunction "GND_1B2") (pintype "passive"))
      (node (ref "U11") (pin "1B39") (pinfunction "GND_1B39") (pintype "passive"))
      (node (ref "U11") (pin "1C2") (pinfunction "GND_1C2") (pintype "passive"))
      (node (ref "U11") (pin "1C39") (pinfunction "GND_1C39") (pintype "passive"))
      (node (ref "U11") (pin "2A2") (pinfunction "GND_2A2") (pintype "passive"))
      (node (ref "U11") (pin "2A39") (pinfunction "GND_2A39") (pintype "passive"))
      (node (ref "U11") (pin "2B2") (pinfunction "GND_2B2") (pintype "passive"))
      (node (ref "U11") (pin "2B39") (pinfunction "GND_2B39") (pintype "passive"))
      (node (ref "U11") (pin "2C2") (pinfunction "GND_2C2") (pintype "passive"))
      (node (ref "U11") (pin "2C39") (pinfunction "GND_2C39") (pintype "passive"))
      (node (ref "U12") (pin "2") (pinfunction "GND_2") (pintype "passive"))
      (node (ref "U13") (pin "2") (pinfunction "GND_2") (pintype "passive"))
      (node (ref "U14") (pin "2") (pinfunction "GND_2") (pintype "passive"))
      (node (ref "U15") (pin "2") (pinfunction "GND_2") (pintype "passive"))
      (node (ref "U2") (pin "8") (pinfunction "GND_8") (pintype "passive"))
      (node (ref "U3") (pin "12") (pinfunction "EN#_12") (pintype "passive"))
      (node (ref "U3") (pin "8") (pinfunction "GND_8") (pintype "passive"))
      (node (ref "U4") (pin "12") (pinfunction "EN#_12") (pintype "passive"))
      (node (ref "U4") (pin "8") (pinfunction "GND_8") (pintype "passive"))
      (node (ref "U5") (pin "12") (pinfunction "EN#_12") (pintype "passive"))
      (node (ref "U5") (pin "8") (pinfunction "GND_8") (pintype "passive"))
      (node (ref "U6") (pin "12") (pinfunction "EN#_12") (pintype "passive"))
      (node (ref "U6") (pin "8") (pinfunction "GND_8") (pintype "passive"))
      (node (ref "U7") (pin "12") (pinfunction "EN#_12") (pintype "passive"))
      (node (ref "U7") (pin "8") (pinfunction "GND_8") (pintype "passive"))
      (node (ref "U8") (pin "12") (pinfunction "EN#_12") (pintype "passive"))
      (node (ref "U8") (pin "8") (pinfunction "GND_8") (pintype "passive"))
      (node (ref "U9") (pin "12") (pinfunction "EN#_12") (pintype "passive"))
      (node (ref "U9") (pin "8") (pinfunction "GND_8") (pintype "passive"))
    )
    (net (code "192") (name "Net-(D1-K)") (class "Default")
      (node (ref "D1") (pin "2") (pinfunction "K_2") (pintype "passive"))
      (node (ref "R41") (pin "2") (pinfunction "2_2") (pintype "passive"))
    )
    (net (code "193") (name "Net-(D2-K)") (class "Default")
      (node (ref "D2") (pin "2") (pinfunction "K_2") (pintype "passive"))
      (node (ref "R42") (pin "2") (pinfunction "2_2") (pintype "passive"))
    )
    (net (code "194") (name "Net-(D3-K)") (class "Default")
      (node (ref "D3") (pin "2") (pinfunction "K_2") (pintype "passive"))
      (node (ref "R43") (pin "2") (pinfunction "2_2") (pintype "passive"))
    )
    (net (code "195") (name "Net-(D4-K)") (class "Default")
      (node (ref "D4") (pin "2") (pinfunction "K_2") (pintype "passive"))
      (node (ref "R44") (pin "2") (pinfunction "2_2") (pintype "passive"))
    )
    (net (code "196") (name "Net-(D5-K)") (class "Default")
      (node (ref "D5") (pin "2") (pinfunction "K_2") (pintype "passive"))
      (node (ref "R45") (pin "2") (pinfunction "2_2") (pintype "passive"))
    )
    (net (code "197") (name "Net-(D6-K)") (class "Default")
      (node (ref "D6") (pin "2") (pinfunction "K_2") (pintype "passive"))
      (node (ref "R46") (pin "2") (pinfunction "2_2") (pintype "passive"))
    )
    (net (code "198") (name "Net-(D7-K)") (class "Default")
      (node (ref "D7") (pin "2") (pinfunction "K_2") (pintype "passive"))
      (node (ref "R47") (pin "2") (pinfunction "2_2") (pintype "passive"))
    )
    (net (code "199") (name "Net-(D8-K)") (class "Default")
      (node (ref "D8") (pin "2") (pinfunction "K_2") (pintype "passive"))
      (node (ref "R48") (pin "2") (pinfunction "2_2") (pintype "passive"))
    )
    (net (code "200") (name "Net-(P1-X)") (class "Default")
      (node (ref "P1") (pin "1") (pinfunction "X_1") (pintype "passive"))
      (node (ref "U12") (pin "3") (pinfunction "A_3") (pintype "passive"))
    )
    (net (code "201") (name "Net-(P2-X)") (class "Default")
      (node (ref "P2") (pin "1") (pinfunction "X_1") (pintype "passive"))
      (node (ref "U13") (pin "3") (pinfunction "A_3") (pintype "passive"))
    )
    (net (code "202") (name "Net-(P3-X)") (class "Default")
      (node (ref "P3") (pin "1") (pinfunction "X_1") (pintype "passive"))
      (node (ref "U14") (pin "3") (pinfunction "A_3") (pintype "passive"))
    )
    (net (code "203") (name "Net-(P4-X)") (class "Default")
      (node (ref "P4") (pin "1") (pinfunction "X_1") (pintype "passive"))
      (node (ref "U15") (pin "3") (pinfunction "A_3") (pintype "passive"))
    )
    (net (code "204") (name "unconnected-(P5-Pad38)") (class "Default")
      (node (ref "P5") (pin "38") (pinfunction "38_38") (pintype "passive"))
    )
    (net (code "205") (name "unconnected-(P5-Pad39)") (class "Default")
      (node (ref "P5") (pin "39") (pinfunction "39_39") (pintype "passive"))
    )
    (net (code "206") (name "unconnected-(P7-Pad3)") (class "Default")
      (node (ref "P7") (pin "3") (pinfunction "3_3") (pintype "passive"))
    )
    (net (code "207") (name "unconnected-(P7-Pad5)") (class "Default")
      (node (ref "P7") (pin "5") (pinfunction "5_5") (pintype "passive"))
    )
    (net (code "208") (name "unconnected-(P7-Pad7)") (class "Default")
      (node (ref "P7") (pin "7") (pinfunction "7_7") (pintype "passive"))
    )
    (net (code "209") (name "unconnected-(P7-Pad8)") (class "Default")
      (node (ref "P7") (pin "8") (pinfunction "8_8") (pintype "passive"))
    )
    (net (code "210") (name "unconnected-(P7-Pad9)") (class "Default")
      (node (ref "P7") (pin "9") (pinfunction "9_9") (pintype "passive"))
    )
    (net (code "211") (name "unconnected-(P7-Pad10)") (class "Default")
      (node (ref "P7") (pin "10") (pinfunction "10_10") (pintype "passive"))
    )
    (net (code "212") (name "unconnected-(P7-Pad11)") (class "Default")
      (node (ref "P7") (pin "11") (pinfunction "11_11") (pintype "passive"))
    )
    (net (code "213") (name "unconnected-(P7-Pad12)") (class "Default")
      (node (ref "P7") (pin "12") (pinfunction "12_12") (pintype "passive"))
    )
    (net (code "214") (name "unconnected-(P7-Pad21)") (class "Default")
      (node (ref "P7") (pin "21") (pinfunction "21_21") (pintype "passive"))
    )
    (net (code "215") (name "unconnected-(P7-Pad22)") (class "Default")
      (node (ref "P7") (pin "22") (pinfunction "22_22") (pintype "passive"))
    )
    (net (code "216") (name "unconnected-(P7-Pad23)") (class "Default")
      (node (ref "P7") (pin "23") (pinfunction "23_23") (pintype "passive"))
    )
    (net (code "217") (name "unconnected-(P7-Pad24)") (class "Default")
      (node (ref "P7") (pin "24") (pinfunction "24_24") (pintype "passive"))
    )
    (net (code "218") (name "unconnected-(P7-Pad35)") (class "Default")
      (node (ref "P7") (pin "35") (pinfunction "35_35") (pintype "passive"))
    )
    (net (code "219") (name "unconnected-(P7-Pad37)") (class "Default")
      (node (ref "P7") (pin "37") (pinfunction "37_37") (pintype "passive"))
    )
    (net (code "220") (name "unconnected-(P7-Pad38)") (class "Default")
      (node (ref "P7") (pin "38") (pinfunction "38_38") (pintype "passive"))
    )
    (net (code "221") (name "unconnected-(P7-Pad39)") (class "Default")
      (node (ref "P7") (pin "39") (pinfunction "39_39") (pintype "passive"))
    )
    (net (code "222") (name "unconnected-(P7-Pad40)") (class "Default")
      (node (ref "P7") (pin "40") (pinfunction "40_40") (pintype "passive"))
    )
    (net (code "223") (name "unconnected-(P8-Pad1)") (class "Default")
      (node (ref "P8") (pin "1") (pinfunction "1_1") (pintype "passive"))
    )
    (net (code "224") (name "unconnected-(P8-Pad3)") (class "Default")
      (node (ref "P8") (pin "3") (pinfunction "3_3") (pintype "passive"))
    )
    (net (code "225") (name "unconnected-(P8-Pad4)") (class "Default")
      (node (ref "P8") (pin "4") (pinfunction "4_4") (pintype "passive"))
    )
    (net (code "226") (name "unconnected-(P8-Pad5)") (class "Default")
      (node (ref "P8") (pin "5") (pinfunction "5_5") (pintype "passive"))
    )
    (net (code "227") (name "unconnected-(P8-Pad6)") (class "Default")
      (node (ref "P8") (pin "6") (pinfunction "6_6") (pintype "passive"))
    )
    (net (code "228") (name "unconnected-(P8-Pad7)") (class "Default")
      (node (ref "P8") (pin "7") (pinfunction "7_7") (pintype "passive"))
    )
    (net (code "229") (name "unconnected-(P8-Pad8)") (class "Default")
      (node (ref "P8") (pin "8") (pinfunction "8_8") (pintype "passive"))
    )
    (net (code "230") (name "unconnected-(P8-Pad9)") (class "Default")
      (node (ref "P8") (pin "9") (pinfunction "9_9") (pintype "passive"))
    )
    (net (code "231") (name "unconnected-(P8-Pad10)") (class "Default")
      (node (ref "P8") (pin "10") (pinfunction "10_10") (pintype "passive"))
    )
    (net (code "232") (name "unconnected-(P8-Pad11)") (class "Default")
      (node (ref "P8") (pin "11") (pinfunction "11_11") (pintype "passive"))
    )
    (net (code "233") (name "unconnected-(P8-Pad12)") (class "Default")
      (node (ref "P8") (pin "12") (pinfunction "12_12") (pintype "passive"))
    )
    (net (code "234") (name "unconnected-(P8-Pad13)") (class "Default")
      (node (ref "P8") (pin "13") (pinfunction "13_13") (pintype "passive"))
    )
    (net (code "235") (name "unconnected-(P8-Pad15)") (class "Default")
      (node (ref "P8") (pin "15") (pinfunction "15_15") (pintype "passive"))
    )
    (net (code "236") (name "unconnected-(P8-Pad16)") (class "Default")
      (node (ref "P8") (pin "16") (pinfunction "16_16") (pintype "passive"))
    )
    (net (code "237") (name "unconnected-(P8-Pad17)") (class "Default")
      (node (ref "P8") (pin "17") (pinfunction "17_17") (pintype "passive"))
    )
    (net (code "238") (name "unconnected-(P8-Pad18)") (class "Default")
      (node (ref "P8") (pin "18") (pinfunction "18_18") (pintype "passive"))
    )
    (net (code "239") (name "unconnected-(P8-Pad36)") (class "Default")
      (node (ref "P8") (pin "36") (pinfunction "36_36") (pintype "passive"))
    )
    (net (code "240") (name "unconnected-(P8-Pad39)") (class "Default")
      (node (ref "P8") (pin "39") (pinfunction "39_39") (pintype "passive"))
    )
    (net (code "241") (name "unconnected-(P8-Pad40)") (class "Default")
      (node (ref "P8") (pin "40") (pinfunction "40_40") (pintype "passive"))
    )
    (net (code "242") (name "unconnected-(P9-Pad15)") (class "Default")
      (node (ref "P9") (pin "15") (pinfunction "15_15") (pintype "passive"))
    )
    (net (code "243") (name "unconnected-(P9-Pad27)") (class "Default")
      (node (ref "P9") (pin "27") (pinfunction "27_27") (pintype "passive"))
    )
    (net (code "244") (name "unconnected-(P9-Pad28)") (class "Default")
      (node (ref "P9") (pin "28") (pinfunction "28_28") (pintype "passive"))
    )
    (net (code "245") (name "unconnected-(P9-Pad29)") (class "Default")
      (node (ref "P9") (pin "29") (pinfunction "29_29") (pintype "passive"))
    )
    (net (code "246") (name "unconnected-(P9-Pad30)") (class "Default")
      (node (ref "P9") (pin "30") (pinfunction "30_30") (pintype "passive"))
    )
    (net (code "247") (name "unconnected-(P9-Pad31)") (class "Default")
      (node (ref "P9") (pin "31") (pinfunction "31_31") (pintype "passive"))
    )
    (net (code "248") (name "unconnected-(P9-Pad33)") (class "Default")
      (node (ref "P9") (pin "33") (pinfunction "33_33") (pintype "passive"))
    )
    (net (code "249") (name "unconnected-(P9-Pad35)") (class "Default")
      (node (ref "P9") (pin "35") (pinfunction "35_35") (pintype "passive"))
    )
    (net (code "250") (name "unconnected-(P9-Pad39)") (class "Default")
      (node (ref "P9") (pin "39") (pinfunction "39_39") (pintype "passive"))
    )
    (net (code "251") (name "unconnected-(P10-Pad16)") (class "Default")
      (node (ref "P10") (pin "16") (pinfunction "16_16") (pintype "passive"))
    )
    (net (code "252") (name "unconnected-(P10-Pad37)") (class "Default")
      (node (ref "P10") (pin "37") (pinfunction "37_37") (pintype "passive"))
    )
    (net (code "253") (name "unconnected-(P10-Pad39)") (class "Default")
      (node (ref "P10") (pin "39") (pinfunction "39_39") (pintype "passive"))
    )
    (net (code "254") (name "unconnected-(U11-1.2V-Pad1A4)") (class "Default")
      (node (ref "U11") (pin "1A4") (pinfunction "1.2V_1A4") (pintype "passive"))
    )
    (net (code "255") (name "unconnected-(U11-1.8V-Pad1A6)") (class "Default")
      (node (ref "U11") (pin "1A6") (pinfunction "1.8V_1A6") (pintype "passive"))
    )
    (net (code "256") (name "unconnected-(U11-2.5V-Pad2A18)") (class "Default")
      (node (ref "U11") (pin "2A18") (pinfunction "2.5V_2A18") (pintype "passive"))
    )
    (net (code "257") (name "unconnected-(U11-3.3V-Pad1B1)") (class "Default")
      (node (ref "U11") (pin "1B1") (pinfunction "3.3V_1B1") (pintype "passive"))
    )
    (net (code "258") (name "unconnected-(U11-3.3V-Pad2A1)") (class "Default")
      (node (ref "U11") (pin "2A1") (pinfunction "3.3V_2A1") (pintype "passive"))
    )
    (net (code "259") (name "unconnected-(U11-3.3V-Pad2B1)") (class "Default")
      (node (ref "U11") (pin "2B1") (pinfunction "3.3V_2B1") (pintype "passive"))
    )
    (net (code "260") (name "unconnected-(U11-3.3V-Pad2C1)") (class "Default")
      (node (ref "U11") (pin "2C1") (pinfunction "3.3V_2C1") (pintype "passive"))
    )
    (net (code "261") (name "unconnected-(U11-AA1{slash}L31n-Pad1B32)") (class "Default")
      (node (ref "U11") (pin "1B32") (pinfunction "AA1/L31n_1B32") (pintype "passive"))
    )
    (net (code "262") (name "unconnected-(U11-AA3{slash}CLKOUT-Pad1A19)") (class "Default")
      (node (ref "U11") (pin "1A19") (pinfunction "AA3/CLKOUT_1A19") (pintype "passive"))
    )
    (net (code "263") (name "unconnected-(U11-AA13{slash}B23p-Pad2A32)") (class "Default")
      (node (ref "U11") (pin "2A32") (pinfunction "AA13/B23p_2A32") (pintype "passive"))
    )
    (net (code "264") (name "unconnected-(U11-AB3{slash}CLKOUT-Pad1A21)") (class "Default")
      (node (ref "U11") (pin "1A21") (pinfunction "AB3/CLKOUT_1A21") (pintype "passive"))
    )
    (net (code "265") (name "unconnected-(U11-AB13{slash}B23n-Pad2A34)") (class "Default")
      (node (ref "U11") (pin "2A34") (pinfunction "AB13/B23n_2A34") (pintype "passive"))
    )
    (net (code "266") (name "unconnected-(U11-AB18{slash}IO-Pad2A30)") (class "Default")
      (node (ref "U11") (pin "2A30") (pinfunction "AB18/IO_2A30") (pintype "passive"))
    )
    (net (code "267") (name "unconnected-(U11-B11{slash}CLKIN-Pad1A13)") (class "Default")
      (node (ref "U11") (pin "1A13") (pinfunction "B11/CLKIN_1A13") (pintype "passive"))
    )
    (net (code "268") (name "unconnected-(U11-B21{slash}R3p-Pad2C23)") (class "Default")
      (node (ref "U11") (pin "2C23") (pinfunction "B21/R3p_2C23") (pintype "passive"))
    )
    (net (code "269") (name "unconnected-(U11-B22{slash}R3n-Pad2C25)") (class "Default")
      (node (ref "U11") (pin "2C25") (pinfunction "B22/R3n_2C25") (pintype "passive"))
    )
    (net (code "270") (name "unconnected-(U11-C20{slash}R2n-Pad2C29)") (class "Default")
      (node (ref "U11") (pin "2C29") (pinfunction "C20/R2n_2C29") (pintype "passive"))
    )
    (net (code "271") (name "unconnected-(U11-C22{slash}R4n-Pad2C21)") (class "Default")
      (node (ref "U11") (pin "2C21") (pinfunction "C22/R4n_2C21") (pintype "passive"))
    )
    (net (code "272") (name "unconnected-(U11-CHARGE_DET-Pad2A17)") (class "Default")
      (node (ref "U11") (pin "2A17") (pinfunction "CHARGE_DET_2A17") (pintype "passive"))
    )
    (net (code "273") (name "unconnected-(U11-D20{slash}R2p-Pad2C27)") (class "Default")
      (node (ref "U11") (pin "2C27") (pinfunction "D20/R2p_2C27") (pintype "passive"))
    )
    (net (code "274") (name "unconnected-(U11-F17{slash}R1n-Pad2C33)") (class "Default")
      (node (ref "U11") (pin "2C33") (pinfunction "F17/R1n_2C33") (pintype "passive"))
    )
    (net (code "275") (name "unconnected-(U11-G17{slash}R1p-Pad2C31)") (class "Default")
      (node (ref "U11") (pin "2C31") (pinfunction "G17/R1p_2C31") (pintype "passive"))
    )
    (net (code "276") (name "unconnected-(U11-GND-Pad1A39)") (class "Default")
      (node (ref "U11") (pin "1A39") (pinfunction "GND_1A39") (pintype "passive"))
    )
    (net (code "277") (name "unconnected-(U11-HSMC_VS0-Pad1A10)") (class "Default")
      (node (ref "U11") (pin "1A10") (pinfunction "HSMC_VS0_1A10") (pintype "passive"))
    )
    (net (code "278") (name "unconnected-(U11-HSMC_VS0-Pad2A10)") (class "Default")
      (node (ref "U11") (pin "2A10") (pinfunction "HSMC_VS0_2A10") (pintype "passive"))
    )
    (net (code "279") (name "unconnected-(U11-HSMC_VS1-Pad1A12)") (class "Default")
      (node (ref "U11") (pin "1A12") (pinfunction "HSMC_VS1_1A12") (pintype "passive"))
    )
    (net (code "280") (name "unconnected-(U11-HSMC_VS1-Pad2A12)") (class "Default")
      (node (ref "U11") (pin "2A12") (pinfunction "HSMC_VS1_2A12") (pintype "passive"))
    )
    (net (code "281") (name "unconnected-(U11-HSMC_VS2-Pad1A14)") (class "Default")
      (node (ref "U11") (pin "1A14") (pinfunction "HSMC_VS2_1A14") (pintype "passive"))
    )
    (net (code "282") (name "unconnected-(U11-HSMC_VS2-Pad2A14)") (class "Default")
      (node (ref "U11") (pin "2A14") (pinfunction "HSMC_VS2_2A14") (pintype "passive"))
    )
    (net (code "283") (name "unconnected-(U11-J17{slash}IO-Pad2C38)") (class "Default")
      (node (ref "U11") (pin "2C38") (pinfunction "J17/IO_2C38") (pintype "passive"))
    )
    (net (code "284") (name "unconnected-(U11-J18{slash}R12n-Pad2C36)") (class "Default")
      (node (ref "U11") (pin "2C36") (pinfunction "J18/R12n_2C36") (pintype "passive"))
    )
    (net (code "285") (name "unconnected-(U11-J19{slash}R10p-Pad2A35)") (class "Default")
      (node (ref "U11") (pin "2A35") (pinfunction "J19/R10p_2A35") (pintype "passive"))
    )
    (net (code "286") (name "unconnected-(U11-J20{slash}R10n-Pad2A37)") (class "Default")
      (node (ref "U11") (pin "2A37") (pinfunction "J20/R10n_2A37") (pintype "passive"))
    )
    (net (code "287") (name "unconnected-(U11-JTAG_TCK-Pad1A25)") (class "Default")
      (node (ref "U11") (pin "1A25") (pinfunction "JTAG_TCK_1A25") (pintype "passive"))
    )
    (net (code "288") (name "unconnected-(U11-JTAG_TCK-Pad2A25)") (class "Default")
      (node (ref "U11") (pin "2A25") (pinfunction "JTAG_TCK_2A25") (pintype "passive"))
    )
    (net (code "289") (name "unconnected-(U11-JTAG_TDI-Pad1A24)") (class "Default")
      (node (ref "U11") (pin "1A24") (pinfunction "JTAG_TDI_1A24") (pintype "passive"))
    )
    (net (code "290") (name "unconnected-(U11-JTAG_TDI-Pad2A24)") (class "Default")
      (node (ref "U11") (pin "2A24") (pinfunction "JTAG_TDI_2A24") (pintype "passive"))
    )
    (net (code "291") (name "unconnected-(U11-JTAG_TDO-Pad1A27)") (class "Default")
      (node (ref "U11") (pin "1A27") (pinfunction "JTAG_TDO_1A27") (pintype "passive"))
    )
    (net (code "292") (name "unconnected-(U11-JTAG_TDO-Pad2A27)") (class "Default")
      (node (ref "U11") (pin "2A27") (pinfunction "JTAG_TDO_2A27") (pintype "passive"))
    )
    (net (code "293") (name "unconnected-(U11-JTAG_TMC-Pad1A22)") (class "Default")
      (node (ref "U11") (pin "1A22") (pinfunction "JTAG_TMC_1A22") (pintype "passive"))
    )
    (net (code "294") (name "unconnected-(U11-JTAG_TMC-Pad2A22)") (class "Default")
      (node (ref "U11") (pin "2A22") (pinfunction "JTAG_TMC_2A22") (pintype "passive"))
    )
    (net (code "295") (name "unconnected-(U11-K21{slash}R16p-Pad2C35)") (class "Default")
      (node (ref "U11") (pin "2C35") (pinfunction "K21/R16p_2C35") (pintype "passive"))
    )
    (net (code "296") (name "unconnected-(U11-K22{slash}R16n-Pad2C37)") (class "Default")
      (node (ref "U11") (pin "2C37") (pinfunction "K22/R16n_2C37") (pintype "passive"))
    )
    (net (code "297") (name "unconnected-(U11-N5{slash}L22n-Pad1C36)") (class "Default")
      (node (ref "U11") (pin "1C36") (pinfunction "N5/L22n_1C36") (pintype "passive"))
    )
    (net (code "298") (name "unconnected-(U11-N7{slash}L30p-Pad1C15)") (class "Default")
      (node (ref "U11") (pin "1C15") (pinfunction "N7/L30p_1C15") (pintype "passive"))
    )
    (net (code "299") (name "unconnected-(U11-N17{slash}R21n-Pad2C26)") (class "Default")
      (node (ref "U11") (pin "2C26") (pinfunction "N17/R21n_2C26") (pintype "passive"))
    )
    (net (code "300") (name "unconnected-(U11-N18{slash}R21p-Pad2C24)") (class "Default")
      (node (ref "U11") (pin "2C24") (pinfunction "N18/R21p_2C24") (pintype "passive"))
    )
    (net (code "301") (name "unconnected-(U11-N20{slash}R22n-Pad2C22)") (class "Default")
      (node (ref "U11") (pin "2C22") (pinfunction "N20/R22n_2C22") (pintype "passive"))
    )
    (net (code "302") (name "unconnected-(U11-OVP_FLAG-Pad1A17)") (class "Default")
      (node (ref "U11") (pin "1A17") (pinfunction "OVP_FLAG_1A17") (pintype "passive"))
    )
    (net (code "303") (name "unconnected-(U11-P5{slash}L26p-Pad1C38)") (class "Default")
      (node (ref "U11") (pin "1C38") (pinfunction "P5/L26p_1C38") (pintype "passive"))
    )
    (net (code "304") (name "unconnected-(U11-P6{slash}L32p-Pad1C19)") (class "Default")
      (node (ref "U11") (pin "1C19") (pinfunction "P6/L32p_1C19") (pintype "passive"))
    )
    (net (code "305") (name "unconnected-(U11-P7{slash}L30n-Pad1C17)") (class "Default")
      (node (ref "U11") (pin "1C17") (pinfunction "P7/L30n_1C17") (pintype "passive"))
    )
    (net (code "306") (name "unconnected-(U11-Pad1A8)") (class "Default")
      (node (ref "U11") (pin "1A8") (pintype "passive"))
    )
    (net (code "307") (name "unconnected-(U11-Pad1A15)") (class "Default")
      (node (ref "U11") (pin "1A15") (pintype "passive"))
    )
    (net (code "308") (name "unconnected-(U11-Pad1A16)") (class "Default")
      (node (ref "U11") (pin "1A16") (pintype "passive"))
    )
    (net (code "309") (name "unconnected-(U11-Pad1A18)") (class "Default")
      (node (ref "U11") (pin "1A18") (pintype "passive"))
    )
    (net (code "310") (name "unconnected-(U11-Pad1A36)") (class "Default")
      (node (ref "U11") (pin "1A36") (pintype "passive"))
    )
    (net (code "311") (name "unconnected-(U11-Pad1A38)") (class "Default")
      (node (ref "U11") (pin "1A38") (pintype "passive"))
    )
    (net (code "312") (name "unconnected-(U11-R4{slash}L27p-Pad1C3)") (class "Default")
      (node (ref "U11") (pin "1C3") (pinfunction "R4/L27p_1C3") (pintype "passive"))
    )
    (net (code "313") (name "unconnected-(U11-R5{slash}L32n-Pad1C21)") (class "Default")
      (node (ref "U11") (pin "1C21") (pinfunction "R5/L32n_1C21") (pintype "passive"))
    )
    (net (code "314") (name "unconnected-(U11-R6{slash}L33n-Pad1C37)") (class "Default")
      (node (ref "U11") (pin "1C37") (pinfunction "R6/L33n_1C37") (pintype "passive"))
    )
    (net (code "315") (name "unconnected-(U11-R14{slash}B41p-Pad2C28)") (class "Default")
      (node (ref "U11") (pin "2C28") (pinfunction "R14/B41p_2C28") (pintype "passive"))
    )
    (net (code "316") (name "unconnected-(U11-R15{slash}B41n-Pad2C30)") (class "Default")
      (node (ref "U11") (pin "2C30") (pinfunction "R15/B41n_2C30") (pintype "passive"))
    )
    (net (code "317") (name "unconnected-(U11-R16{slash}IO{slash}CLKOUT-Pad2A21)") (class "Default")
      (node (ref "U11") (pin "2A21") (pinfunction "R16/IO/CLKOUT_2A21") (pintype "passive"))
    )
    (net (code "318") (name "unconnected-(U11-R17{slash}R30n-Pad1C22)") (class "Default")
      (node (ref "U11") (pin "1C22") (pinfunction "R17/R30n_1C22") (pintype "passive"))
    )
    (net (code "319") (name "unconnected-(U11-R18{slash}R26n-Pad1B33)") (class "Default")
      (node (ref "U11") (pin "1B33") (pinfunction "R18/R26n_1B33") (pintype "passive"))
    )
    (net (code "320") (name "unconnected-(U11-T5{slash}L33p-Pad1C35)") (class "Default")
      (node (ref "U11") (pin "1C35") (pinfunction "T5/L33p_1C35") (pintype "passive"))
    )
    (net (code "321") (name "unconnected-(U11-T10{slash}B13p-Pad1B36)") (class "Default")
      (node (ref "U11") (pin "1B36") (pinfunction "T10/B13p_1B36") (pintype "passive"))
    )
    (net (code "322") (name "unconnected-(U11-T11{slash}B13n-Pad1B38)") (class "Default")
      (node (ref "U11") (pin "1B38") (pinfunction "T11/B13n_1B38") (pintype "passive"))
    )
    (net (code "323") (name "unconnected-(U11-T16{slash}IO{slash}CLKOUT-Pad2A19)") (class "Default")
      (node (ref "U11") (pin "2A19") (pinfunction "T16/IO/CLKOUT_2A19") (pintype "passive"))
    )
    (net (code "324") (name "unconnected-(U11-T19{slash}R31p-Pad1C24)") (class "Default")
      (node (ref "U11") (pin "1C24") (pinfunction "T19/R31p_1C24") (pintype "passive"))
    )
    (net (code "325") (name "unconnected-(U11-T20{slash}R31n-Pad1C26)") (class "Default")
      (node (ref "U11") (pin "1C26") (pinfunction "T20/R31n_1C26") (pintype "passive"))
    )
    (net (code "326") (name "unconnected-(U11-T21{slash}CLKIN-Pad1A26)") (class "Default")
      (node (ref "U11") (pin "1A26") (pinfunction "T21/CLKIN_1A26") (pintype "passive"))
    )
    (net (code "327") (name "unconnected-(U11-T22{slash}CLKIN-Pad2A26)") (class "Default")
      (node (ref "U11") (pin "2A26") (pinfunction "T22/CLKIN_2A26") (pintype "passive"))
    )
    (net (code "328") (name "unconnected-(U11-U11{slash}B19p-Pad1C12)") (class "Default")
      (node (ref "U11") (pin "1C12") (pinfunction "U11/B19p_1C12") (pintype "passive"))
    )
    (net (code "329") (name "unconnected-(U11-U12{slash}B28p-Pad2A31)") (class "Default")
      (node (ref "U11") (pin "2A31") (pinfunction "U12/B28p_2A31") (pintype "passive"))
    )
    (net (code "330") (name "unconnected-(U11-U13{slash}B32p-Pad2A28)") (class "Default")
      (node (ref "U11") (pin "2A28") (pinfunction "U13/B32p_2A28") (pintype "passive"))
    )
    (net (code "331") (name "unconnected-(U11-U15{slash}B34p-Pad2C32)") (class "Default")
      (node (ref "U11") (pin "2C32") (pinfunction "U15/B34p_2C32") (pintype "passive"))
    )
    (net (code "332") (name "unconnected-(U11-U19{slash}R34p-Pad1C23)") (class "Default")
      (node (ref "U11") (pin "1C23") (pinfunction "U19/R34p_1C23") (pintype "passive"))
    )
    (net (code "333") (name "unconnected-(U11-U20{slash}R34n-Pad1C25)") (class "Default")
      (node (ref "U11") (pin "1C25") (pinfunction "U20/R34n_1C25") (pintype "passive"))
    )
    (net (code "334") (name "unconnected-(U11-U21{slash}R27p-Pad1C32)") (class "Default")
      (node (ref "U11") (pin "1C32") (pinfunction "U21/R27p_1C32") (pintype "passive"))
    )
    (net (code "335") (name "unconnected-(U11-U22{slash}R27n-Pad1C34)") (class "Default")
      (node (ref "U11") (pin "1C34") (pinfunction "U22/R27n_1C34") (pintype "passive"))
    )
    (net (code "336") (name "unconnected-(U11-V1{slash}L25n-Pad1B37)") (class "Default")
      (node (ref "U11") (pin "1B37") (pinfunction "V1/L25n_1B37") (pintype "passive"))
    )
    (net (code "337") (name "unconnected-(U11-V2{slash}L25p-Pad1B35)") (class "Default")
      (node (ref "U11") (pin "1B35") (pinfunction "V2/L25p_1B35") (pintype "passive"))
    )
    (net (code "338") (name "unconnected-(U11-V11{slash}B19n-Pad1C14)") (class "Default")
      (node (ref "U11") (pin "1C14") (pinfunction "V11/B19n_1C14") (pintype "passive"))
    )
    (net (code "339") (name "unconnected-(U11-V13{slash}B31p-Pad2A29)") (class "Default")
      (node (ref "U11") (pin "2A29") (pinfunction "V13/B31p_2A29") (pintype "passive"))
    )
    (net (code "340") (name "unconnected-(U11-V15{slash}B43n-Pad2C34)") (class "Default")
      (node (ref "U11") (pin "2C34") (pinfunction "V15/B43n_2C34") (pintype "passive"))
    )
    (net (code "341") (name "unconnected-(U11-V21{slash}R29p-Pad1C28)") (class "Default")
      (node (ref "U11") (pin "1C28") (pinfunction "V21/R29p_1C28") (pintype "passive"))
    )
    (net (code "342") (name "unconnected-(U11-V22{slash}R29n-Pad1C30)") (class "Default")
      (node (ref "U11") (pin "1C30") (pinfunction "V22/R29n_1C30") (pintype "passive"))
    )
    (net (code "343") (name "unconnected-(U11-VCCIO-Pad1A3)") (class "Default")
      (node (ref "U11") (pin "1A3") (pinfunction "VCCIO_1A3") (pintype "passive"))
    )
    (net (code "344") (name "unconnected-(U11-VCCIO-Pad1A5)") (class "Default")
      (node (ref "U11") (pin "1A5") (pinfunction "VCCIO_1A5") (pintype "passive"))
    )
    (net (code "345") (name "unconnected-(U11-VCCIO-Pad1A40)") (class "Default")
      (node (ref "U11") (pin "1A40") (pinfunction "VCCIO_1A40") (pintype "passive"))
    )
    (net (code "346") (name "unconnected-(U11-VCCIO-Pad1B40)") (class "Default")
      (node (ref "U11") (pin "1B40") (pinfunction "VCCIO_1B40") (pintype "passive"))
    )
    (net (code "347") (name "unconnected-(U11-VCCIO-Pad1C40)") (class "Default")
      (node (ref "U11") (pin "1C40") (pinfunction "VCCIO_1C40") (pintype "passive"))
    )
    (net (code "348") (name "unconnected-(U11-VCCIO-Pad2A7)") (class "Default")
      (node (ref "U11") (pin "2A7") (pinfunction "VCCIO_2A7") (pintype "passive"))
    )
    (net (code "349") (name "unconnected-(U11-VCCIO-Pad2A9)") (class "Default")
      (node (ref "U11") (pin "2A9") (pinfunction "VCCIO_2A9") (pintype "passive"))
    )
    (net (code "350") (name "unconnected-(U11-VCCIO-Pad2A11)") (class "Default")
      (node (ref "U11") (pin "2A11") (pinfunction "VCCIO_2A11") (pintype "passive"))
    )
    (net (code "351") (name "unconnected-(U11-VCCIO-Pad2A40)") (class "Default")
      (node (ref "U11") (pin "2A40") (pinfunction "VCCIO_2A40") (pintype "passive"))
    )
    (net (code "352") (name "unconnected-(U11-VCCIO-Pad2B40)") (class "Default")
      (node (ref "U11") (pin "2B40") (pinfunction "VCCIO_2B40") (pintype "passive"))
    )
    (net (code "353") (name "unconnected-(U11-VCCIO-Pad2C40)") (class "Default")
      (node (ref "U11") (pin "2C40") (pinfunction "VCCIO_2C40") (pintype "passive"))
    )
    (net (code "354") (name "unconnected-(U11-VDC-Pad2A3)") (class "Default")
      (node (ref "U11") (pin "2A3") (pinfunction "VDC_2A3") (pintype "passive"))
    )
    (net (code "355") (name "unconnected-(U11-VDC-Pad2A5)") (class "Default")
      (node (ref "U11") (pin "2A5") (pinfunction "VDC_2A5") (pintype "passive"))
    )
    (net (code "356") (name "unconnected-(U11-VREF-Pad1A7)") (class "Default")
      (node (ref "U11") (pin "1A7") (pinfunction "VREF_1A7") (pintype "passive"))
    )
    (net (code "357") (name "unconnected-(U11-VREF-Pad1A9)") (class "Default")
      (node (ref "U11") (pin "1A9") (pinfunction "VREF_1A9") (pintype "passive"))
    )
    (net (code "358") (name "unconnected-(U11-VREF-Pad2A13)") (class "Default")
      (node (ref "U11") (pin "2A13") (pinfunction "VREF_2A13") (pintype "passive"))
    )
    (net (code "359") (name "unconnected-(U11-VREF-Pad2A15)") (class "Default")
      (node (ref "U11") (pin "2A15") (pinfunction "VREF_2A15") (pintype "passive"))
    )
    (net (code "360") (name "unconnected-(U11-VREF-Pad2A16)") (class "Default")
      (node (ref "U11") (pin "2A16") (pinfunction "VREF_2A16") (pintype "passive"))
    )
    (net (code "361") (name "unconnected-(U11-W15{slash}B35p-Pad2A33)") (class "Default")
      (node (ref "U11") (pin "2A33") (pinfunction "W15/B35p_2A33") (pintype "passive"))
    )
    (net (code "362") (name "unconnected-(U11-W21{slash}R32p-Pad1C31)") (class "Default")
      (node (ref "U11") (pin "1C31") (pinfunction "W21/R32p_1C31") (pintype "passive"))
    )
    (net (code "363") (name "unconnected-(U11-W22{slash}R32n-Pad1C33)") (class "Default")
      (node (ref "U11") (pin "1C33") (pinfunction "W22/R32n_1C33") (pintype "passive"))
    )
    (net (code "364") (name "unconnected-(U11-Y1{slash}L29n-Pad1C13)") (class "Default")
      (node (ref "U11") (pin "1C13") (pinfunction "Y1/L29n_1C13") (pintype "passive"))
    )
    (net (code "365") (name "unconnected-(U11-Y4{slash}B3p-Pad2A23)") (class "Default")
      (node (ref "U11") (pin "2A23") (pinfunction "Y4/B3p_2A23") (pintype "passive"))
    )
    (net (code "366") (name "unconnected-(U11-Y8{slash}B11p-Pad1B34)") (class "Default")
      (node (ref "U11") (pin "1B34") (pinfunction "Y8/B11p_1B34") (pintype "passive"))
    )
    (net (code "367") (name "unconnected-(U11-Y21{slash}R35p-Pad1C27)") (class "Default")
      (node (ref "U11") (pin "1C27") (pinfunction "Y21/R35p_1C27") (pintype "passive"))
    )
    (net (code "368") (name "unconnected-(U11-Y22{slash}R35n-Pad1C29)") (class "Default")
      (node (ref "U11") (pin "1C29") (pinfunction "Y22/R35n_1C29") (pintype "passive"))
    )
    (net (code "369") (name "unconnected-(U11-n{slash}c-Pad2A4)") (class "Default")
      (node (ref "U11") (pin "2A4") (pinfunction "n/c_2A4") (pintype "passive"))
    )
    (net (code "370") (name "unconnected-(U11-n{slash}c-Pad2A6)") (class "Default")
      (node (ref "U11") (pin "2A6") (pinfunction "n/c_2A6") (pintype "passive"))
    )
    (net (code "371") (name "unconnected-(U11-n{slash}c-Pad2A8)") (class "Default")
      (node (ref "U11") (pin "2A8") (pinfunction "n/c_2A8") (pintype "passive"))
    )
    (net (code "372") (name "unconnected-(U11-n{slash}c-Pad2A20)") (class "Default")
      (node (ref "U11") (pin "2A20") (pinfunction "n/c_2A20") (pintype "passive"))
    )
    (net (code "373") (name "unconnected-(U11-n{slash}c-Pad2A36)") (class "Default")
      (node (ref "U11") (pin "2A36") (pinfunction "n/c_2A36") (pintype "passive"))
    )
    (net (code "374") (name "unconnected-(U11-n{slash}c-Pad2A38)") (class "Default")
      (node (ref "U11") (pin "2A38") (pinfunction "n/c_2A38") (pintype "passive"))
    )
  )
)
